# Master-Slave.net
KiCad netlist of a schematic drawn in Altium Designer
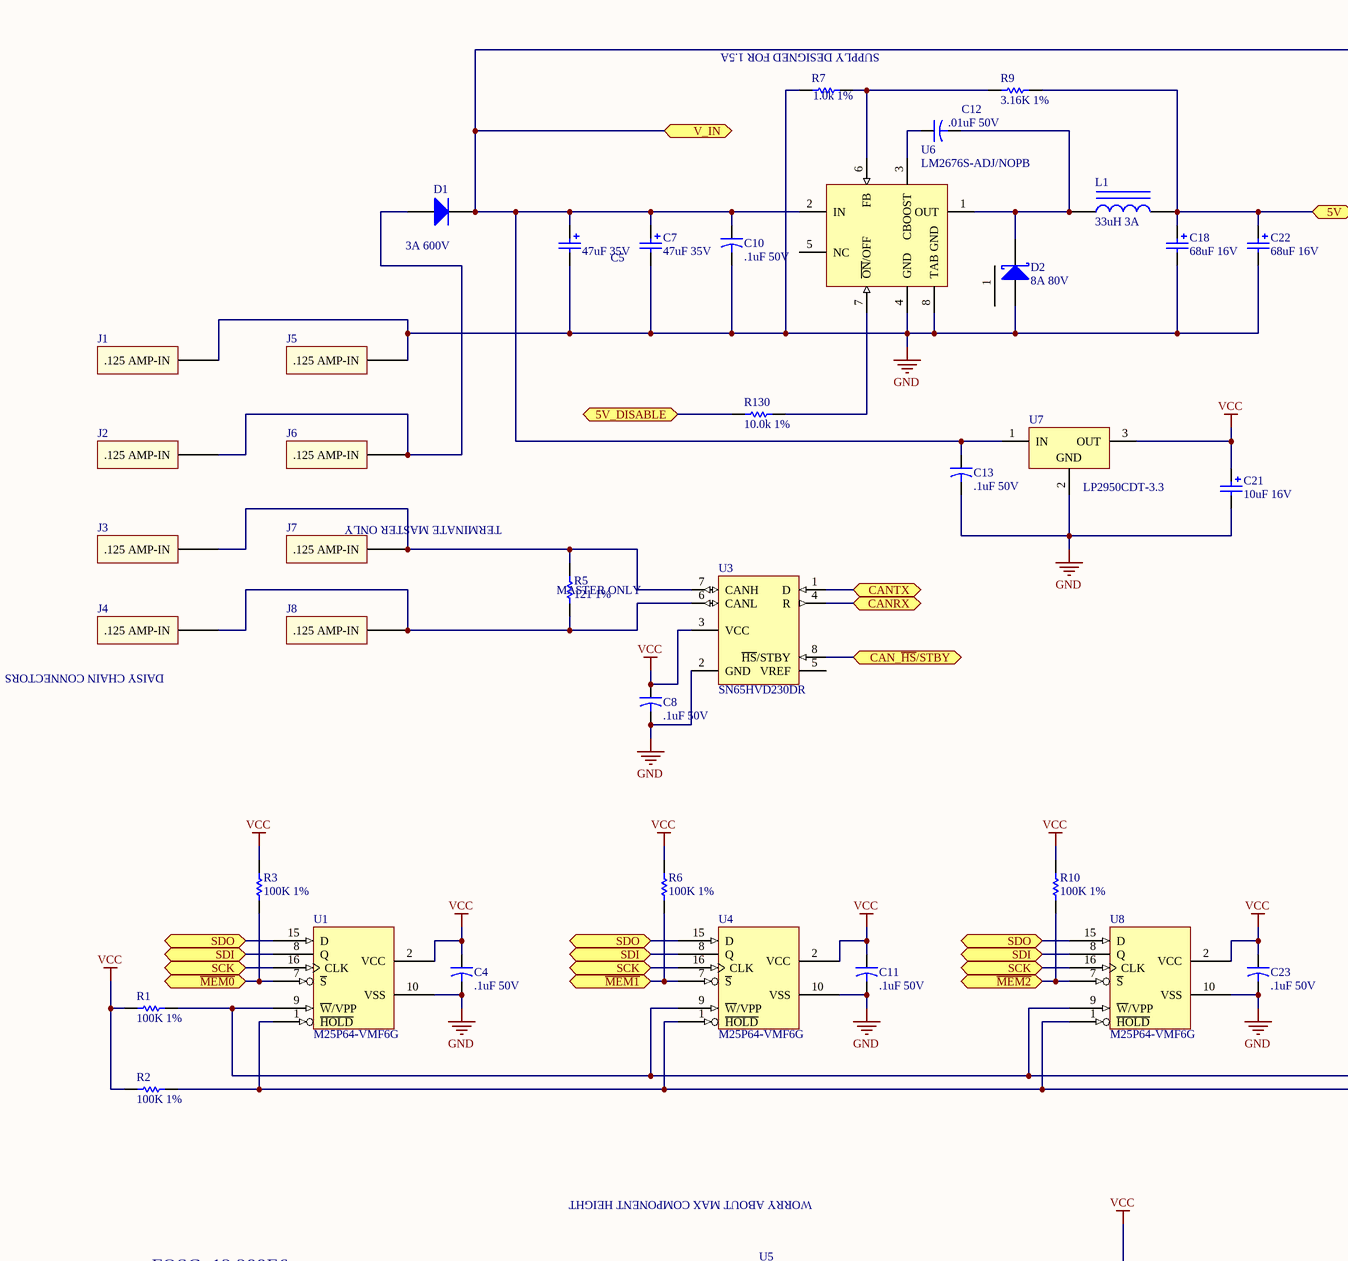
[diagram p0: Master-Slave.SchDoc, top left]
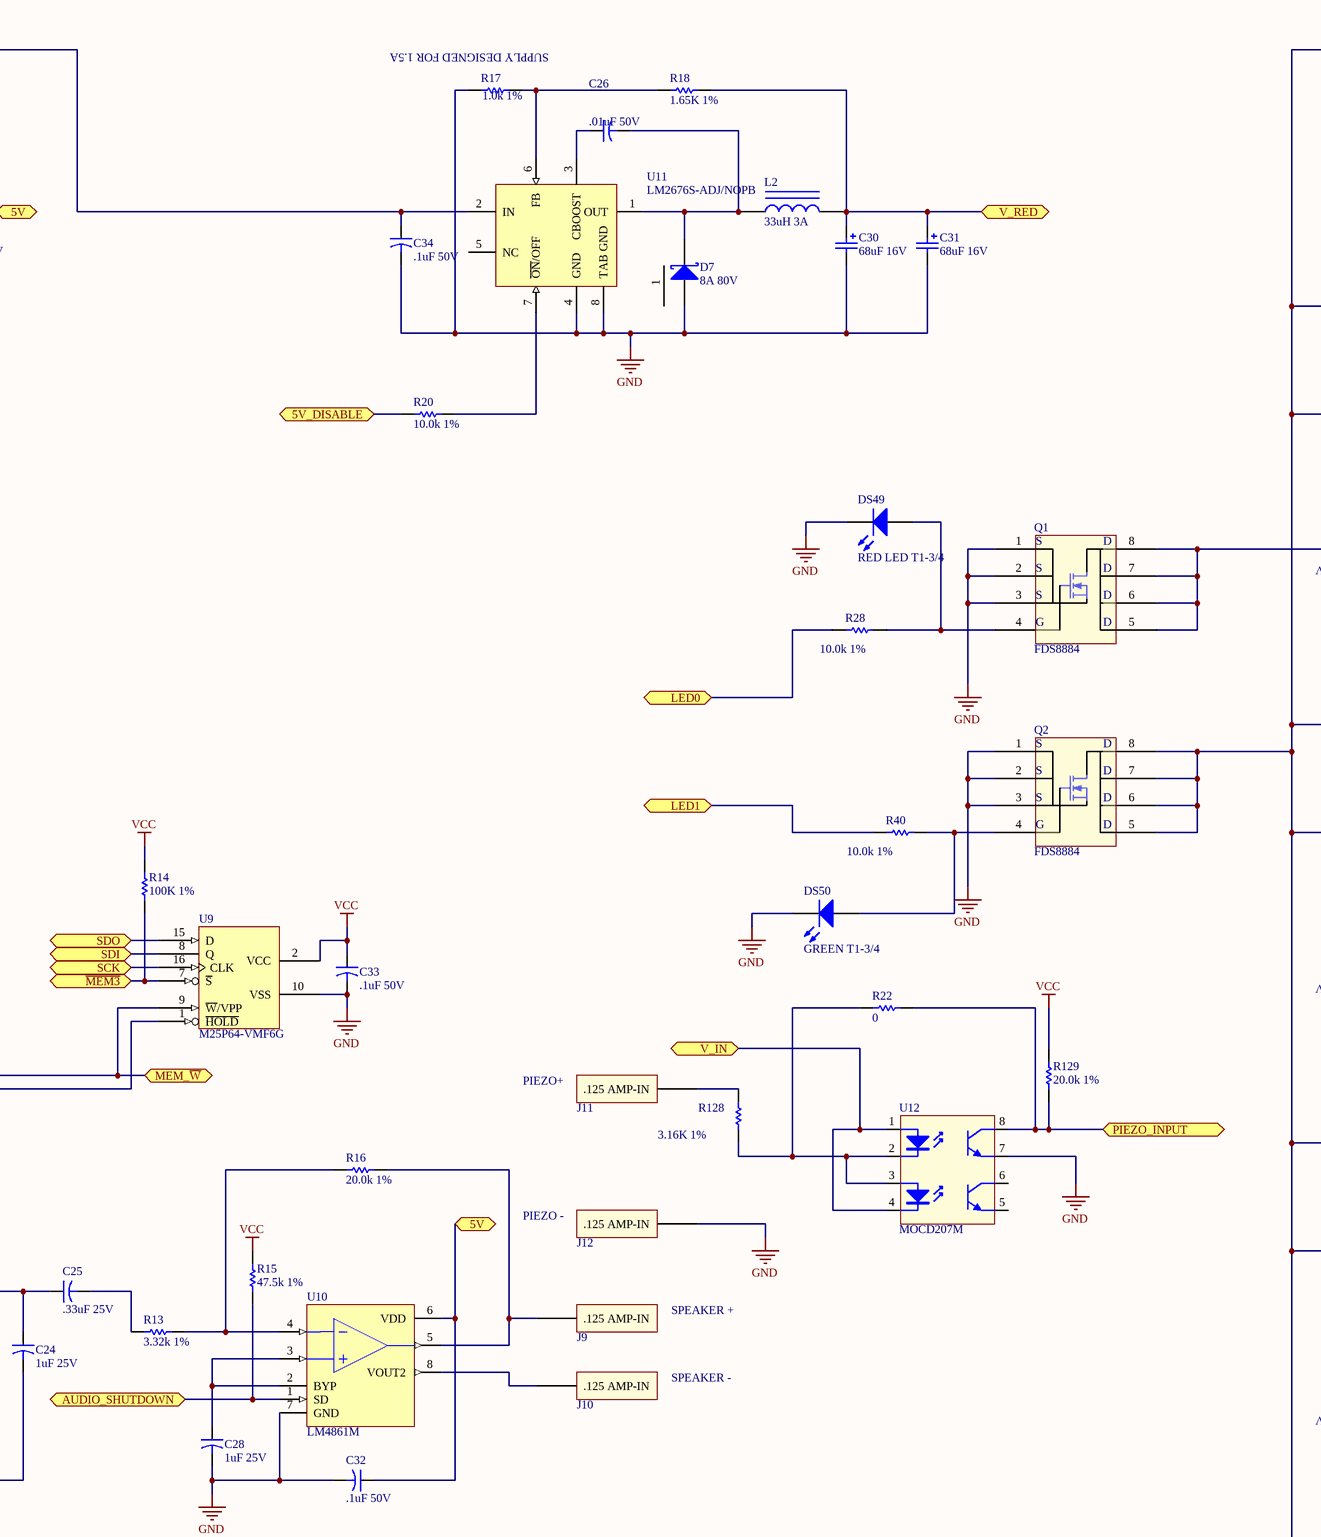
[diagram p1: Master-Slave.SchDoc, top middle]
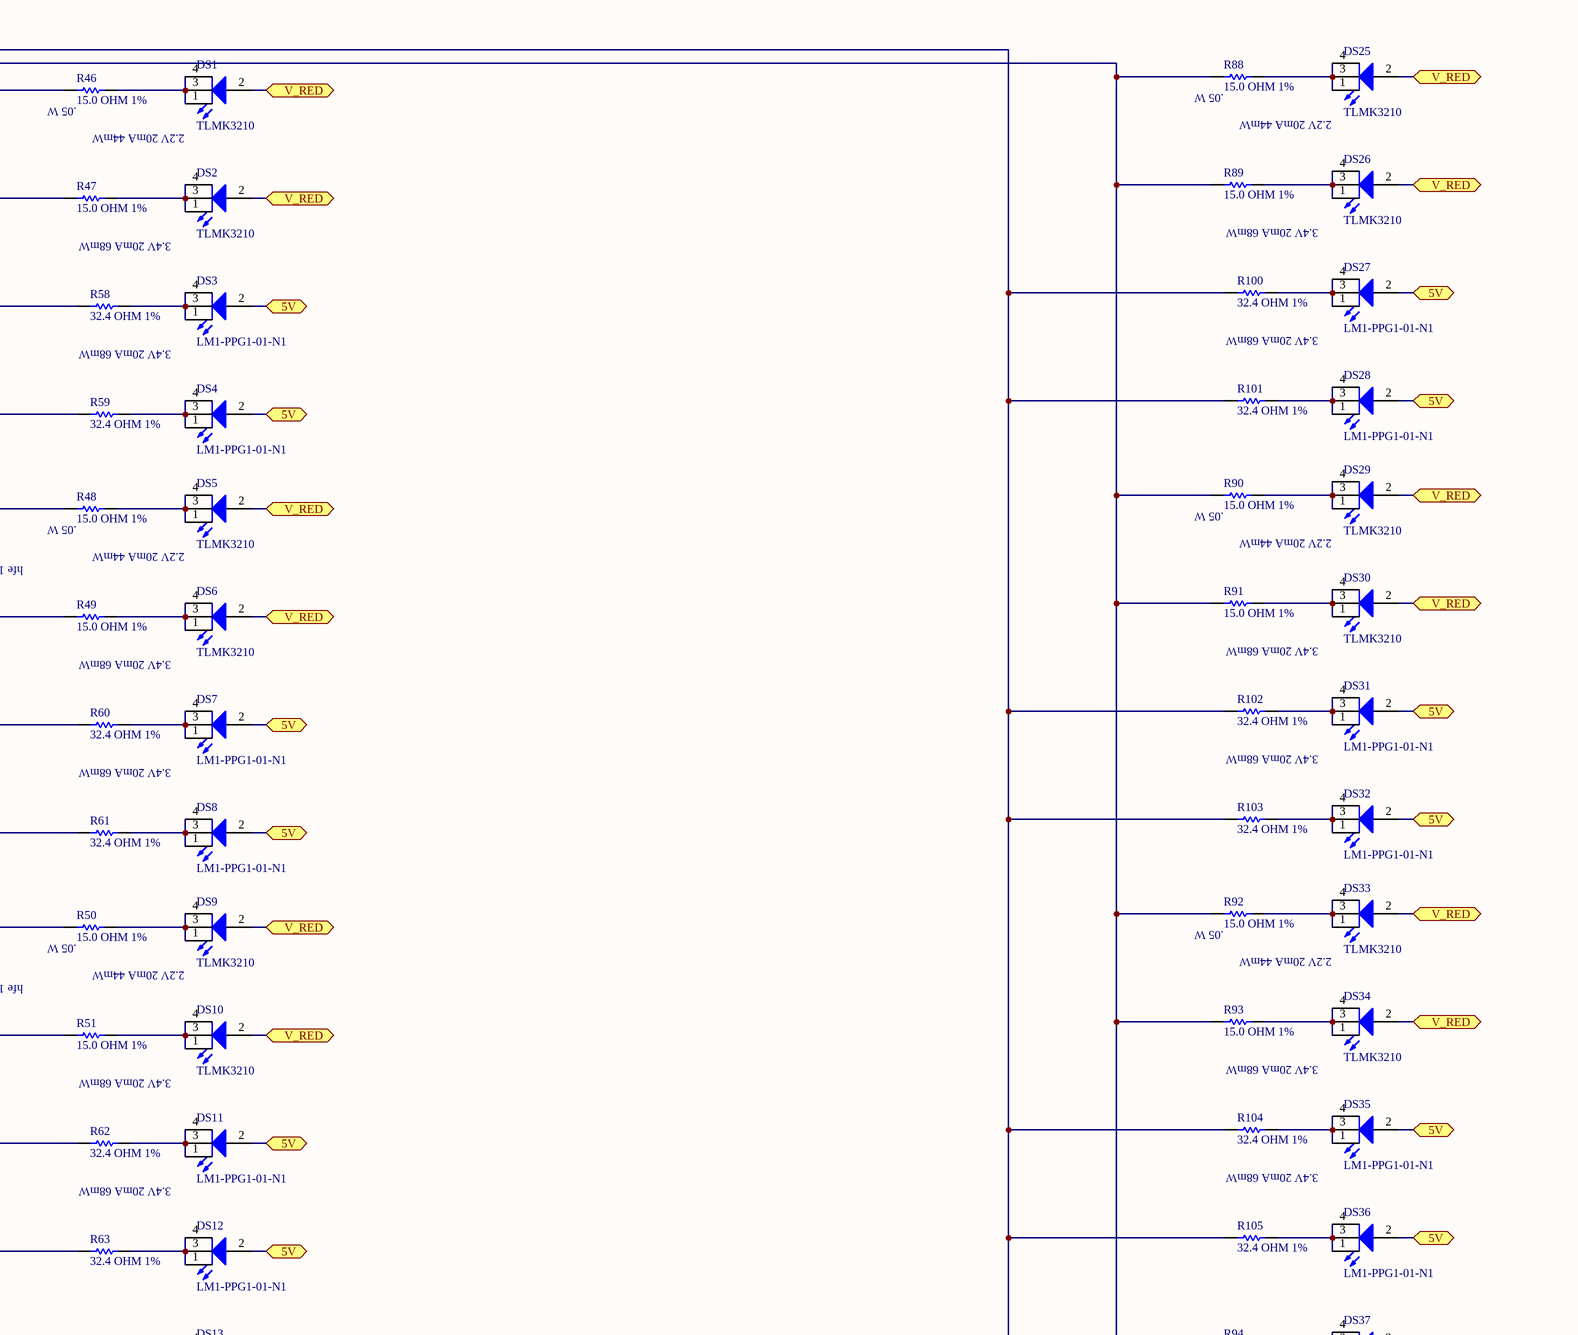
[diagram p2: Master-Slave.SchDoc, top right]
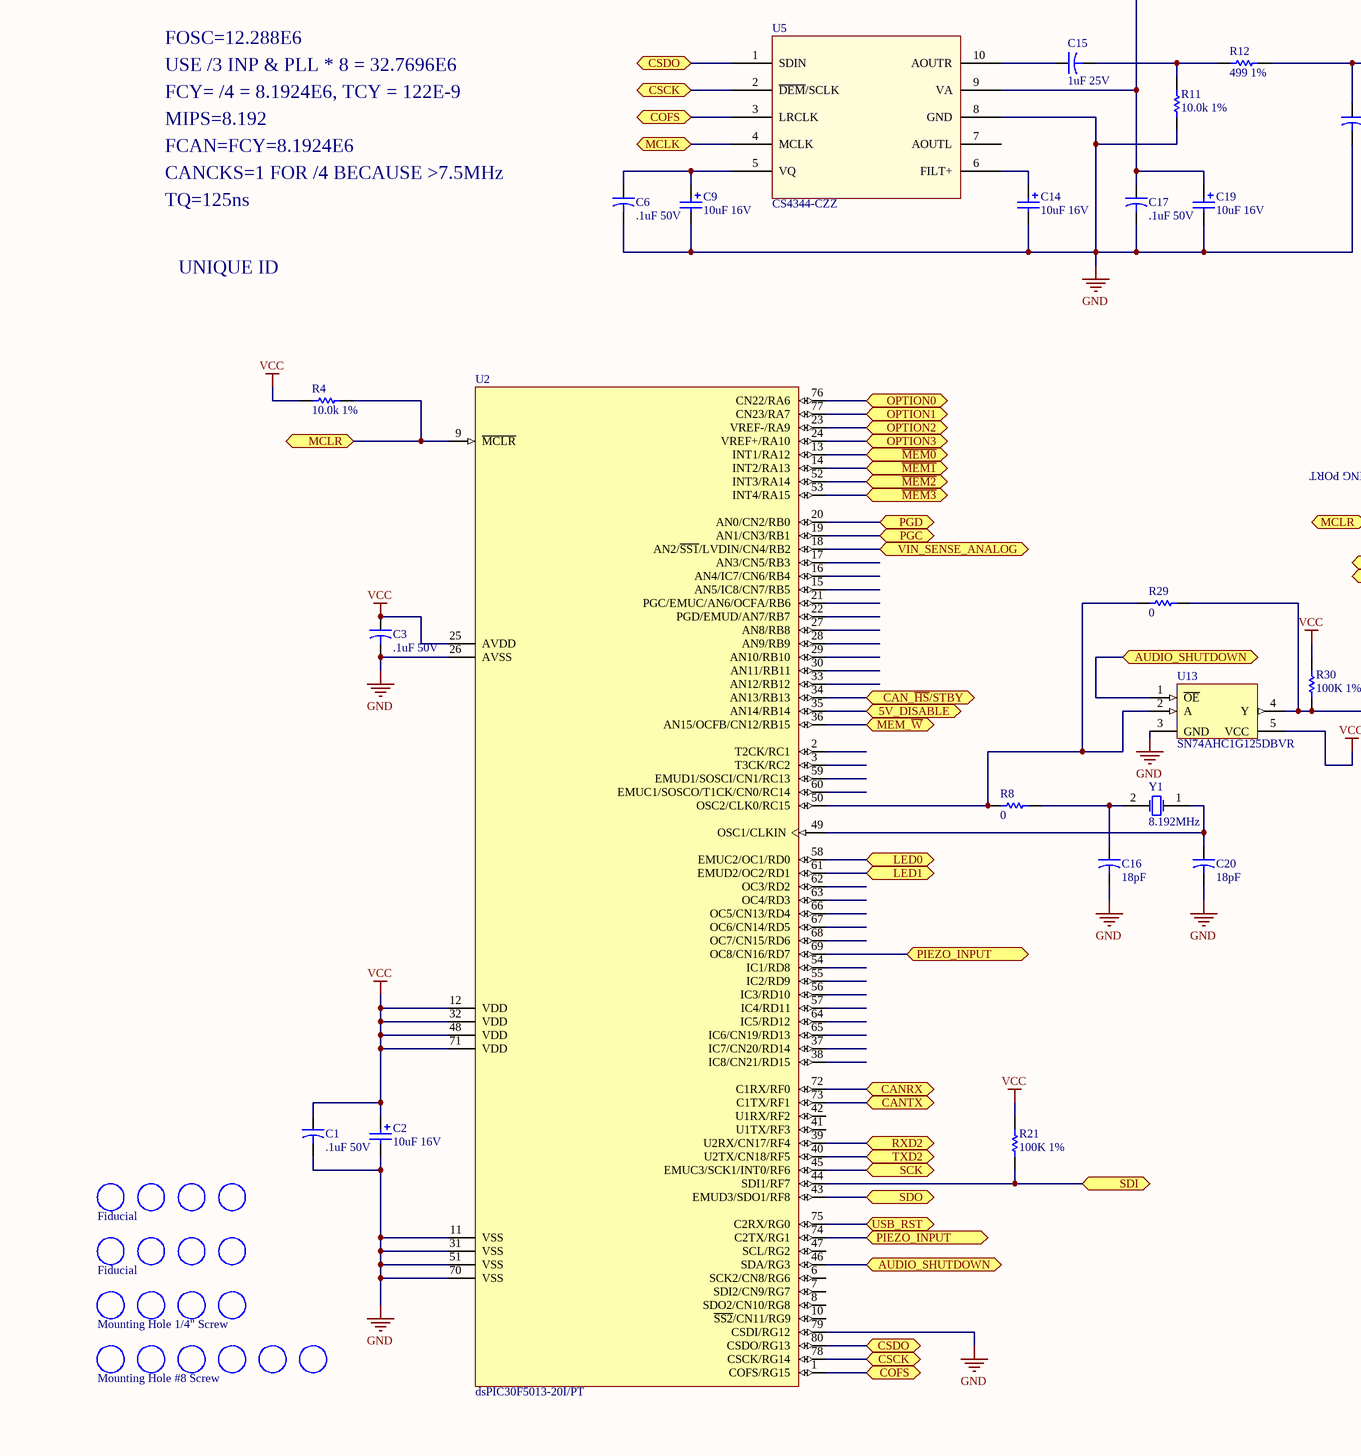
[diagram p3: Master-Slave.SchDoc, bottom left]
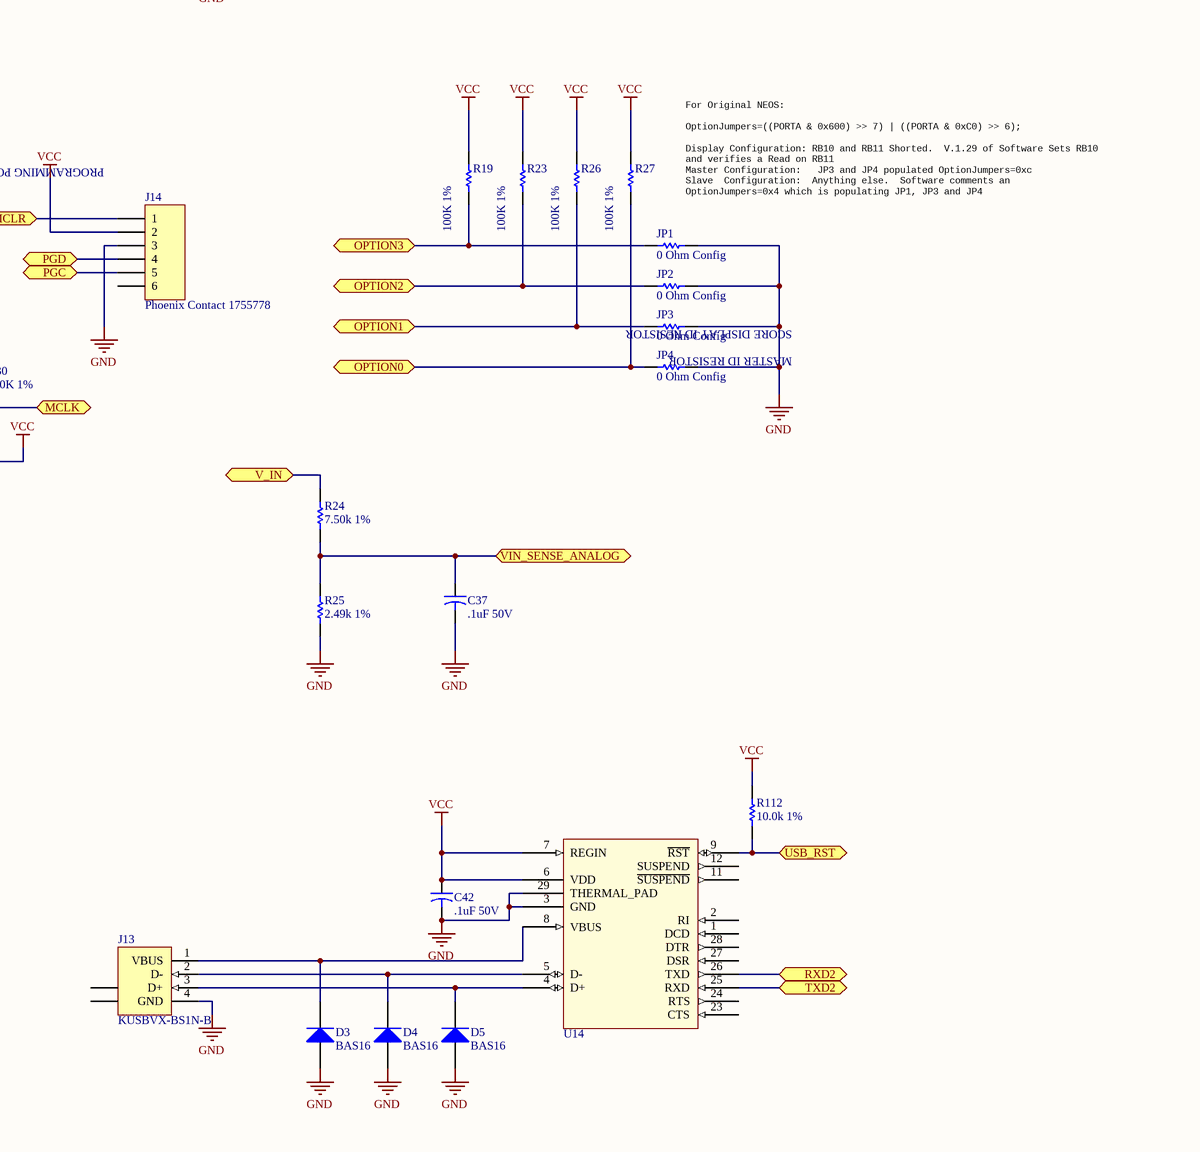
[diagram p4: Master-Slave.SchDoc, bottom middle]
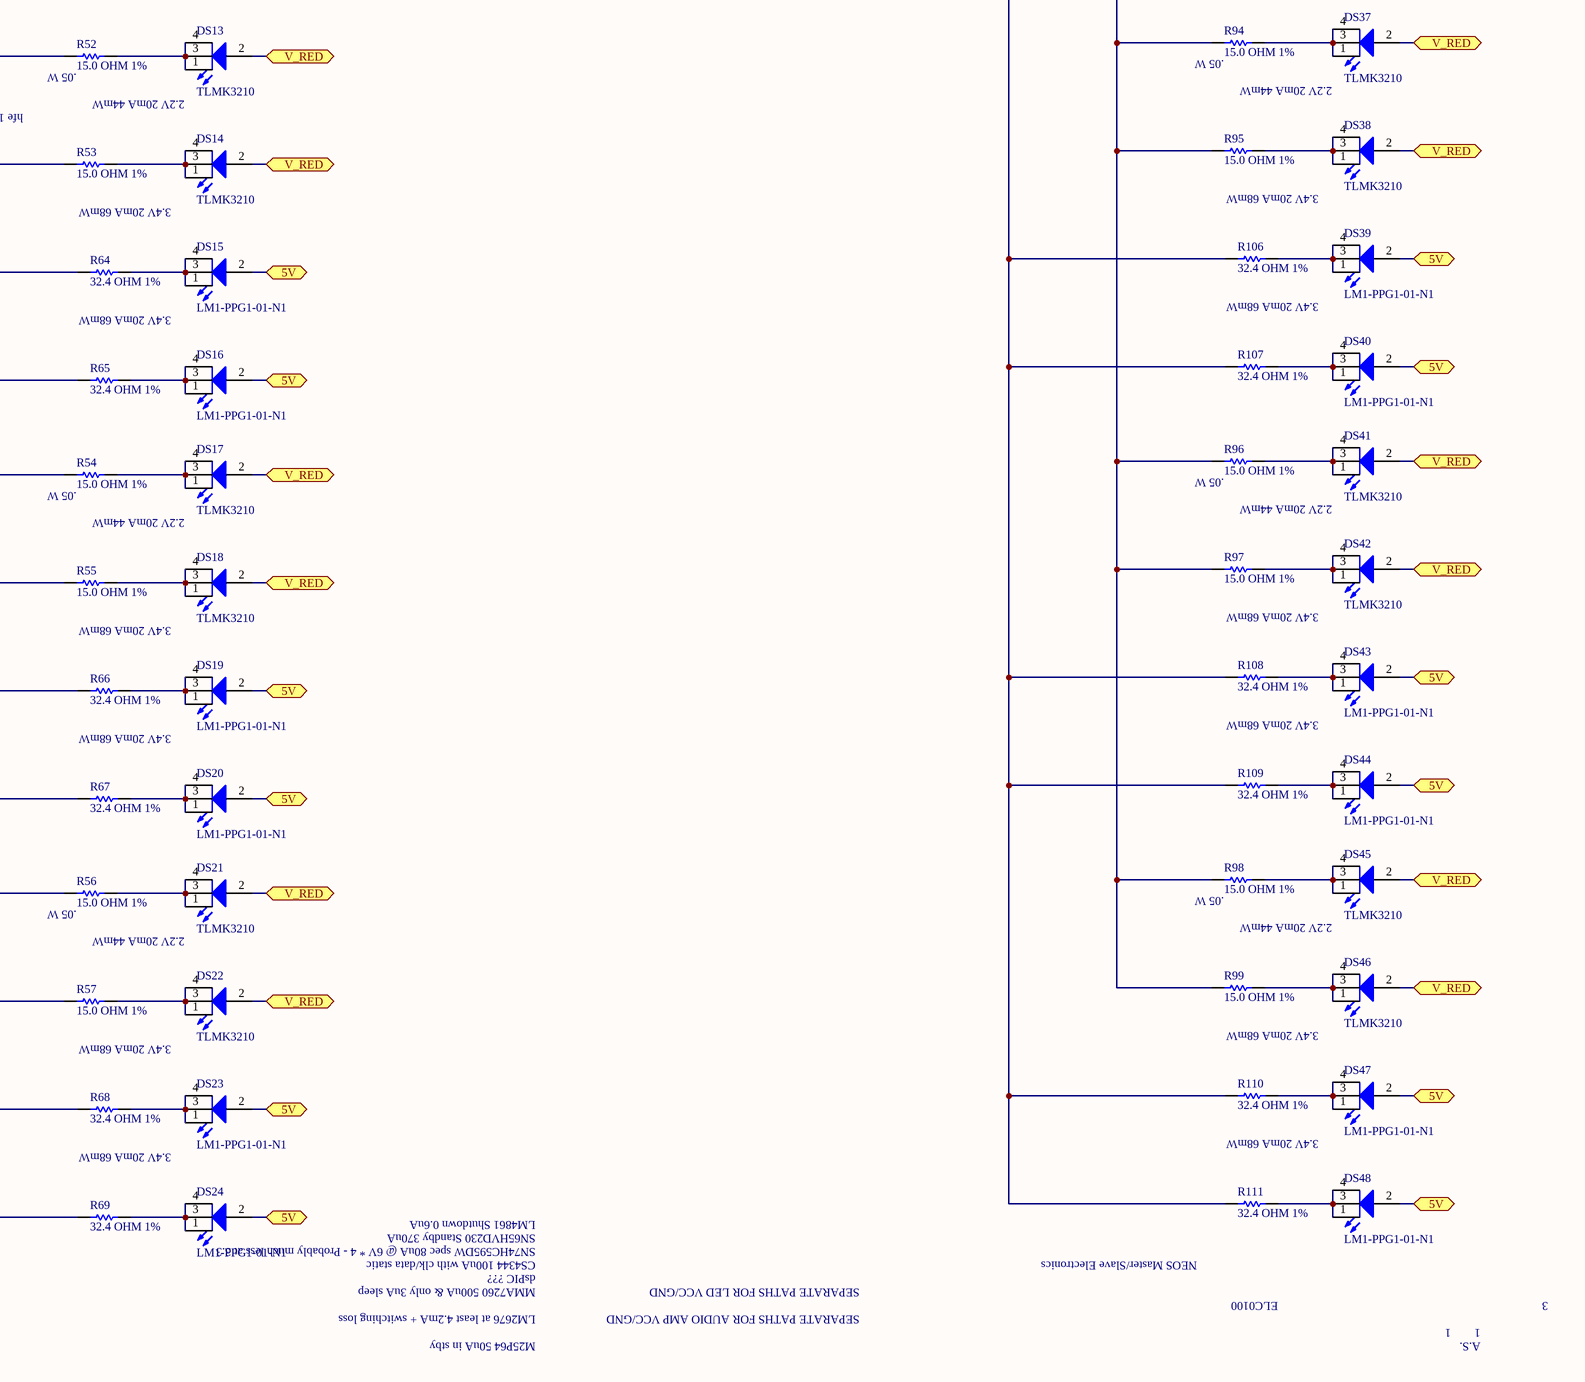
[diagram p5: Master-Slave.SchDoc, bottom right]

(export (version "E")
  (design (tool "Eeschema 10.0.6"))
  (components
    (comp (ref "C1")
      (value ".1uF 50V")
      (footprint "C0805")
      (description "CAP .10UF 50V CERAMIC X7R 0805")
      (fields
        (field (name "MANUFACTURER") "Kemet")
        (field (name "MANUFACTURER PART NUMBER") "C0805C104K5RACTU")
        (field (name "SOURCE") "Digikey")
      )
      (libsource (lib "") (part "C#S/C0805C104K5RACK_1"))
    )
    (comp (ref "C2")
      (value "10uF 16V")
      (footprint "API:C4X5.8")
      (description "CAP ELECT 10UF 16V FK SMD")
      (fields
        (field (name "MANUFACTURER") "Panasonic - ECG")
        (field (name "MANUFACTURER PART NUMBER") "EEE-FK1C100R")
        (field (name "SOURCE") "Digikey")
      )
      (libsource (lib "API") (part "C#S/EEEFK1C100RP"))
    )
    (comp (ref "C3")
      (value ".1uF 50V")
      (footprint "C0805")
      (description "CAP .10UF 50V CERAMIC X7R 0805")
      (fields
        (field (name "MANUFACTURER") "Kemet")
        (field (name "MANUFACTURER PART NUMBER") "C0805C104K5RACTU")
        (field (name "SOURCE") "Digikey")
      )
      (libsource (lib "") (part "C#S/C0805C104K5RACK_1"))
    )
    (comp (ref "C4")
      (value ".1uF 50V")
      (footprint "C0805")
      (description "CAP .10UF 50V CERAMIC X7R 0805")
      (fields
        (field (name "MANUFACTURER") "Kemet")
        (field (name "MANUFACTURER PART NUMBER") "C0805C104K5RACTU")
        (field (name "SOURCE") "Digikey")
      )
      (libsource (lib "API") (part "C#S/C0805C104K5RACK"))
    )
    (comp (ref "C5")
      (value "47uF 35V")
      (footprint "CAPACITOR TANT 47UF 35V 10% SMD 7343-43 (EIA")
      (description "CAPACITOR TANT 47UF 35V 10% SMD 7343-43 (EIA)")
      (fields
        (field (name "MANUFACTURER") "Kemet")
        (field (name "MANUFACTURER PART NUMBER") "T491X476K035AT")
        (field (name "SOURCE") "Digikey")
      )
      (libsource (lib "API") (part "C#S/T491X476K035ATK"))
    )
    (comp (ref "C6")
      (value ".1uF 50V")
      (footprint "C0805")
      (description "CAP .10UF 50V CERAMIC X7R 0805")
      (fields
        (field (name "MANUFACTURER") "Kemet")
        (field (name "MANUFACTURER PART NUMBER") "C0805C104K5RACTU")
        (field (name "SOURCE") "Digikey")
      )
      (libsource (lib "API") (part "C#S/C0805C104K5RACK"))
    )
    (comp (ref "C7")
      (value "47uF 35V")
      (footprint "CAPACITOR TANT 47UF 35V 10% SMD 7343-43 (EIA")
      (description "CAPACITOR TANT 47UF 35V 10% SMD 7343-43 (EIA)")
      (fields
        (field (name "MANUFACTURER") "Kemet")
        (field (name "MANUFACTURER PART NUMBER") "T491X476K035AT")
        (field (name "SOURCE") "Digikey")
      )
      (libsource (lib "API") (part "C#S/T491X476K035ATK"))
    )
    (comp (ref "C8")
      (value ".1uF 50V")
      (footprint "C0805")
      (description "CAP .10UF 50V CERAMIC X7R 0805")
      (fields
        (field (name "MANUFACTURER") "Kemet")
        (field (name "MANUFACTURER PART NUMBER") "C0805C104K5RACTU")
        (field (name "SOURCE") "Digikey")
      )
      (libsource (lib "API") (part "C#S/C0805C104K5RACK"))
    )
    (comp (ref "C9")
      (value "10uF 16V")
      (footprint "API:C4X5.8")
      (description "CAP ELECT 10UF 16V FK SMD")
      (fields
        (field (name "MANUFACTURER") "Panasonic - ECG")
        (field (name "MANUFACTURER PART NUMBER") "EEE-FK1C100R")
        (field (name "SOURCE") "Digikey")
      )
      (libsource (lib "API") (part "C#S/EEEFK1C100RP"))
    )
    (comp (ref "C10")
      (value ".1uF 50V")
      (footprint "C0805")
      (description "CAP .10UF 50V CERAMIC X7R 0805")
      (fields
        (field (name "MANUFACTURER") "Kemet")
        (field (name "MANUFACTURER PART NUMBER") "C0805C104K5RACTU")
        (field (name "SOURCE") "Digikey")
      )
      (libsource (lib "API") (part "C#S/C0805C104K5RACK"))
    )
    (comp (ref "C11")
      (value ".1uF 50V")
      (footprint "C0805")
      (description "CAP .10UF 50V CERAMIC X7R 0805")
      (fields
        (field (name "MANUFACTURER") "Kemet")
        (field (name "MANUFACTURER PART NUMBER") "C0805C104K5RACTU")
        (field (name "SOURCE") "Digikey")
      )
      (libsource (lib "API") (part "C#S/C0805C104K5RACK"))
    )
    (comp (ref "C12")
      (value ".01uF 50V")
      (footprint "API:C0805")
      (description "CAP 10000PF 50V CERAMIC X7R 0805")
      (fields
        (field (name "MANUFACTURER") "Kemet")
        (field (name "MANUFACTURER PART NUMBER") "C0805C103K5RACTU")
        (field (name "SOURCE") "Digikey")
      )
      (libsource (lib "API") (part "C#S/C0805C103K5RAC"))
    )
    (comp (ref "C13")
      (value ".1uF 50V")
      (footprint "C0805")
      (description "CAP .10UF 50V CERAMIC X7R 0805")
      (fields
        (field (name "MANUFACTURER") "Kemet")
        (field (name "MANUFACTURER PART NUMBER") "C0805C104K5RACTU")
        (field (name "SOURCE") "Digikey")
      )
      (libsource (lib "API") (part "C#S/C0805C104K5RACK"))
    )
    (comp (ref "C14")
      (value "10uF 16V")
      (footprint "C4X5.8")
      (description "CAP ELECT 10UF 16V FK SMD")
      (fields
        (field (name "MANUFACTURER") "Panasonic - ECG")
        (field (name "MANUFACTURER PART NUMBER") "EEE-FK1C100R")
        (field (name "SOURCE") "Digikey")
      )
      (libsource (lib "API") (part "C#S/EEEFK1C100RP"))
    )
    (comp (ref "C15")
      (value "1uF 25V")
      (footprint "API:R1206")
      (description "CAP 1UF 25V CERAMIC X7R 1206")
      (fields
        (field (name "MANUFACTURER") "Panasonic - ECG")
        (field (name "MANUFACTURER PART NUMBER") "ECJ-3YB1E105K")
        (field (name "SOURCE") "Digikey")
      )
      (libsource (lib "API") (part "C#S/ECJ3YB1E105KP"))
    )
    (comp (ref "C16")
      (value "18pF")
      (footprint "API:C0805")
      (description "CAP CERAMIC 18PF 50V NP0 0805")
      (fields
        (field (name "MANUFACTURER") "Kemet")
        (field (name "MANUFACTURER PART NUMBER") "C0805C180J5GACTU")
        (field (name "SOURCE") "Digikey")
      )
      (libsource (lib "API") (part "C#S/C0805C180J5GACTUK"))
    )
    (comp (ref "C17")
      (value ".1uF 50V")
      (footprint "C0805")
      (description "CAP .10UF 50V CERAMIC X7R 0805")
      (fields
        (field (name "MANUFACTURER") "Kemet")
        (field (name "MANUFACTURER PART NUMBER") "C0805C104K5RACTU")
        (field (name "SOURCE") "Digikey")
      )
      (libsource (lib "API") (part "C#S/C0805C104K5RACK"))
    )
    (comp (ref "C18")
      (value "68uF 16V")
      (footprint "API:C7343")
      (description "CAPACITOR TANT 68UF 16V 10% SMD")
      (fields
        (field (name "MANUFACTURER") "Kemet")
        (field (name "MANUFACTURER PART NUMBER") "T495D686K016ATE150")
        (field (name "SOURCE") "Digikey")
      )
      (libsource (lib "API") (part "C#S/T495D686K016ATEK"))
    )
    (comp (ref "C19")
      (value "10uF 16V")
      (footprint "API:C4X5.8")
      (description "CAP ELECT 10UF 16V FK SMD")
      (fields
        (field (name "MANUFACTURER") "Panasonic - ECG")
        (field (name "MANUFACTURER PART NUMBER") "EEE-FK1C100R")
        (field (name "SOURCE") "Digikey")
      )
      (libsource (lib "API") (part "C#S/EEEFK1C100RP"))
    )
    (comp (ref "C20")
      (value "18pF")
      (footprint "API:C0805")
      (description "CAP CERAMIC 18PF 50V NP0 0805")
      (fields
        (field (name "MANUFACTURER") "Kemet")
        (field (name "MANUFACTURER PART NUMBER") "C0805C180J5GACTU")
        (field (name "SOURCE") "Digikey")
      )
      (libsource (lib "API") (part "C#S/C0805C180J5GACTUK"))
    )
    (comp (ref "C21")
      (value "10uF 16V")
      (footprint "API:C4X5.8")
      (description "CAP ELECT 10UF 16V FK SMD")
      (fields
        (field (name "MANUFACTURER") "Panasonic - ECG")
        (field (name "MANUFACTURER PART NUMBER") "EEE-FK1C100R")
        (field (name "SOURCE") "Digikey")
      )
      (libsource (lib "API") (part "C#S/EEEFK1C100RP"))
    )
    (comp (ref "C22")
      (value "68uF 16V")
      (footprint "API:C7343")
      (description "CAPACITOR TANT 68UF 16V 10% SMD")
      (fields
        (field (name "MANUFACTURER") "Kemet")
        (field (name "MANUFACTURER PART NUMBER") "T495D686K016ATE150")
        (field (name "SOURCE") "Digikey")
      )
      (libsource (lib "API") (part "C#S/T495D686K016ATEK"))
    )
    (comp (ref "C23")
      (value ".1uF 50V")
      (footprint "C0805")
      (description "CAP .10UF 50V CERAMIC X7R 0805")
      (fields
        (field (name "MANUFACTURER") "Kemet")
        (field (name "MANUFACTURER PART NUMBER") "C0805C104K5RACTU")
        (field (name "SOURCE") "Digikey")
      )
      (libsource (lib "API") (part "C#S/C0805C104K5RACK"))
    )
    (comp (ref "C24")
      (value "1uF 25V")
      (footprint "API:R1206")
      (description "CAP 1UF 25V CERAMIC X7R 1206")
      (fields
        (field (name "MANUFACTURER") "Panasonic - ECG")
        (field (name "MANUFACTURER PART NUMBER") "ECJ-3YB1E105K")
        (field (name "SOURCE") "Digikey")
      )
      (libsource (lib "API") (part "C#S/ECJ3YB1E105KP"))
    )
    (comp (ref "C25")
      (value ".33uF 25V")
      (footprint "API:R1206")
      (description "CAP .33UF 25V CERAMIC X7R 1206")
      (fields
        (field (name "MANUFACTURER") "Panasonic - ECG")
        (field (name "MANUFACTURER PART NUMBER") "ECJ-3VB1E334K")
        (field (name "SOURCE") "Digikey")
      )
      (libsource (lib "API") (part "C#S/ECJ3VB1E334KP"))
    )
    (comp (ref "C26")
      (value ".01uF 50V")
      (footprint "API:C0805")
      (description "CAP 10000PF 50V CERAMIC X7R 0805")
      (fields
        (field (name "MANUFACTURER") "Kemet")
        (field (name "MANUFACTURER PART NUMBER") "C0805C103K5RACTU")
        (field (name "SOURCE") "Digikey")
      )
      (libsource (lib "API") (part "C#S/C0805C103K5RAC"))
    )
    (comp (ref "C28")
      (value "1uF 25V")
      (footprint "API:R1206")
      (description "CAP 1UF 25V CERAMIC X7R 1206")
      (fields
        (field (name "MANUFACTURER") "Panasonic - ECG")
        (field (name "MANUFACTURER PART NUMBER") "ECJ-3YB1E105K")
        (field (name "SOURCE") "Digikey")
      )
      (libsource (lib "API") (part "C#S/ECJ3YB1E105KP"))
    )
    (comp (ref "C30")
      (value "68uF 16V")
      (footprint "D")
      (description "CAPACITOR TANT 68UF 16V 10% SMD")
      (fields
        (field (name "MANUFACTURER") "Kemet")
        (field (name "MANUFACTURER PART NUMBER") "T495D686K016ATE150")
        (field (name "SOURCE") "Digikey")
      )
      (libsource (lib "API") (part "C#S/T495D686K016ATEK"))
    )
    (comp (ref "C31")
      (value "68uF 16V")
      (footprint "API:C7343")
      (description "CAPACITOR TANT 68UF 16V 10% SMD")
      (fields
        (field (name "MANUFACTURER") "Kemet")
        (field (name "MANUFACTURER PART NUMBER") "T495D686K016ATE150")
        (field (name "SOURCE") "Digikey")
      )
      (libsource (lib "API") (part "C#S/T495D686K016ATEK"))
    )
    (comp (ref "C32")
      (value ".1uF 50V")
      (footprint "C0805")
      (description "CAP .10UF 50V CERAMIC X7R 0805")
      (fields
        (field (name "MANUFACTURER") "Kemet")
        (field (name "MANUFACTURER PART NUMBER") "C0805C104K5RACTU")
        (field (name "SOURCE") "Digikey")
      )
      (libsource (lib "API") (part "C#S/C0805C104K5RACK"))
    )
    (comp (ref "C33")
      (value ".1uF 50V")
      (footprint "C0805")
      (description "CAP .10UF 50V CERAMIC X7R 0805")
      (fields
        (field (name "MANUFACTURER") "Kemet")
        (field (name "MANUFACTURER PART NUMBER") "C0805C104K5RACTU")
        (field (name "SOURCE") "Digikey")
      )
      (libsource (lib "API") (part "C#S/C0805C104K5RACK"))
    )
    (comp (ref "C34")
      (value ".1uF 50V")
      (footprint "C0805")
      (description "CAP .10UF 50V CERAMIC X7R 0805")
      (fields
        (field (name "MANUFACTURER") "Kemet")
        (field (name "MANUFACTURER PART NUMBER") "C0805C104K5RACTU")
        (field (name "SOURCE") "Digikey")
      )
      (libsource (lib "API") (part "C#S/C0805C104K5RACK"))
    )
    (comp (ref "C37")
      (value ".1uF 50V")
      (footprint "C0805")
      (description "CAP .10UF 50V CERAMIC X7R 0805")
      (fields
        (field (name "MANUFACTURER") "Kemet")
        (field (name "MANUFACTURER PART NUMBER") "C0805C104K5RACTU")
        (field (name "SOURCE") "Digikey")
      )
      (libsource (lib "API") (part "C#S/C0805C104K5RACK"))
    )
    (comp (ref "C42")
      (value ".1uF 50V")
      (footprint "C0805")
      (description "CAP .10UF 50V CERAMIC X7R 0805")
      (fields
        (field (name "MANUFACTURER") "Kemet")
        (field (name "MANUFACTURER PART NUMBER") "C0805C104K5RACTU")
        (field (name "SOURCE") "Digikey")
      )
      (libsource (lib "API") (part "C#S/C0805C104K5RACK"))
    )
    (comp (ref "D1")
      (value "3A 600V")
      (footprint "API:DIODE_SMC")
      (description "DIODE ULTRA FAST 3A 600V SMC")
      (fields
        (field (name "MANUFACTURER") "ON Semiconductor")
        (field (name "MANUFACTURER PART NUMBER") "MURS360T3G")
        (field (name "SOURCE") "Digikey")
      )
      (libsource (lib "API") (part "D#S/MURS360T3GM"))
    )
    (comp (ref "D2")
      (value "8A 80V")
      (footprint "API:D2PAK")
      (description "DIODE SCHOTTKY 80V 8A D2PAK")
      (fields
        (field (name "MANUFACTURER") "Vishay IR")
        (field (name "MANUFACTURER PART NUMBER") "8TQ100SPBF")
        (field (name "SOURCE") "Digikey")
      )
      (libsource (lib "API") (part "D#S/8TQ080SPBFZ"))
    )
    (comp (ref "D3")
      (value "BAS16")
      (footprint "API:SOT23")
      (description "Diodes Inc BAS16 75V 200mA")
      (fields
        (field (name "MANUFACTURER") "Diodes Inc")
        (field (name "MANUFACTURER PART NUMBER") "BAS16-7-F")
        (field (name "SOURCE") "Digikey")
      )
      (libsource (lib "API") (part "D#S/BAS167F0D"))
    )
    (comp (ref "D4")
      (value "BAS16")
      (footprint "API:SOT23")
      (description "Diodes Inc BAS16 75V 200mA")
      (fields
        (field (name "MANUFACTURER") "Diodes Inc")
        (field (name "MANUFACTURER PART NUMBER") "BAS16-7-F")
        (field (name "SOURCE") "Digikey")
      )
      (libsource (lib "API") (part "D#S/BAS167F0D"))
    )
    (comp (ref "D5")
      (value "BAS16")
      (footprint "API:SOT23")
      (description "Diodes Inc BAS16 75V 200mA")
      (fields
        (field (name "MANUFACTURER") "Diodes Inc")
        (field (name "MANUFACTURER PART NUMBER") "BAS16-7-F")
        (field (name "SOURCE") "Digikey")
      )
      (libsource (lib "API") (part "D#S/BAS167F0D"))
    )
    (comp (ref "D7")
      (value "8A 80V")
      (footprint "API:D2PAK")
      (description "DIODE SCHOTTKY 80V 8A D2PAK")
      (fields
        (field (name "MANUFACTURER") "Vishay IR")
        (field (name "MANUFACTURER PART NUMBER") "8TQ100SPBF")
        (field (name "SOURCE") "Digikey")
      )
      (libsource (lib "API") (part "D#S/8TQ080SPBFZ"))
    )
    (comp (ref "DS1")
      (value "TLMK3210")
      (footprint "API:L#S/TLMK3210Z")
      (description "Vishay Red LED PLCC-3")
      (fields
        (field (name "MANUFACTURER") "Vishay")
        (field (name "MANUFACTURER PART NUMBER") "TLMK3210-GS08")
        (field (name "SOURCE") "Future")
      )
      (libsource (lib "API") (part "L#S/TLMK3210"))
    )
    (comp (ref "DS2")
      (value "TLMK3210")
      (footprint "API:L#S/TLMK3210Z")
      (description "Vishay Red LED PLCC-3")
      (fields
        (field (name "MANUFACTURER") "Vishay")
        (field (name "MANUFACTURER PART NUMBER") "TLMK3210-GS08")
        (field (name "SOURCE") "Future")
      )
      (libsource (lib "API") (part "L#S/TLMK3210"))
    )
    (comp (ref "DS3")
      (value "LM1-PPG1-01-N1")
      (footprint "L#S/TLMK3210Z")
      (description "120-degree, 3.3 x 3.5-mm, SMT LED in green color with water-transparent lens")
      (fields (field (name "MANUFACTURER") "Cree") (field (name "SOURCE") "Marktech Optoelectronics"))
      (libsource (lib "API") (part "L#S/LM1PPG103N1Z"))
    )
    (comp (ref "DS4")
      (value "LM1-PPG1-01-N1")
      (footprint "L#S/TLMK3210Z")
      (description "120-degree, 3.3 x 3.5-mm, SMT LED in green color with water-transparent lens")
      (fields (field (name "MANUFACTURER") "Cree") (field (name "SOURCE") "Marktech Optoelectronics"))
      (libsource (lib "API") (part "L#S/LM1PPG103N1Z"))
    )
    (comp (ref "DS5")
      (value "TLMK3210")
      (footprint "API:L#S/TLMK3210Z")
      (description "Vishay Red LED PLCC-3")
      (fields
        (field (name "MANUFACTURER") "Vishay")
        (field (name "MANUFACTURER PART NUMBER") "TLMK3210-GS08")
        (field (name "SOURCE") "Future")
      )
      (libsource (lib "API") (part "L#S/TLMK3210"))
    )
    (comp (ref "DS6")
      (value "TLMK3210")
      (footprint "API:L#S/TLMK3210Z")
      (description "Vishay Red LED PLCC-3")
      (fields
        (field (name "MANUFACTURER") "Vishay")
        (field (name "MANUFACTURER PART NUMBER") "TLMK3210-GS08")
        (field (name "SOURCE") "Future")
      )
      (libsource (lib "API") (part "L#S/TLMK3210"))
    )
    (comp (ref "DS7")
      (value "LM1-PPG1-01-N1")
      (footprint "L#S/TLMK3210Z")
      (description "120-degree, 3.3 x 3.5-mm, SMT LED in green color with water-transparent lens")
      (fields (field (name "MANUFACTURER") "Cree") (field (name "SOURCE") "Marktech Optoelectronics"))
      (libsource (lib "API") (part "L#S/LM1PPG103N1Z"))
    )
    (comp (ref "DS8")
      (value "LM1-PPG1-01-N1")
      (footprint "L#S/TLMK3210Z")
      (description "120-degree, 3.3 x 3.5-mm, SMT LED in green color with water-transparent lens")
      (fields (field (name "MANUFACTURER") "Cree") (field (name "SOURCE") "Marktech Optoelectronics"))
      (libsource (lib "API") (part "L#S/LM1PPG103N1Z"))
    )
    (comp (ref "DS9")
      (value "TLMK3210")
      (footprint "API:L#S/TLMK3210Z")
      (description "Vishay Red LED PLCC-3")
      (fields
        (field (name "MANUFACTURER") "Vishay")
        (field (name "MANUFACTURER PART NUMBER") "TLMK3210-GS08")
        (field (name "SOURCE") "Future")
      )
      (libsource (lib "API") (part "L#S/TLMK3210"))
    )
    (comp (ref "DS10")
      (value "TLMK3210")
      (footprint "API:L#S/TLMK3210Z")
      (description "Vishay Red LED PLCC-3")
      (fields
        (field (name "MANUFACTURER") "Vishay")
        (field (name "MANUFACTURER PART NUMBER") "TLMK3210-GS08")
        (field (name "SOURCE") "Future")
      )
      (libsource (lib "API") (part "L#S/TLMK3210"))
    )
    (comp (ref "DS11")
      (value "LM1-PPG1-01-N1")
      (footprint "L#S/TLMK3210Z")
      (description "120-degree, 3.3 x 3.5-mm, SMT LED in green color with water-transparent lens")
      (fields (field (name "MANUFACTURER") "Cree") (field (name "SOURCE") "Marktech Optoelectronics"))
      (libsource (lib "API") (part "L#S/LM1PPG103N1Z"))
    )
    (comp (ref "DS12")
      (value "LM1-PPG1-01-N1")
      (footprint "L#S/TLMK3210Z")
      (description "120-degree, 3.3 x 3.5-mm, SMT LED in green color with water-transparent lens")
      (fields (field (name "MANUFACTURER") "Cree") (field (name "SOURCE") "Marktech Optoelectronics"))
      (libsource (lib "API") (part "L#S/LM1PPG103N1Z"))
    )
    (comp (ref "DS13")
      (value "TLMK3210")
      (footprint "API:L#S/TLMK3210Z")
      (description "Vishay Red LED PLCC-3")
      (fields
        (field (name "MANUFACTURER") "Vishay")
        (field (name "MANUFACTURER PART NUMBER") "TLMK3210-GS08")
        (field (name "SOURCE") "Future")
      )
      (libsource (lib "API") (part "L#S/TLMK3210"))
    )
    (comp (ref "DS14")
      (value "TLMK3210")
      (footprint "API:L#S/TLMK3210Z")
      (description "Vishay Red LED PLCC-3")
      (fields
        (field (name "MANUFACTURER") "Vishay")
        (field (name "MANUFACTURER PART NUMBER") "TLMK3210-GS08")
        (field (name "SOURCE") "Future")
      )
      (libsource (lib "API") (part "L#S/TLMK3210"))
    )
    (comp (ref "DS15")
      (value "LM1-PPG1-01-N1")
      (footprint "L#S/TLMK3210Z")
      (description "120-degree, 3.3 x 3.5-mm, SMT LED in green color with water-transparent lens")
      (fields (field (name "MANUFACTURER") "Cree") (field (name "SOURCE") "Marktech Optoelectronics"))
      (libsource (lib "API") (part "L#S/LM1PPG103N1Z"))
    )
    (comp (ref "DS16")
      (value "LM1-PPG1-01-N1")
      (footprint "L#S/TLMK3210Z")
      (description "120-degree, 3.3 x 3.5-mm, SMT LED in green color with water-transparent lens")
      (fields (field (name "MANUFACTURER") "Cree") (field (name "SOURCE") "Marktech Optoelectronics"))
      (libsource (lib "API") (part "L#S/LM1PPG103N1Z"))
    )
    (comp (ref "DS17")
      (value "TLMK3210")
      (footprint "API:L#S/TLMK3210Z")
      (description "Vishay Red LED PLCC-3")
      (fields
        (field (name "MANUFACTURER") "Vishay")
        (field (name "MANUFACTURER PART NUMBER") "TLMK3210-GS08")
        (field (name "SOURCE") "Future")
      )
      (libsource (lib "API") (part "L#S/TLMK3210"))
    )
    (comp (ref "DS18")
      (value "TLMK3210")
      (footprint "API:L#S/TLMK3210Z")
      (description "Vishay Red LED PLCC-3")
      (fields
        (field (name "MANUFACTURER") "Vishay")
        (field (name "MANUFACTURER PART NUMBER") "TLMK3210-GS08")
        (field (name "SOURCE") "Future")
      )
      (libsource (lib "API") (part "L#S/TLMK3210"))
    )
    (comp (ref "DS19")
      (value "LM1-PPG1-01-N1")
      (footprint "L#S/TLMK3210Z")
      (description "120-degree, 3.3 x 3.5-mm, SMT LED in green color with water-transparent lens")
      (fields (field (name "MANUFACTURER") "Cree") (field (name "SOURCE") "Marktech Optoelectronics"))
      (libsource (lib "API") (part "L#S/LM1PPG103N1Z"))
    )
    (comp (ref "DS20")
      (value "LM1-PPG1-01-N1")
      (footprint "L#S/TLMK3210Z")
      (description "120-degree, 3.3 x 3.5-mm, SMT LED in green color with water-transparent lens")
      (fields (field (name "MANUFACTURER") "Cree") (field (name "SOURCE") "Marktech Optoelectronics"))
      (libsource (lib "API") (part "L#S/LM1PPG103N1Z"))
    )
    (comp (ref "DS21")
      (value "TLMK3210")
      (footprint "API:L#S/TLMK3210Z")
      (description "Vishay Red LED PLCC-3")
      (fields
        (field (name "MANUFACTURER") "Vishay")
        (field (name "MANUFACTURER PART NUMBER") "TLMK3210-GS08")
        (field (name "SOURCE") "Future")
      )
      (libsource (lib "API") (part "L#S/TLMK3210"))
    )
    (comp (ref "DS22")
      (value "TLMK3210")
      (footprint "API:L#S/TLMK3210Z")
      (description "Vishay Red LED PLCC-3")
      (fields
        (field (name "MANUFACTURER") "Vishay")
        (field (name "MANUFACTURER PART NUMBER") "TLMK3210-GS08")
        (field (name "SOURCE") "Future")
      )
      (libsource (lib "API") (part "L#S/TLMK3210"))
    )
    (comp (ref "DS23")
      (value "LM1-PPG1-01-N1")
      (footprint "L#S/TLMK3210Z")
      (description "120-degree, 3.3 x 3.5-mm, SMT LED in green color with water-transparent lens")
      (fields (field (name "MANUFACTURER") "Cree") (field (name "SOURCE") "Marktech Optoelectronics"))
      (libsource (lib "API") (part "L#S/LM1PPG103N1Z"))
    )
    (comp (ref "DS24")
      (value "LM1-PPG1-01-N1")
      (footprint "L#S/TLMK3210Z")
      (description "120-degree, 3.3 x 3.5-mm, SMT LED in green color with water-transparent lens")
      (fields (field (name "MANUFACTURER") "Cree") (field (name "SOURCE") "Marktech Optoelectronics"))
      (libsource (lib "API") (part "L#S/LM1PPG103N1Z"))
    )
    (comp (ref "DS25")
      (value "TLMK3210")
      (footprint "API:L#S/TLMK3210Z")
      (description "Vishay Red LED PLCC-3")
      (fields
        (field (name "MANUFACTURER") "Vishay")
        (field (name "MANUFACTURER PART NUMBER") "TLMK3210-GS08")
        (field (name "SOURCE") "Future")
      )
      (libsource (lib "API") (part "L#S/TLMK3210"))
    )
    (comp (ref "DS26")
      (value "TLMK3210")
      (footprint "API:L#S/TLMK3210Z")
      (description "Vishay Red LED PLCC-3")
      (fields
        (field (name "MANUFACTURER") "Vishay")
        (field (name "MANUFACTURER PART NUMBER") "TLMK3210-GS08")
        (field (name "SOURCE") "Future")
      )
      (libsource (lib "API") (part "L#S/TLMK3210"))
    )
    (comp (ref "DS27")
      (value "LM1-PPG1-01-N1")
      (footprint "L#S/TLMK3210Z")
      (description "120-degree, 3.3 x 3.5-mm, SMT LED in green color with water-transparent lens")
      (fields (field (name "MANUFACTURER") "Cree") (field (name "SOURCE") "Marktech Optoelectronics"))
      (libsource (lib "API") (part "L#S/LM1PPG103N1Z"))
    )
    (comp (ref "DS28")
      (value "LM1-PPG1-01-N1")
      (footprint "L#S/TLMK3210Z")
      (description "120-degree, 3.3 x 3.5-mm, SMT LED in green color with water-transparent lens")
      (fields (field (name "MANUFACTURER") "Cree") (field (name "SOURCE") "Marktech Optoelectronics"))
      (libsource (lib "API") (part "L#S/LM1PPG103N1Z"))
    )
    (comp (ref "DS29")
      (value "TLMK3210")
      (footprint "API:L#S/TLMK3210Z")
      (description "Vishay Red LED PLCC-3")
      (fields
        (field (name "MANUFACTURER") "Vishay")
        (field (name "MANUFACTURER PART NUMBER") "TLMK3210-GS08")
        (field (name "SOURCE") "Future")
      )
      (libsource (lib "API") (part "L#S/TLMK3210"))
    )
    (comp (ref "DS30")
      (value "TLMK3210")
      (footprint "API:L#S/TLMK3210Z")
      (description "Vishay Red LED PLCC-3")
      (fields
        (field (name "MANUFACTURER") "Vishay")
        (field (name "MANUFACTURER PART NUMBER") "TLMK3210-GS08")
        (field (name "SOURCE") "Future")
      )
      (libsource (lib "API") (part "L#S/TLMK3210"))
    )
    (comp (ref "DS31")
      (value "LM1-PPG1-01-N1")
      (footprint "L#S/TLMK3210Z")
      (description "120-degree, 3.3 x 3.5-mm, SMT LED in green color with water-transparent lens")
      (fields (field (name "MANUFACTURER") "Cree") (field (name "SOURCE") "Marktech Optoelectronics"))
      (libsource (lib "API") (part "L#S/LM1PPG103N1Z"))
    )
    (comp (ref "DS32")
      (value "LM1-PPG1-01-N1")
      (footprint "L#S/TLMK3210Z")
      (description "120-degree, 3.3 x 3.5-mm, SMT LED in green color with water-transparent lens")
      (fields (field (name "MANUFACTURER") "Cree") (field (name "SOURCE") "Marktech Optoelectronics"))
      (libsource (lib "API") (part "L#S/LM1PPG103N1Z"))
    )
    (comp (ref "DS33")
      (value "TLMK3210")
      (footprint "API:L#S/TLMK3210Z")
      (description "Vishay Red LED PLCC-3")
      (fields
        (field (name "MANUFACTURER") "Vishay")
        (field (name "MANUFACTURER PART NUMBER") "TLMK3210-GS08")
        (field (name "SOURCE") "Future")
      )
      (libsource (lib "API") (part "L#S/TLMK3210"))
    )
    (comp (ref "DS34")
      (value "TLMK3210")
      (footprint "API:L#S/TLMK3210Z")
      (description "Vishay Red LED PLCC-3")
      (fields
        (field (name "MANUFACTURER") "Vishay")
        (field (name "MANUFACTURER PART NUMBER") "TLMK3210-GS08")
        (field (name "SOURCE") "Future")
      )
      (libsource (lib "API") (part "L#S/TLMK3210"))
    )
    (comp (ref "DS35")
      (value "LM1-PPG1-01-N1")
      (footprint "L#S/TLMK3210Z")
      (description "120-degree, 3.3 x 3.5-mm, SMT LED in green color with water-transparent lens")
      (fields (field (name "MANUFACTURER") "Cree") (field (name "SOURCE") "Marktech Optoelectronics"))
      (libsource (lib "API") (part "L#S/LM1PPG103N1Z"))
    )
    (comp (ref "DS36")
      (value "LM1-PPG1-01-N1")
      (footprint "L#S/TLMK3210Z")
      (description "120-degree, 3.3 x 3.5-mm, SMT LED in green color with water-transparent lens")
      (fields (field (name "MANUFACTURER") "Cree") (field (name "SOURCE") "Marktech Optoelectronics"))
      (libsource (lib "API") (part "L#S/LM1PPG103N1Z"))
    )
    (comp (ref "DS37")
      (value "TLMK3210")
      (footprint "API:L#S/TLMK3210Z")
      (description "Vishay Red LED PLCC-3")
      (fields
        (field (name "MANUFACTURER") "Vishay")
        (field (name "MANUFACTURER PART NUMBER") "TLMK3210-GS08")
        (field (name "SOURCE") "Future")
      )
      (libsource (lib "API") (part "L#S/TLMK3210"))
    )
    (comp (ref "DS38")
      (value "TLMK3210")
      (footprint "API:L#S/TLMK3210Z")
      (description "Vishay Red LED PLCC-3")
      (fields
        (field (name "MANUFACTURER") "Vishay")
        (field (name "MANUFACTURER PART NUMBER") "TLMK3210-GS08")
        (field (name "SOURCE") "Future")
      )
      (libsource (lib "API") (part "L#S/TLMK3210"))
    )
    (comp (ref "DS39")
      (value "LM1-PPG1-01-N1")
      (footprint "L#S/TLMK3210Z")
      (description "120-degree, 3.3 x 3.5-mm, SMT LED in green color with water-transparent lens")
      (fields (field (name "MANUFACTURER") "Cree") (field (name "SOURCE") "Marktech Optoelectronics"))
      (libsource (lib "API") (part "L#S/LM1PPG103N1Z"))
    )
    (comp (ref "DS40")
      (value "LM1-PPG1-01-N1")
      (footprint "L#S/TLMK3210Z")
      (description "120-degree, 3.3 x 3.5-mm, SMT LED in green color with water-transparent lens")
      (fields (field (name "MANUFACTURER") "Cree") (field (name "SOURCE") "Marktech Optoelectronics"))
      (libsource (lib "API") (part "L#S/LM1PPG103N1Z"))
    )
    (comp (ref "DS41")
      (value "TLMK3210")
      (footprint "API:L#S/TLMK3210Z")
      (description "Vishay Red LED PLCC-3")
      (fields
        (field (name "MANUFACTURER") "Vishay")
        (field (name "MANUFACTURER PART NUMBER") "TLMK3210-GS08")
        (field (name "SOURCE") "Future")
      )
      (libsource (lib "API") (part "L#S/TLMK3210"))
    )
    (comp (ref "DS42")
      (value "TLMK3210")
      (footprint "API:L#S/TLMK3210Z")
      (description "Vishay Red LED PLCC-3")
      (fields
        (field (name "MANUFACTURER") "Vishay")
        (field (name "MANUFACTURER PART NUMBER") "TLMK3210-GS08")
        (field (name "SOURCE") "Future")
      )
      (libsource (lib "API") (part "L#S/TLMK3210"))
    )
    (comp (ref "DS43")
      (value "LM1-PPG1-01-N1")
      (footprint "L#S/TLMK3210Z")
      (description "120-degree, 3.3 x 3.5-mm, SMT LED in green color with water-transparent lens")
      (fields (field (name "MANUFACTURER") "Cree") (field (name "SOURCE") "Marktech Optoelectronics"))
      (libsource (lib "API") (part "L#S/LM1PPG103N1Z"))
    )
    (comp (ref "DS44")
      (value "LM1-PPG1-01-N1")
      (footprint "L#S/TLMK3210Z")
      (description "120-degree, 3.3 x 3.5-mm, SMT LED in green color with water-transparent lens")
      (fields (field (name "MANUFACTURER") "Cree") (field (name "SOURCE") "Marktech Optoelectronics"))
      (libsource (lib "API") (part "L#S/LM1PPG103N1Z"))
    )
    (comp (ref "DS45")
      (value "TLMK3210")
      (footprint "API:L#S/TLMK3210Z")
      (description "Vishay Red LED PLCC-3")
      (fields
        (field (name "MANUFACTURER") "Vishay")
        (field (name "MANUFACTURER PART NUMBER") "TLMK3210-GS08")
        (field (name "SOURCE") "Future")
      )
      (libsource (lib "API") (part "L#S/TLMK3210"))
    )
    (comp (ref "DS46")
      (value "TLMK3210")
      (footprint "API:L#S/TLMK3210Z")
      (description "Vishay Red LED PLCC-3")
      (fields
        (field (name "MANUFACTURER") "Vishay")
        (field (name "MANUFACTURER PART NUMBER") "TLMK3210-GS08")
        (field (name "SOURCE") "Future")
      )
      (libsource (lib "API") (part "L#S/TLMK3210"))
    )
    (comp (ref "DS47")
      (value "LM1-PPG1-01-N1")
      (footprint "L#S/TLMK3210Z")
      (description "120-degree, 3.3 x 3.5-mm, SMT LED in green color with water-transparent lens")
      (fields (field (name "MANUFACTURER") "Cree") (field (name "SOURCE") "Marktech Optoelectronics"))
      (libsource (lib "API") (part "L#S/LM1PPG103N1Z"))
    )
    (comp (ref "DS48")
      (value "LM1-PPG1-01-N1")
      (footprint "L#S/TLMK3210Z")
      (description "120-degree, 3.3 x 3.5-mm, SMT LED in green color with water-transparent lens")
      (fields (field (name "MANUFACTURER") "Cree") (field (name "SOURCE") "Marktech Optoelectronics"))
      (libsource (lib "API") (part "L#S/LM1PPG103N1Z"))
    )
    (comp (ref "DS49")
      (value "RED LED T1-3/4")
      (footprint "LED T1-3/4 Flush")
      (description "LED 631NM TAPERED RED 5MM")
      (fields
        (field (name "MANUFACTURER") "TT Electronics/Optek Technology")
        (field (name "MANUFACTURER PART NUMBER") "OVLGS0C8B9")
        (field (name "SOURCE") "Digikey")
      )
      (libsource (lib "API") (part "LRCOVLFR3C7Z"))
    )
    (comp (ref "DS50")
      (value "GREEN T1-3/4")
      (footprint "LED T1-3/4 Flush")
      (description "LED 525NM ROUND GREEN 5MM")
      (fields
        (field (name "MANUFACTURER") "TT Electronics/Optek Technology")
        (field (name "MANUFACTURER PART NUMBER") "OVLFG3C7")
        (field (name "SOURCE") "Digikey")
      )
      (libsource (lib "API") (part "LGCOVLFG3C7Z"))
    )
    (comp (ref "FID1")
      (value "Fiducial")
      (footprint "Fiducial")
      (fields
        (field (name "MANUFACTURER") "Manufacturer")
        (field (name "MANUFACTURER PART NUMBER") "Manufacturer Part Number")
      )
      (libsource (lib "API") (part "Fiducial"))
    )
    (comp (ref "FID2")
      (value "Fiducial")
      (footprint "Fiducial")
      (fields
        (field (name "MANUFACTURER") "Manufacturer")
        (field (name "MANUFACTURER PART NUMBER") "Manufacturer Part Number")
      )
      (libsource (lib "API") (part "Fiducial"))
    )
    (comp (ref "FID3")
      (value "Fiducial")
      (footprint "Fiducial")
      (fields
        (field (name "MANUFACTURER") "Manufacturer")
        (field (name "MANUFACTURER PART NUMBER") "Manufacturer Part Number")
      )
      (libsource (lib "API") (part "Fiducial"))
    )
    (comp (ref "FID4")
      (value "Fiducial")
      (footprint "Fiducial")
      (fields
        (field (name "MANUFACTURER") "Manufacturer")
        (field (name "MANUFACTURER PART NUMBER") "Manufacturer Part Number")
      )
      (libsource (lib "API") (part "Fiducial"))
    )
    (comp (ref "FID5")
      (value "Fiducial")
      (footprint "Fiducial")
      (fields
        (field (name "MANUFACTURER") "Manufacturer")
        (field (name "MANUFACTURER PART NUMBER") "Manufacturer Part Number")
      )
      (libsource (lib "API") (part "Fiducial"))
    )
    (comp (ref "FID6")
      (value "Fiducial")
      (footprint "Fiducial")
      (fields
        (field (name "MANUFACTURER") "Manufacturer")
        (field (name "MANUFACTURER PART NUMBER") "Manufacturer Part Number")
      )
      (libsource (lib "API") (part "Fiducial"))
    )
    (comp (ref "FID7")
      (value "Fiducial")
      (footprint "Fiducial")
      (fields
        (field (name "MANUFACTURER") "Manufacturer")
        (field (name "MANUFACTURER PART NUMBER") "Manufacturer Part Number")
      )
      (libsource (lib "API") (part "Fiducial"))
    )
    (comp (ref "FID8")
      (value "Fiducial")
      (footprint "Fiducial")
      (fields
        (field (name "MANUFACTURER") "Manufacturer")
        (field (name "MANUFACTURER PART NUMBER") "Manufacturer Part Number")
      )
      (libsource (lib "API") (part "Fiducial"))
    )
    (comp (ref "J1")
      (value "*")
      (footprint "API:WIRE_125")
      (fields
        (field (name "MANUFACTURER") "Manufacturer")
        (field (name "MANUFACTURER PART NUMBER") "Manufacturer Part Number")
      )
      (libsource (lib "API") (part "~125_WIRE"))
    )
    (comp (ref "J2")
      (value "*")
      (footprint "API:WIRE_125")
      (fields
        (field (name "MANUFACTURER") "Manufacturer")
        (field (name "MANUFACTURER PART NUMBER") "Manufacturer Part Number")
      )
      (libsource (lib "API") (part "~125_WIRE"))
    )
    (comp (ref "J3")
      (value "*")
      (footprint "API:WIRE_125")
      (fields
        (field (name "MANUFACTURER") "Manufacturer")
        (field (name "MANUFACTURER PART NUMBER") "Manufacturer Part Number")
      )
      (libsource (lib "API") (part "~125_WIRE"))
    )
    (comp (ref "J4")
      (value "*")
      (footprint "API:WIRE_125")
      (fields
        (field (name "MANUFACTURER") "Manufacturer")
        (field (name "MANUFACTURER PART NUMBER") "Manufacturer Part Number")
      )
      (libsource (lib "API") (part "~125_WIRE"))
    )
    (comp (ref "J5")
      (value "*")
      (footprint "API:WIRE_125")
      (fields
        (field (name "MANUFACTURER") "Manufacturer")
        (field (name "MANUFACTURER PART NUMBER") "Manufacturer Part Number")
      )
      (libsource (lib "API") (part "~125_WIRE"))
    )
    (comp (ref "J6")
      (value "*")
      (footprint "API:WIRE_125")
      (fields
        (field (name "MANUFACTURER") "Manufacturer")
        (field (name "MANUFACTURER PART NUMBER") "Manufacturer Part Number")
      )
      (libsource (lib "API") (part "~125_WIRE"))
    )
    (comp (ref "J7")
      (value "*")
      (footprint "API:WIRE_125")
      (fields
        (field (name "MANUFACTURER") "Manufacturer")
        (field (name "MANUFACTURER PART NUMBER") "Manufacturer Part Number")
      )
      (libsource (lib "API") (part "~125_WIRE"))
    )
    (comp (ref "J8")
      (value "*")
      (footprint "API:WIRE_125")
      (fields
        (field (name "MANUFACTURER") "Manufacturer")
        (field (name "MANUFACTURER PART NUMBER") "Manufacturer Part Number")
      )
      (libsource (lib "API") (part "~125_WIRE"))
    )
    (comp (ref "J9")
      (value "*")
      (footprint "API:WIRE_125")
      (fields
        (field (name "MANUFACTURER") "Manufacturer")
        (field (name "MANUFACTURER PART NUMBER") "Manufacturer Part Number")
      )
      (libsource (lib "") (part "~125_WIRE_1"))
    )
    (comp (ref "J10")
      (value "*")
      (footprint "API:WIRE_125")
      (fields
        (field (name "MANUFACTURER") "Manufacturer")
        (field (name "MANUFACTURER PART NUMBER") "Manufacturer Part Number")
      )
      (libsource (lib "") (part "~125_WIRE_1"))
    )
    (comp (ref "J11")
      (value "*")
      (footprint "API:WIRE_125")
      (fields
        (field (name "MANUFACTURER") "Manufacturer")
        (field (name "MANUFACTURER PART NUMBER") "Manufacturer Part Number")
      )
      (libsource (lib "API") (part "~125_WIRE"))
    )
    (comp (ref "J12")
      (value "*")
      (footprint "API:WIRE_125")
      (fields
        (field (name "MANUFACTURER") "Manufacturer")
        (field (name "MANUFACTURER PART NUMBER") "Manufacturer Part Number")
      )
      (libsource (lib "API") (part "~125_WIRE"))
    )
    (comp (ref "J13")
      (value "KUSBVX-BS1N-B")
      (footprint "KUSBVX-BS1N")
      (description "USB Connectors B TYPE VERT BLK SKT")
      (fields (field (name "MANUFACTURER") "Kycon") (field (name "SOURCE") "Mouser"))
      (libsource (lib "AMP Serial Bus USB") (part "787834-2"))
    )
    (comp (ref "J14")
      (value "Phoenix Contact 1755778")
      (footprint "JCPM5086VE0Z")
      (description "CONN HEADER VERT 6POS 5.08MM")
      (fields
        (field (name "MANUFACTURER") "Phoenix Contact")
        (field (name "MANUFACTURER PART NUMBER") "1755778")
        (field (name "SOURCE") "Digikey")
      )
      (libsource (lib "API") (part "JCPM5086VE0Z"))
    )
    (comp (ref "JP1")
      (value "0 Ohm Config")
      (description "RES 0.0 OHM 1/8W 5% 0805 SMD")
      (fields
        (field (name "MANUFACTURER") "Panasonic - ECG")
        (field (name "MANUFACTURER PART NUMBER") "ERJ-6GEY0R00V")
        (field (name "SOURCE") "Digikey")
      )
      (libsource (lib "API") (part "RS/ERJ6ENF"))
    )
    (comp (ref "JP2")
      (value "0 Ohm Config")
      (description "RES 0.0 OHM 1/8W 5% 0805 SMD")
      (fields
        (field (name "MANUFACTURER") "Panasonic - ECG")
        (field (name "MANUFACTURER PART NUMBER") "ERJ-6GEY0R00V")
        (field (name "SOURCE") "Digikey")
      )
      (libsource (lib "API") (part "RS/ERJ6ENF"))
    )
    (comp (ref "JP3")
      (value "0 Ohm Config")
      (description "RES 0.0 OHM 1/8W 5% 0805 SMD")
      (fields
        (field (name "MANUFACTURER") "Panasonic - ECG")
        (field (name "MANUFACTURER PART NUMBER") "ERJ-6GEY0R00V")
        (field (name "SOURCE") "Digikey")
      )
      (libsource (lib "API") (part "RS/ERJ6ENF"))
    )
    (comp (ref "JP4")
      (value "0 Ohm Config")
      (footprint "0805")
      (description "RES 0.0 OHM 1/8W 5% 0805 SMD")
      (fields
        (field (name "MANUFACTURER") "Panasonic - ECG")
        (field (name "MANUFACTURER PART NUMBER") "ERJ-6GEY0R00V")
        (field (name "SOURCE") "Digikey")
      )
      (libsource (lib "API") (part "RS/ERJ6ENF"))
    )
    (comp (ref "L1")
      (value "33uH 3A")
      (footprint "API:IND/DO5022")
      (description "33uH 3A Surface Mount Inductor")
      (fields
        (field (name "MANUFACTURER") "CoilCraft")
        (field (name "MANUFACTURER PART NUMBER") "DO5022P-333MLB")
      )
      (libsource (lib "API") (part "N#S/DO5022P333Z"))
    )
    (comp (ref "L2")
      (value "33uH 3A")
      (footprint "API:IND/DO5022")
      (description "33uH 3A Surface Mount Inductor")
      (fields
        (field (name "MANUFACTURER") "CoilCraft")
        (field (name "MANUFACTURER PART NUMBER") "DO5022P-333MLB")
      )
      (libsource (lib "API") (part "N#S/DO5022P333Z"))
    )
    (comp (ref "M1")
      (value "Mounting Hole 1/4\" Screw")
      (footprint "MHole250")
      (fields
        (field (name "MANUFACTURER") "Manufacturer")
        (field (name "MANUFACTURER PART NUMBER") "Manufacturer Part Number")
      )
      (libsource (lib "Rays_Altium") (part "MountingHole_1/4"))
    )
    (comp (ref "M2")
      (value "Mounting Hole 1/4\" Screw")
      (footprint "MHole250")
      (fields
        (field (name "MANUFACTURER") "Manufacturer")
        (field (name "MANUFACTURER PART NUMBER") "Manufacturer Part Number")
      )
      (libsource (lib "Rays_Altium") (part "MountingHole_1/4"))
    )
    (comp (ref "M3")
      (value "Mounting Hole 1/4\" Screw")
      (footprint "MHole250")
      (fields
        (field (name "MANUFACTURER") "Manufacturer")
        (field (name "MANUFACTURER PART NUMBER") "Manufacturer Part Number")
      )
      (libsource (lib "Rays_Altium") (part "MountingHole_1/4"))
    )
    (comp (ref "M4")
      (value "Mounting Hole 1/4\" Screw")
      (footprint "MHole250")
      (fields
        (field (name "MANUFACTURER") "Manufacturer")
        (field (name "MANUFACTURER PART NUMBER") "Manufacturer Part Number")
      )
      (libsource (lib "Rays_Altium") (part "MountingHole_1/4"))
    )
    (comp (ref "M5")
      (value "Mounting Hole #8 Screw")
      (footprint "MHole#8")
      (fields
        (field (name "MANUFACTURER") "Manufacturer")
        (field (name "MANUFACTURER PART NUMBER") "Manufacturer Part Number")
      )
      (libsource (lib "Rays_Altium") (part "MountingHole_8"))
    )
    (comp (ref "M6")
      (value "Mounting Hole #8 Screw")
      (footprint "MHole#8")
      (fields
        (field (name "MANUFACTURER") "Manufacturer")
        (field (name "MANUFACTURER PART NUMBER") "Manufacturer Part Number")
      )
      (libsource (lib "Rays_Altium") (part "MountingHole_8"))
    )
    (comp (ref "M7")
      (value "Mounting Hole #8 Screw")
      (footprint "MHole#8")
      (fields
        (field (name "MANUFACTURER") "Manufacturer")
        (field (name "MANUFACTURER PART NUMBER") "Manufacturer Part Number")
      )
      (libsource (lib "Rays_Altium") (part "MountingHole_8"))
    )
    (comp (ref "M8")
      (value "Mounting Hole #8 Screw")
      (footprint "MHole#8")
      (fields
        (field (name "MANUFACTURER") "Manufacturer")
        (field (name "MANUFACTURER PART NUMBER") "Manufacturer Part Number")
      )
      (libsource (lib "Rays_Altium") (part "MountingHole_8"))
    )
    (comp (ref "M9")
      (value "Mounting Hole #8 Screw")
      (footprint "MHole#8")
      (fields
        (field (name "MANUFACTURER") "Manufacturer")
        (field (name "MANUFACTURER PART NUMBER") "Manufacturer Part Number")
      )
      (libsource (lib "Rays_Altium") (part "MountingHole_8"))
    )
    (comp (ref "M10")
      (value "Mounting Hole #8 Screw")
      (footprint "MHole#8")
      (fields
        (field (name "MANUFACTURER") "Manufacturer")
        (field (name "MANUFACTURER PART NUMBER") "Manufacturer Part Number")
      )
      (libsource (lib "Rays_Altium") (part "MountingHole_8"))
    )
    (comp (ref "Q1")
      (value "FDS8884")
      (footprint "SO8")
      (description "MOSFET N-CH 30V 8.5A 8-SOIC")
      (fields (field (name "MANUFACTURER") "Fairchild Semiconductor") (field (name "SOURCE") "Digikey"))
      (libsource (lib "API") (part "Q#S/FDS8884F"))
    )
    (comp (ref "Q2")
      (value "FDS8884")
      (footprint "SO8")
      (description "MOSFET N-CH 30V 8.5A 8-SOIC")
      (fields (field (name "MANUFACTURER") "Fairchild Semiconductor") (field (name "SOURCE") "Digikey"))
      (libsource (lib "API") (part "Q#S/FDS8884F"))
    )
    (comp (ref "R1")
      (value "100K 1%")
      (footprint "R0805")
      (description "RES 100K OHM 1/8W 1% 0805 SMD")
      (fields
        (field (name "MANUFACTURER") "Panasonic - ECG")
        (field (name "MANUFACTURER PART NUMBER") "RC0805JR-07100KL")
        (field (name "SOURCE") "Digikey")
      )
      (libsource (lib "API") (part "RS/ERJ6ENF"))
    )
    (comp (ref "R2")
      (value "100K 1%")
      (footprint "R0805")
      (description "RES 100K OHM 1/8W 1% 0805 SMD")
      (fields
        (field (name "MANUFACTURER") "Panasonic - ECG")
        (field (name "MANUFACTURER PART NUMBER") "RC0805JR-07100KL")
        (field (name "SOURCE") "Digikey")
      )
      (libsource (lib "API") (part "RS/ERJ6ENF"))
    )
    (comp (ref "R3")
      (value "100K 1%")
      (footprint "R0805")
      (description "RES 100K OHM 1/8W 1% 0805 SMD")
      (fields
        (field (name "MANUFACTURER") "Panasonic - ECG")
        (field (name "MANUFACTURER PART NUMBER") "RC0805JR-07100KL")
        (field (name "SOURCE") "Digikey")
      )
      (libsource (lib "API") (part "RS/ERJ6ENF"))
    )
    (comp (ref "R4")
      (value "10.0k 1%")
      (footprint "R0805")
      (description "RES 10.0K OHM 1/8W 1% 0805 SMD")
      (fields
        (field (name "MANUFACTURER") "Panasonic - ECG")
        (field (name "MANUFACTURER PART NUMBER") "ERJ-6ENF1002V")
        (field (name "SOURCE") "Digikey")
      )
      (libsource (lib "API") (part "RS/ERJ6ENF"))
    )
    (comp (ref "R5")
      (value "121 1%")
      (footprint "R1206")
      (description "RES 121 OHM 1/4W 1% 1206 SMD")
      (fields
        (field (name "MANUFACTURER") "Panasonic - ECG")
        (field (name "MANUFACTURER PART NUMBER") "ERJ-8ENF1210V")
        (field (name "SOURCE") "Digikey")
      )
      (libsource (lib "API") (part "RS/ERJ8ENF"))
    )
    (comp (ref "R6")
      (value "100K 1%")
      (footprint "R0805")
      (description "RES 100K OHM 1/8W 1% 0805 SMD")
      (fields
        (field (name "MANUFACTURER") "Panasonic - ECG")
        (field (name "MANUFACTURER PART NUMBER") "RC0805JR-07100KL")
        (field (name "SOURCE") "Digikey")
      )
      (libsource (lib "API") (part "RS/ERJ6ENF"))
    )
    (comp (ref "R7")
      (value "1.0k 1%")
      (footprint "R0805")
      (description "RES 1.00K OHM 1/8W 1% 0805 SMD")
      (fields
        (field (name "MANUFACTURER") "Yageo")
        (field (name "MANUFACTURER PART NUMBER") "RC0805FR-071KL")
        (field (name "SOURCE") "Digikey")
      )
      (libsource (lib "API") (part "RS/ERJ6ENF"))
    )
    (comp (ref "R8")
      (value "0")
      (footprint "R0805")
      (description "RES 0.0 OHM 1/8W 5% 0805 SMD")
      (fields
        (field (name "MANUFACTURER") "Panasonic - ECG")
        (field (name "MANUFACTURER PART NUMBER") "ERJ-6GEY0R00V")
        (field (name "SOURCE") "Digikey")
      )
      (libsource (lib "API") (part "RS/ERJ6GEYJ"))
    )
    (comp (ref "R9")
      (value "3.16K 1%")
      (footprint "R0805")
      (description "RES 3.16K OHM 1/8W 1% 0805 SMD")
      (fields
        (field (name "MANUFACTURER") "Panasonic - ECG")
        (field (name "MANUFACTURER PART NUMBER") "ERJ-6ENF3161V")
        (field (name "SOURCE") "Digikey")
      )
      (libsource (lib "API") (part "RS/ERJ6ENF"))
    )
    (comp (ref "R10")
      (value "100K 1%")
      (footprint "R0805")
      (description "RES 100K OHM 1/8W 1% 0805 SMD")
      (fields
        (field (name "MANUFACTURER") "Panasonic - ECG")
        (field (name "MANUFACTURER PART NUMBER") "RC0805JR-07100KL")
        (field (name "SOURCE") "Digikey")
      )
      (libsource (lib "API") (part "RS/ERJ6ENF"))
    )
    (comp (ref "R11")
      (value "10.0k 1%")
      (footprint "R0805")
      (description "RES 10.0K OHM 1/8W 1% 0805 SMD")
      (fields
        (field (name "MANUFACTURER") "Panasonic - ECG")
        (field (name "MANUFACTURER PART NUMBER") "ERJ-6ENF1002V")
        (field (name "SOURCE") "Digikey")
      )
      (libsource (lib "API") (part "RS/ERJ6ENF"))
    )
    (comp (ref "R12")
      (value "499 1%")
      (footprint "R0805")
      (description "RES 499 OHM 1/8W 1% 0805 SMD")
      (fields
        (field (name "MANUFACTURER") "Panasonic - ECG")
        (field (name "MANUFACTURER PART NUMBER") "ERJ-6ENF4990V")
        (field (name "SOURCE") "Digikey")
      )
      (libsource (lib "API") (part "RS/ERJ6ENF"))
    )
    (comp (ref "R13")
      (value "3.32k 1%")
      (footprint "R0805")
      (description "RES 3.32K OHM 1/8W 1% 0805 SMD")
      (fields
        (field (name "MANUFACTURER") "Panasonic - ECG")
        (field (name "MANUFACTURER PART NUMBER") "ERJ-6ENF3321V")
        (field (name "SOURCE") "Digikey")
      )
      (libsource (lib "API") (part "RS/ERJ6ENF"))
    )
    (comp (ref "R14")
      (value "100K 1%")
      (footprint "R0805")
      (description "RES 100K OHM 1/8W 1% 0805 SMD")
      (fields
        (field (name "MANUFACTURER") "Panasonic - ECG")
        (field (name "MANUFACTURER PART NUMBER") "RC0805JR-07100KL")
        (field (name "SOURCE") "Digikey")
      )
      (libsource (lib "API") (part "RS/ERJ6ENF"))
    )
    (comp (ref "R15")
      (value "47.5k 1%")
      (footprint "R0805")
      (description "RES 47.5K OHM 1/8W 1% 0805 SMD")
      (fields
        (field (name "MANUFACTURER") "Panasonic - ECG")
        (field (name "MANUFACTURER PART NUMBER") "ERJ-6ENF4752V")
        (field (name "SOURCE") "Digikey")
      )
      (libsource (lib "API") (part "RS/ERJ6ENF"))
    )
    (comp (ref "R16")
      (value "20.0k 1%")
      (footprint "R0805")
      (description "RES 20.0K OHM 1/8W 1% 0805 SMD")
      (fields
        (field (name "MANUFACTURER") "Panasonic - ECG")
        (field (name "MANUFACTURER PART NUMBER") "ERJ-6ENF2002V")
        (field (name "SOURCE") "Digikey")
      )
      (libsource (lib "API") (part "RS/ERJ6ENF"))
    )
    (comp (ref "R17")
      (value "1.0k 1%")
      (footprint "R0805")
      (description "RES 1.00K OHM 1/8W 1% 0805 SMD")
      (fields
        (field (name "MANUFACTURER") "Yageo")
        (field (name "MANUFACTURER PART NUMBER") "RC0805FR-071KL")
        (field (name "SOURCE") "Digikey")
      )
      (libsource (lib "API") (part "RS/ERJ6ENF"))
    )
    (comp (ref "R18")
      (value "1.65K 1%")
      (footprint "R0805")
      (description "RES 1.65K OHM 1/8W 1% 0805 SMD")
      (fields
        (field (name "MANUFACTURER PART NUMBER") "ERJ-6ENF1651V")
        (field (name "MANUFACTURER") "Panasonic - ECG")
        (field (name "SOURCE") "Digikey")
      )
      (libsource (lib "API") (part "RS/ERJ6ENF"))
    )
    (comp (ref "R19")
      (value "100K 1%")
      (footprint "R0805")
      (description "RES 100K OHM 1/8W 1% 0805 SMD")
      (fields
        (field (name "MANUFACTURER") "Panasonic - ECG")
        (field (name "MANUFACTURER PART NUMBER") "RC0805JR-07100KL")
        (field (name "SOURCE") "Digikey")
      )
      (libsource (lib "API") (part "RS/ERJ6ENF"))
    )
    (comp (ref "R20")
      (value "10.0k 1%")
      (footprint "R0805")
      (description "RES 10.0K OHM 1/8W 1% 0805 SMD")
      (fields
        (field (name "MANUFACTURER") "Panasonic - ECG")
        (field (name "MANUFACTURER PART NUMBER") "ERJ-6ENF1002V")
        (field (name "SOURCE") "Digikey")
      )
      (libsource (lib "API") (part "RS/ERJ6ENF"))
    )
    (comp (ref "R21")
      (value "100K 1%")
      (footprint "R0805")
      (description "RES 100K OHM 1/8W 1% 0805 SMD")
      (fields
        (field (name "MANUFACTURER") "Panasonic - ECG")
        (field (name "MANUFACTURER PART NUMBER") "RC0805JR-07100KL")
        (field (name "SOURCE") "Digikey")
      )
      (libsource (lib "API") (part "RS/ERJ6ENF"))
    )
    (comp (ref "R22")
      (value "0")
      (footprint "R0805")
      (description "RES 0.0 OHM 1/8W 5% 0805 SMD")
      (fields
        (field (name "MANUFACTURER") "Panasonic - ECG")
        (field (name "MANUFACTURER PART NUMBER") "ERJ-6GEY0R00V")
        (field (name "SOURCE") "Digikey")
      )
      (libsource (lib "API") (part "RS/ERJ6GEYJ"))
    )
    (comp (ref "R23")
      (value "100K 1%")
      (footprint "R0805")
      (description "RES 100K OHM 1/8W 1% 0805 SMD")
      (fields
        (field (name "MANUFACTURER") "Panasonic - ECG")
        (field (name "MANUFACTURER PART NUMBER") "RC0805JR-07100KL")
        (field (name "SOURCE") "Digikey")
      )
      (libsource (lib "API") (part "RS/ERJ6ENF"))
    )
    (comp (ref "R24")
      (value "7.50k 1%")
      (footprint "R0805")
      (description "RES 7.50K OHM 1/8W 1% 0805 SMD")
      (fields
        (field (name "MANUFACTURER") "Panasonic - ECG")
        (field (name "MANUFACTURER PART NUMBER") "ERJ-6ENF7501V")
        (field (name "SOURCE") "Digikey")
      )
      (libsource (lib "API") (part "RS/ERJ6ENF"))
    )
    (comp (ref "R25")
      (value "2.49k 1%")
      (description "RES 2.49K OHM 1/8W 1% 0805 SMD")
      (fields
        (field (name "MANUFACTURER") "Panasonic - ECG")
        (field (name "MANUFACTURER PART NUMBER") "ERJ-6ENF2491V")
        (field (name "SOURCE") "Digikey")
      )
      (libsource (lib "API") (part "RS/ERJ6ENF"))
    )
    (comp (ref "R26")
      (value "100K 1%")
      (footprint "R0805")
      (description "RES 100K OHM 1/8W 1% 0805 SMD")
      (fields
        (field (name "MANUFACTURER") "Panasonic - ECG")
        (field (name "MANUFACTURER PART NUMBER") "RC0805JR-07100KL")
        (field (name "SOURCE") "Digikey")
      )
      (libsource (lib "API") (part "RS/ERJ6ENF"))
    )
    (comp (ref "R27")
      (value "100K 1%")
      (footprint "R0805")
      (description "RES 100K OHM 1/8W 1% 0805 SMD")
      (fields
        (field (name "MANUFACTURER") "Panasonic - ECG")
        (field (name "MANUFACTURER PART NUMBER") "RC0805JR-07100KL")
        (field (name "SOURCE") "Digikey")
      )
      (libsource (lib "API") (part "RS/ERJ6ENF"))
    )
    (comp (ref "R28")
      (value "10.0k 1%")
      (footprint "R0805")
      (description "RES 10.0K OHM 1/8W 1% 0805 SMD")
      (fields
        (field (name "MANUFACTURER") "Panasonic - ECG")
        (field (name "MANUFACTURER PART NUMBER") "ERJ-6ENF1002V")
        (field (name "SOURCE") "Digikey")
      )
      (libsource (lib "API") (part "RS/ERJ6ENF"))
    )
    (comp (ref "R29")
      (value "0")
      (footprint "R0805")
      (description "RES 0.0 OHM 1/8W 5% 0805 SMD")
      (fields
        (field (name "MANUFACTURER") "Panasonic - ECG")
        (field (name "MANUFACTURER PART NUMBER") "ERJ-6GEY0R00V")
        (field (name "SOURCE") "Digikey")
      )
      (libsource (lib "API") (part "RS/ERJ6GEYJ"))
    )
    (comp (ref "R30")
      (value "100K 1%")
      (footprint "R0805")
      (description "RES 100K OHM 1/8W 1% 0805 SMD")
      (fields
        (field (name "MANUFACTURER") "Panasonic - ECG")
        (field (name "MANUFACTURER PART NUMBER") "RC0805JR-07100KL")
        (field (name "SOURCE") "Digikey")
      )
      (libsource (lib "API") (part "RS/ERJ6ENF"))
    )
    (comp (ref "R40")
      (value "10.0k 1%")
      (footprint "R0805")
      (description "RES 10.0K OHM 1/8W 1% 0805 SMD")
      (fields
        (field (name "MANUFACTURER") "Panasonic - ECG")
        (field (name "MANUFACTURER PART NUMBER") "ERJ-6ENF1002V")
        (field (name "SOURCE") "Digikey")
      )
      (libsource (lib "API") (part "RS/ERJ6ENF"))
    )
    (comp (ref "R46")
      (value "15.0 OHM 1%")
      (footprint "R1206")
      (description "RES 15.0 OHM 1/4W 1% 1206 SMD")
      (fields
        (field (name "MANUFACTURER") "Panasonic - ECG")
        (field (name "MANUFACTURER PART NUMBER") "ERJ-8ENF15R0V")
        (field (name "SOURCE") "Digikey")
      )
      (libsource (lib "API") (part "RS/ERJ8ENF"))
    )
    (comp (ref "R47")
      (value "15.0 OHM 1%")
      (footprint "R1206")
      (description "RES 15.0 OHM 1/4W 1% 1206 SMD")
      (fields
        (field (name "MANUFACTURER") "Panasonic - ECG")
        (field (name "MANUFACTURER PART NUMBER") "ERJ-8ENF15R0V")
        (field (name "SOURCE") "Digikey")
      )
      (libsource (lib "API") (part "RS/ERJ8ENF"))
    )
    (comp (ref "R48")
      (value "15.0 OHM 1%")
      (footprint "R1206")
      (description "RES 15.0 OHM 1/4W 1% 1206 SMD")
      (fields
        (field (name "MANUFACTURER") "Panasonic - ECG")
        (field (name "MANUFACTURER PART NUMBER") "ERJ-8ENF15R0V")
        (field (name "SOURCE") "Digikey")
      )
      (libsource (lib "API") (part "RS/ERJ8ENF"))
    )
    (comp (ref "R49")
      (value "15.0 OHM 1%")
      (footprint "R1206")
      (description "RES 15.0 OHM 1/4W 1% 1206 SMD")
      (fields
        (field (name "MANUFACTURER") "Panasonic - ECG")
        (field (name "MANUFACTURER PART NUMBER") "ERJ-8ENF15R0V")
        (field (name "SOURCE") "Digikey")
      )
      (libsource (lib "API") (part "RS/ERJ8ENF"))
    )
    (comp (ref "R50")
      (value "15.0 OHM 1%")
      (footprint "R1206")
      (description "RES 15.0 OHM 1/4W 1% 1206 SMD")
      (fields
        (field (name "MANUFACTURER") "Panasonic - ECG")
        (field (name "MANUFACTURER PART NUMBER") "ERJ-8ENF15R0V")
        (field (name "SOURCE") "Digikey")
      )
      (libsource (lib "API") (part "RS/ERJ8ENF"))
    )
    (comp (ref "R51")
      (value "15.0 OHM 1%")
      (footprint "R1206")
      (description "RES 15.0 OHM 1/4W 1% 1206 SMD")
      (fields
        (field (name "MANUFACTURER") "Panasonic - ECG")
        (field (name "MANUFACTURER PART NUMBER") "ERJ-8ENF15R0V")
        (field (name "SOURCE") "Digikey")
      )
      (libsource (lib "API") (part "RS/ERJ8ENF"))
    )
    (comp (ref "R52")
      (value "15.0 OHM 1%")
      (footprint "R1206")
      (description "RES 15.0 OHM 1/4W 1% 1206 SMD")
      (fields
        (field (name "MANUFACTURER") "Panasonic - ECG")
        (field (name "MANUFACTURER PART NUMBER") "ERJ-8ENF15R0V")
        (field (name "SOURCE") "Digikey")
      )
      (libsource (lib "API") (part "RS/ERJ8ENF"))
    )
    (comp (ref "R53")
      (value "15.0 OHM 1%")
      (footprint "R1206")
      (description "RES 15.0 OHM 1/4W 1% 1206 SMD")
      (fields
        (field (name "MANUFACTURER") "Panasonic - ECG")
        (field (name "MANUFACTURER PART NUMBER") "ERJ-8ENF15R0V")
        (field (name "SOURCE") "Digikey")
      )
      (libsource (lib "API") (part "RS/ERJ8ENF"))
    )
    (comp (ref "R54")
      (value "15.0 OHM 1%")
      (footprint "R1206")
      (description "RES 15.0 OHM 1/4W 1% 1206 SMD")
      (fields
        (field (name "MANUFACTURER") "Panasonic - ECG")
        (field (name "MANUFACTURER PART NUMBER") "ERJ-8ENF15R0V")
        (field (name "SOURCE") "Digikey")
      )
      (libsource (lib "API") (part "RS/ERJ8ENF"))
    )
    (comp (ref "R55")
      (value "15.0 OHM 1%")
      (footprint "R1206")
      (description "RES 15.0 OHM 1/4W 1% 1206 SMD")
      (fields
        (field (name "MANUFACTURER") "Panasonic - ECG")
        (field (name "MANUFACTURER PART NUMBER") "ERJ-8ENF15R0V")
        (field (name "SOURCE") "Digikey")
      )
      (libsource (lib "API") (part "RS/ERJ8ENF"))
    )
    (comp (ref "R56")
      (value "15.0 OHM 1%")
      (footprint "R1206")
      (description "RES 15.0 OHM 1/4W 1% 1206 SMD")
      (fields
        (field (name "MANUFACTURER") "Panasonic - ECG")
        (field (name "MANUFACTURER PART NUMBER") "ERJ-8ENF15R0V")
        (field (name "SOURCE") "Digikey")
      )
      (libsource (lib "API") (part "RS/ERJ8ENF"))
    )
    (comp (ref "R57")
      (value "15.0 OHM 1%")
      (footprint "R1206")
      (description "RES 15.0 OHM 1/4W 1% 1206 SMD")
      (fields
        (field (name "MANUFACTURER") "Panasonic - ECG")
        (field (name "MANUFACTURER PART NUMBER") "ERJ-8ENF15R0V")
        (field (name "SOURCE") "Digikey")
      )
      (libsource (lib "API") (part "RS/ERJ8ENF"))
    )
    (comp (ref "R58")
      (value "32.4 OHM 1%")
      (footprint "R1206")
      (description "RES 32.4 OHM 1/4W 1% 1206 SMD")
      (fields
        (field (name "MANUFACTURER") "Panasonic - ECG")
        (field (name "MANUFACTURER PART NUMBER") "ERJ-8ENF32R4V")
        (field (name "SOURCE") "Digikey")
      )
      (libsource (lib "API") (part "RS/ERJ8ENF"))
    )
    (comp (ref "R59")
      (value "32.4 OHM 1%")
      (footprint "R1206")
      (description "RES 32.4 OHM 1/4W 1% 1206 SMD")
      (fields
        (field (name "MANUFACTURER") "Panasonic - ECG")
        (field (name "MANUFACTURER PART NUMBER") "ERJ-8ENF32R4V")
        (field (name "SOURCE") "Digikey")
      )
      (libsource (lib "API") (part "RS/ERJ8ENF"))
    )
    (comp (ref "R60")
      (value "32.4 OHM 1%")
      (footprint "R1206")
      (description "RES 32.4 OHM 1/4W 1% 1206 SMD")
      (fields
        (field (name "MANUFACTURER") "Panasonic - ECG")
        (field (name "MANUFACTURER PART NUMBER") "ERJ-8ENF32R4V")
        (field (name "SOURCE") "Digikey")
      )
      (libsource (lib "API") (part "RS/ERJ8ENF"))
    )
    (comp (ref "R61")
      (value "32.4 OHM 1%")
      (footprint "R1206")
      (description "RES 32.4 OHM 1/4W 1% 1206 SMD")
      (fields
        (field (name "MANUFACTURER") "Panasonic - ECG")
        (field (name "MANUFACTURER PART NUMBER") "ERJ-8ENF32R4V")
        (field (name "SOURCE") "Digikey")
      )
      (libsource (lib "API") (part "RS/ERJ8ENF"))
    )
    (comp (ref "R62")
      (value "32.4 OHM 1%")
      (footprint "R1206")
      (description "RES 32.4 OHM 1/4W 1% 1206 SMD")
      (fields
        (field (name "MANUFACTURER") "Panasonic - ECG")
        (field (name "MANUFACTURER PART NUMBER") "ERJ-8ENF32R4V")
        (field (name "SOURCE") "Digikey")
      )
      (libsource (lib "API") (part "RS/ERJ8ENF"))
    )
    (comp (ref "R63")
      (value "32.4 OHM 1%")
      (footprint "R1206")
      (description "RES 32.4 OHM 1/4W 1% 1206 SMD")
      (fields
        (field (name "MANUFACTURER") "Panasonic - ECG")
        (field (name "MANUFACTURER PART NUMBER") "ERJ-8ENF32R4V")
        (field (name "SOURCE") "Digikey")
      )
      (libsource (lib "API") (part "RS/ERJ8ENF"))
    )
    (comp (ref "R64")
      (value "32.4 OHM 1%")
      (footprint "R1206")
      (description "RES 32.4 OHM 1/4W 1% 1206 SMD")
      (fields
        (field (name "MANUFACTURER") "Panasonic - ECG")
        (field (name "MANUFACTURER PART NUMBER") "ERJ-8ENF32R4V")
        (field (name "SOURCE") "Digikey")
      )
      (libsource (lib "API") (part "RS/ERJ8ENF"))
    )
    (comp (ref "R65")
      (value "32.4 OHM 1%")
      (footprint "R1206")
      (description "RES 32.4 OHM 1/4W 1% 1206 SMD")
      (fields
        (field (name "MANUFACTURER") "Panasonic - ECG")
        (field (name "MANUFACTURER PART NUMBER") "ERJ-8ENF32R4V")
        (field (name "SOURCE") "Digikey")
      )
      (libsource (lib "API") (part "RS/ERJ8ENF"))
    )
    (comp (ref "R66")
      (value "32.4 OHM 1%")
      (footprint "R1206")
      (description "RES 32.4 OHM 1/4W 1% 1206 SMD")
      (fields
        (field (name "MANUFACTURER") "Panasonic - ECG")
        (field (name "MANUFACTURER PART NUMBER") "ERJ-8ENF32R4V")
        (field (name "SOURCE") "Digikey")
      )
      (libsource (lib "API") (part "RS/ERJ8ENF"))
    )
    (comp (ref "R67")
      (value "32.4 OHM 1%")
      (footprint "R1206")
      (description "RES 32.4 OHM 1/4W 1% 1206 SMD")
      (fields
        (field (name "MANUFACTURER") "Panasonic - ECG")
        (field (name "MANUFACTURER PART NUMBER") "ERJ-8ENF32R4V")
        (field (name "SOURCE") "Digikey")
      )
      (libsource (lib "API") (part "RS/ERJ8ENF"))
    )
    (comp (ref "R68")
      (value "32.4 OHM 1%")
      (footprint "R1206")
      (description "RES 32.4 OHM 1/4W 1% 1206 SMD")
      (fields
        (field (name "MANUFACTURER") "Panasonic - ECG")
        (field (name "MANUFACTURER PART NUMBER") "ERJ-8ENF32R4V")
        (field (name "SOURCE") "Digikey")
      )
      (libsource (lib "API") (part "RS/ERJ8ENF"))
    )
    (comp (ref "R69")
      (value "32.4 OHM 1%")
      (footprint "R1206")
      (description "RES 32.4 OHM 1/4W 1% 1206 SMD")
      (fields
        (field (name "MANUFACTURER") "Panasonic - ECG")
        (field (name "MANUFACTURER PART NUMBER") "ERJ-8ENF32R4V")
        (field (name "SOURCE") "Digikey")
      )
      (libsource (lib "API") (part "RS/ERJ8ENF"))
    )
    (comp (ref "R88")
      (value "15.0 OHM 1%")
      (footprint "R1206")
      (description "RES 15.0 OHM 1/4W 1% 1206 SMD")
      (fields
        (field (name "MANUFACTURER") "Panasonic - ECG")
        (field (name "MANUFACTURER PART NUMBER") "ERJ-8ENF15R0V")
        (field (name "SOURCE") "Digikey")
      )
      (libsource (lib "API") (part "RS/ERJ8ENF"))
    )
    (comp (ref "R89")
      (value "15.0 OHM 1%")
      (footprint "R1206")
      (description "RES 15.0 OHM 1/4W 1% 1206 SMD")
      (fields
        (field (name "MANUFACTURER") "Panasonic - ECG")
        (field (name "MANUFACTURER PART NUMBER") "ERJ-8ENF15R0V")
        (field (name "SOURCE") "Digikey")
      )
      (libsource (lib "API") (part "RS/ERJ8ENF"))
    )
    (comp (ref "R90")
      (value "15.0 OHM 1%")
      (footprint "R1206")
      (description "RES 15.0 OHM 1/4W 1% 1206 SMD")
      (fields
        (field (name "MANUFACTURER") "Panasonic - ECG")
        (field (name "MANUFACTURER PART NUMBER") "ERJ-8ENF15R0V")
        (field (name "SOURCE") "Digikey")
      )
      (libsource (lib "API") (part "RS/ERJ8ENF"))
    )
    (comp (ref "R91")
      (value "15.0 OHM 1%")
      (footprint "R1206")
      (description "RES 15.0 OHM 1/4W 1% 1206 SMD")
      (fields
        (field (name "MANUFACTURER") "Panasonic - ECG")
        (field (name "MANUFACTURER PART NUMBER") "ERJ-8ENF15R0V")
        (field (name "SOURCE") "Digikey")
      )
      (libsource (lib "API") (part "RS/ERJ8ENF"))
    )
    (comp (ref "R92")
      (value "15.0 OHM 1%")
      (footprint "R1206")
      (description "RES 15.0 OHM 1/4W 1% 1206 SMD")
      (fields
        (field (name "MANUFACTURER") "Panasonic - ECG")
        (field (name "MANUFACTURER PART NUMBER") "ERJ-8ENF15R0V")
        (field (name "SOURCE") "Digikey")
      )
      (libsource (lib "API") (part "RS/ERJ8ENF"))
    )
    (comp (ref "R93")
      (value "15.0 OHM 1%")
      (footprint "R1206")
      (description "RES 15.0 OHM 1/4W 1% 1206 SMD")
      (fields
        (field (name "MANUFACTURER") "Panasonic - ECG")
        (field (name "MANUFACTURER PART NUMBER") "ERJ-8ENF15R0V")
        (field (name "SOURCE") "Digikey")
      )
      (libsource (lib "API") (part "RS/ERJ8ENF"))
    )
    (comp (ref "R94")
      (value "15.0 OHM 1%")
      (footprint "R1206")
      (description "RES 15.0 OHM 1/4W 1% 1206 SMD")
      (fields
        (field (name "MANUFACTURER") "Panasonic - ECG")
        (field (name "MANUFACTURER PART NUMBER") "ERJ-8ENF15R0V")
        (field (name "SOURCE") "Digikey")
      )
      (libsource (lib "API") (part "RS/ERJ8ENF"))
    )
    (comp (ref "R95")
      (value "15.0 OHM 1%")
      (footprint "R1206")
      (description "RES 15.0 OHM 1/4W 1% 1206 SMD")
      (fields
        (field (name "MANUFACTURER") "Panasonic - ECG")
        (field (name "MANUFACTURER PART NUMBER") "ERJ-8ENF15R0V")
        (field (name "SOURCE") "Digikey")
      )
      (libsource (lib "API") (part "RS/ERJ8ENF"))
    )
    (comp (ref "R96")
      (value "15.0 OHM 1%")
      (footprint "R1206")
      (description "RES 15.0 OHM 1/4W 1% 1206 SMD")
      (fields
        (field (name "MANUFACTURER") "Panasonic - ECG")
        (field (name "MANUFACTURER PART NUMBER") "ERJ-8ENF15R0V")
        (field (name "SOURCE") "Digikey")
      )
      (libsource (lib "API") (part "RS/ERJ8ENF"))
    )
    (comp (ref "R97")
      (value "15.0 OHM 1%")
      (footprint "R1206")
      (description "RES 15.0 OHM 1/4W 1% 1206 SMD")
      (fields
        (field (name "MANUFACTURER") "Panasonic - ECG")
        (field (name "MANUFACTURER PART NUMBER") "ERJ-8ENF15R0V")
        (field (name "SOURCE") "Digikey")
      )
      (libsource (lib "API") (part "RS/ERJ8ENF"))
    )
    (comp (ref "R98")
      (value "15.0 OHM 1%")
      (footprint "R1206")
      (description "RES 15.0 OHM 1/4W 1% 1206 SMD")
      (fields
        (field (name "MANUFACTURER") "Panasonic - ECG")
        (field (name "MANUFACTURER PART NUMBER") "ERJ-8ENF15R0V")
        (field (name "SOURCE") "Digikey")
      )
      (libsource (lib "API") (part "RS/ERJ8ENF"))
    )
    (comp (ref "R99")
      (value "15.0 OHM 1%")
      (footprint "R1206")
      (description "RES 15.0 OHM 1/4W 1% 1206 SMD")
      (fields
        (field (name "MANUFACTURER") "Panasonic - ECG")
        (field (name "MANUFACTURER PART NUMBER") "ERJ-8ENF15R0V")
        (field (name "SOURCE") "Digikey")
      )
      (libsource (lib "API") (part "RS/ERJ8ENF"))
    )
    (comp (ref "R100")
      (value "32.4 OHM 1%")
      (footprint "R1206")
      (description "RES 32.4 OHM 1/4W 1% 1206 SMD")
      (fields
        (field (name "MANUFACTURER") "Panasonic - ECG")
        (field (name "MANUFACTURER PART NUMBER") "ERJ-8ENF32R4V")
        (field (name "SOURCE") "Digikey")
      )
      (libsource (lib "API") (part "RS/ERJ8ENF"))
    )
    (comp (ref "R101")
      (value "32.4 OHM 1%")
      (footprint "R1206")
      (description "RES 32.4 OHM 1/4W 1% 1206 SMD")
      (fields
        (field (name "MANUFACTURER") "Panasonic - ECG")
        (field (name "MANUFACTURER PART NUMBER") "ERJ-8ENF32R4V")
        (field (name "SOURCE") "Digikey")
      )
      (libsource (lib "API") (part "RS/ERJ8ENF"))
    )
    (comp (ref "R102")
      (value "32.4 OHM 1%")
      (footprint "R1206")
      (description "RES 32.4 OHM 1/4W 1% 1206 SMD")
      (fields
        (field (name "MANUFACTURER") "Panasonic - ECG")
        (field (name "MANUFACTURER PART NUMBER") "ERJ-8ENF32R4V")
        (field (name "SOURCE") "Digikey")
      )
      (libsource (lib "API") (part "RS/ERJ8ENF"))
    )
    (comp (ref "R103")
      (value "32.4 OHM 1%")
      (footprint "R1206")
      (description "RES 32.4 OHM 1/4W 1% 1206 SMD")
      (fields
        (field (name "MANUFACTURER") "Panasonic - ECG")
        (field (name "MANUFACTURER PART NUMBER") "ERJ-8ENF32R4V")
        (field (name "SOURCE") "Digikey")
      )
      (libsource (lib "API") (part "RS/ERJ8ENF"))
    )
    (comp (ref "R104")
      (value "32.4 OHM 1%")
      (footprint "R1206")
      (description "RES 32.4 OHM 1/4W 1% 1206 SMD")
      (fields
        (field (name "MANUFACTURER") "Panasonic - ECG")
        (field (name "MANUFACTURER PART NUMBER") "ERJ-8ENF32R4V")
        (field (name "SOURCE") "Digikey")
      )
      (libsource (lib "API") (part "RS/ERJ8ENF"))
    )
    (comp (ref "R105")
      (value "32.4 OHM 1%")
      (footprint "R1206")
      (description "RES 32.4 OHM 1/4W 1% 1206 SMD")
      (fields
        (field (name "MANUFACTURER") "Panasonic - ECG")
        (field (name "MANUFACTURER PART NUMBER") "ERJ-8ENF32R4V")
        (field (name "SOURCE") "Digikey")
      )
      (libsource (lib "API") (part "RS/ERJ8ENF"))
    )
    (comp (ref "R106")
      (value "32.4 OHM 1%")
      (footprint "R1206")
      (description "RES 32.4 OHM 1/4W 1% 1206 SMD")
      (fields
        (field (name "MANUFACTURER") "Panasonic - ECG")
        (field (name "MANUFACTURER PART NUMBER") "ERJ-8ENF32R4V")
        (field (name "SOURCE") "Digikey")
      )
      (libsource (lib "API") (part "RS/ERJ8ENF"))
    )
    (comp (ref "R107")
      (value "32.4 OHM 1%")
      (footprint "R1206")
      (description "RES 32.4 OHM 1/4W 1% 1206 SMD")
      (fields
        (field (name "MANUFACTURER") "Panasonic - ECG")
        (field (name "MANUFACTURER PART NUMBER") "ERJ-8ENF32R4V")
        (field (name "SOURCE") "Digikey")
      )
      (libsource (lib "API") (part "RS/ERJ8ENF"))
    )
    (comp (ref "R108")
      (value "32.4 OHM 1%")
      (footprint "R1206")
      (description "RES 32.4 OHM 1/4W 1% 1206 SMD")
      (fields
        (field (name "MANUFACTURER") "Panasonic - ECG")
        (field (name "MANUFACTURER PART NUMBER") "ERJ-8ENF32R4V")
        (field (name "SOURCE") "Digikey")
      )
      (libsource (lib "API") (part "RS/ERJ8ENF"))
    )
    (comp (ref "R109")
      (value "32.4 OHM 1%")
      (footprint "R1206")
      (description "RES 32.4 OHM 1/4W 1% 1206 SMD")
      (fields
        (field (name "MANUFACTURER") "Panasonic - ECG")
        (field (name "MANUFACTURER PART NUMBER") "ERJ-8ENF32R4V")
        (field (name "SOURCE") "Digikey")
      )
      (libsource (lib "API") (part "RS/ERJ8ENF"))
    )
    (comp (ref "R110")
      (value "32.4 OHM 1%")
      (footprint "R1206")
      (description "RES 32.4 OHM 1/4W 1% 1206 SMD")
      (fields
        (field (name "MANUFACTURER") "Panasonic - ECG")
        (field (name "MANUFACTURER PART NUMBER") "ERJ-8ENF32R4V")
        (field (name "SOURCE") "Digikey")
      )
      (libsource (lib "API") (part "RS/ERJ8ENF"))
    )
    (comp (ref "R111")
      (value "32.4 OHM 1%")
      (footprint "R1206")
      (description "RES 32.4 OHM 1/4W 1% 1206 SMD")
      (fields
        (field (name "MANUFACTURER") "Panasonic - ECG")
        (field (name "MANUFACTURER PART NUMBER") "ERJ-8ENF32R4V")
        (field (name "SOURCE") "Digikey")
      )
      (libsource (lib "API") (part "RS/ERJ8ENF"))
    )
    (comp (ref "R112")
      (value "10.0k 1%")
      (footprint "R0805")
      (description "RES 10.0K OHM 1/8W 1% 0805 SMD")
      (fields
        (field (name "MANUFACTURER") "Panasonic - ECG")
        (field (name "MANUFACTURER PART NUMBER") "ERJ-6ENF1002V")
        (field (name "SOURCE") "Digikey")
      )
      (libsource (lib "API") (part "RS/ERJ6ENF"))
    )
    (comp (ref "R128")
      (value "3.16K 1%")
      (footprint "R0805")
      (description "RES 3.16K OHM 1/8W 1% 0805 SMD")
      (fields
        (field (name "MANUFACTURER") "Panasonic - ECG")
        (field (name "MANUFACTURER PART NUMBER") "ERJ-6ENF3161V")
        (field (name "SOURCE") "Digikey")
      )
      (libsource (lib "API") (part "RS/ERJ6ENF"))
    )
    (comp (ref "R129")
      (value "20.0k 1%")
      (footprint "R0805")
      (description "RES 20.0K OHM 1/8W 1% 0805 SMD")
      (fields
        (field (name "MANUFACTURER") "Panasonic - ECG")
        (field (name "MANUFACTURER PART NUMBER") "ERJ-6ENF2002V")
        (field (name "SOURCE") "Digikey")
      )
      (libsource (lib "API") (part "RS/ERJ6ENF"))
    )
    (comp (ref "R130")
      (value "10.0k 1%")
      (footprint "R0805")
      (description "RES 10.0K OHM 1/8W 1% 0805 SMD")
      (fields
        (field (name "MANUFACTURER") "Panasonic - ECG")
        (field (name "MANUFACTURER PART NUMBER") "ERJ-6ENF1002V")
        (field (name "SOURCE") "Digikey")
      )
      (libsource (lib "API") (part "RS/ERJ6ENF"))
    )
    (comp (ref "U1")
      (value "M25P64-VMF6G")
      (footprint "so16w")
      (description "64 MBit Serial SPI NOR FLASH")
      (fields
        (field (name "MANUFACTURER") "STMicroelectronics / Numonyx")
        (field (name "MANUFACTURER PART NUMBER") "M25P64-VMF6P")
        (field (name "SOURCE") "Mouser")
      )
      (libsource (lib "API") (part "IS/M25P64VMF6GZ"))
    )
    (comp (ref "U2")
      (value "dsPIC30F5013-20I/PT")
      (footprint "TQFP-80")
      (description "IC DSPIC MCU/DSP 144K 80TQFP")
      (fields
        (field (name "MANUFACTURER") "Microchip Technology")
        (field (name "MANUFACTURER PART NUMBER") "DSPIC30F6014A-30I/PT")
        (field (name "SOURCE") "Digikey")
      )
      (libsource (lib "API") (part "IS/DSPIC30F501320IPTZ_1"))
    )
    (comp (ref "U3")
      (value "SN65HVD230DR")
      (footprint "SOIC 8")
      (description "IC 3.3V CAN TXRX W/STNDBY 8-SOIC")
      (fields (field (name "MANUFACTURER") "Texas Instruments") (field (name "SOURCE") "Digikey"))
      (libsource (lib "API") (part "IS/SN65HVD230DRT"))
    )
    (comp (ref "U4")
      (value "M25P64-VMF6G")
      (footprint "so16w")
      (description "64 MBit Serial SPI NOR FLASH")
      (fields
        (field (name "MANUFACTURER") "STMicroelectronics / Numonyx")
        (field (name "MANUFACTURER PART NUMBER") "M25P64-VMF6P")
        (field (name "SOURCE") "Mouser")
      )
      (libsource (lib "API") (part "IS/M25P64VMF6GZ"))
    )
    (comp (ref "U5")
      (value "CS4344-CZZ")
      (footprint "TSSOP\\10")
      (description "IC DAC 24BIT 192KHZ 10-TSSOP")
      (fields (field (name "MANUFACTURER") "Cirrus Logic Inc") (field (name "SOURCE") "Digikey"))
      (libsource (lib "API") (part "IS/CS4344CZZZ"))
    )
    (comp (ref "U6")
      (value "LM2676S-ADJ/NOPB")
      (footprint "TO263\\7")
      (description "IC REG SIMPLE SWITCHER TO-263-7")
      (fields (field (name "MANUFACTURER") "National Semiconductor") (field (name "SOURCE") "Digikey"))
      (libsource (lib "API") (part "IS/LM2676SADJN"))
    )
    (comp (ref "U7")
      (value "LP2950CDT-3.3")
      (footprint "D-PAK / TO-252AA")
      (description "IC REG VOLT MICROPWR 3.3V TO-252")
      (fields
        (field (name "MANUFACTURER") "National Semiconductor")
        (field (name "MANUFACTURER PART NUMBER") "LP2950CDT-3.3/NOPB")
        (field (name "SOURCE") "Digikey")
      )
      (libsource (lib "API") (part "IS/LP2950CDT33N"))
    )
    (comp (ref "U8")
      (value "M25P64-VMF6G")
      (footprint "so16w")
      (description "64 MBit Serial SPI NOR FLASH")
      (fields
        (field (name "MANUFACTURER") "STMicroelectronics / Numonyx")
        (field (name "MANUFACTURER PART NUMBER") "M25P64-VMF6P")
        (field (name "SOURCE") "Mouser")
      )
      (libsource (lib "API") (part "IS/M25P64VMF6GZ"))
    )
    (comp (ref "U9")
      (value "M25P64-VMF6G")
      (footprint "so16w")
      (description "64 MBit Serial SPI NOR FLASH")
      (fields
        (field (name "MANUFACTURER") "STMicroelectronics / Numonyx")
        (field (name "MANUFACTURER PART NUMBER") "M25P64-VMF6P")
        (field (name "SOURCE") "Mouser")
      )
      (libsource (lib "API") (part "IS/M25P64VMF6GZ"))
    )
    (comp (ref "U10")
      (value "LM4861M")
      (footprint "M08A")
      (description "IC AMP AUDIO PWR W/SHUTDN 8-SOIC")
      (fields (field (name "MANUFACTURER") "National Semiconductor") (field (name "SOURCE") "Digikey"))
      (libsource (lib "NSC Audio Power Amplifier") (part "LM4861M"))
    )
    (comp (ref "U11")
      (value "LM2676S-ADJ/NOPB")
      (footprint "TO263\\7")
      (description "IC REG SIMPLE SWITCHER TO-263-7")
      (fields (field (name "MANUFACTURER") "National Semiconductor") (field (name "SOURCE") "Digikey"))
      (libsource (lib "API") (part "IS/LM2676SADJN"))
    )
    (comp (ref "U12")
      (value "MOCD207M")
      (footprint "SOIC 8")
      (description "OPTOCOUPLER TRANS-OUT 2CH 8-SOIC")
      (fields
        (field (name "MANUFACTURER") "Fairchild Optoelectronics Group")
        (field (name "SOURCE") "Digikey")
      )
      (libsource (lib "API") (part "I#S/MOCD207MZ"))
    )
    (comp (ref "U13")
      (value "SN74AHC1G125DBVR")
      (footprint "API:SOT23-5")
      (description "TI Tri State Buffer Single Gate")
      (fields (field (name "MANUFACTURER") "Texas Instruments") (field (name "SOURCE") "Digikey"))
      (libsource (lib "API") (part "I#S/SN74AHC1G125DBVT"))
    )
    (comp (ref "U14")
      (value "IC USB-TO-UART BRIDGE 28MLP")
      (footprint "QFN-28")
      (fields
        (field (name "MANUFACTURER") "Silicon Laboratories Inc")
        (field (name "MANUFACTURER PART NUMBER") "CP2102-GM")
        (field (name "SOURCE") "Digikey")
      )
      (libsource (lib "Playworld") (part "CP2102"))
    )
    (comp (ref "Y1")
      (value "8.192MHz")
      (footprint "XTSL\\CSM-7")
      (description "CRYSTAL 8.192MHZ 18PF FUND SMD")
      (fields
        (field (name "MANUFACTURER") "Abracon Corporation")
        (field (name "MANUFACTURER PART NUMBER") "ABLS-8.192MHZ-B2-T")
        (field (name "SOURCE") "Digikey")
      )
      (libsource (lib "API") (part "ZS/ECS1228205PTRZ"))
    )
  )
  (nets
    (net (code "1") (name "/5V") (class "Default")
      (node (ref "C18") (pin "1") (pinfunction "1_1") (pintype "passive"))
      (node (ref "C22") (pin "1") (pinfunction "1_1") (pintype "passive"))
      (node (ref "C32") (pin "1") (pinfunction "1_1") (pintype "passive"))
      (node (ref "DS11") (pin "2") (pinfunction "A_2") (pintype "passive"))
      (node (ref "DS12") (pin "2") (pinfunction "A_2") (pintype "passive"))
      (node (ref "DS15") (pin "2") (pinfunction "A_2") (pintype "passive"))
      (node (ref "DS16") (pin "2") (pinfunction "A_2") (pintype "passive"))
      (node (ref "DS19") (pin "2") (pinfunction "A_2") (pintype "passive"))
      (node (ref "DS20") (pin "2") (pinfunction "A_2") (pintype "passive"))
      (node (ref "DS23") (pin "2") (pinfunction "A_2") (pintype "passive"))
      (node (ref "DS24") (pin "2") (pinfunction "A_2") (pintype "passive"))
      (node (ref "DS27") (pin "2") (pinfunction "A_2") (pintype "passive"))
      (node (ref "DS28") (pin "2") (pinfunction "A_2") (pintype "passive"))
      (node (ref "DS3") (pin "2") (pinfunction "A_2") (pintype "passive"))
      (node (ref "DS31") (pin "2") (pinfunction "A_2") (pintype "passive"))
      (node (ref "DS32") (pin "2") (pinfunction "A_2") (pintype "passive"))
      (node (ref "DS35") (pin "2") (pinfunction "A_2") (pintype "passive"))
      (node (ref "DS36") (pin "2") (pinfunction "A_2") (pintype "passive"))
      (node (ref "DS39") (pin "2") (pinfunction "A_2") (pintype "passive"))
      (node (ref "DS4") (pin "2") (pinfunction "A_2") (pintype "passive"))
      (node (ref "DS40") (pin "2") (pinfunction "A_2") (pintype "passive"))
      (node (ref "DS43") (pin "2") (pinfunction "A_2") (pintype "passive"))
      (node (ref "DS44") (pin "2") (pinfunction "A_2") (pintype "passive"))
      (node (ref "DS47") (pin "2") (pinfunction "A_2") (pintype "passive"))
      (node (ref "DS48") (pin "2") (pinfunction "A_2") (pintype "passive"))
      (node (ref "DS7") (pin "2") (pinfunction "A_2") (pintype "passive"))
      (node (ref "DS8") (pin "2") (pinfunction "A_2") (pintype "passive"))
      (node (ref "L1") (pin "2") (pinfunction "2_2") (pintype "passive"))
      (node (ref "R9") (pin "2") (pinfunction "2_2") (pintype "passive"))
      (node (ref "U10") (pin "6") (pinfunction "VDD_6") (pintype "power_in"))
    )
    (net (code "2") (name "/5V_DISABLE") (class "Default")
      (node (ref "R130") (pin "1") (pinfunction "1_1") (pintype "passive"))
      (node (ref "R20") (pin "1") (pinfunction "1_1") (pintype "passive"))
      (node (ref "U2") (pin "35") (pinfunction "AN14/RB14_35") (pintype "bidirectional"))
    )
    (net (code "3") (name "/AUDIO_SHUTDOWN") (class "Default")
      (node (ref "R15") (pin "1") (pinfunction "1_1") (pintype "passive"))
      (node (ref "U10") (pin "1") (pinfunction "SD_1") (pintype "input"))
      (node (ref "U13") (pin "1") (pinfunction "~{OE}_1") (pintype "input"))
      (node (ref "U2") (pin "46") (pinfunction "SDA/RG3_46") (pintype "bidirectional"))
    )
    (net (code "4") (name "/CANRX") (class "Default")
      (node (ref "U2") (pin "72") (pinfunction "C1RX/RF0_72") (pintype "bidirectional"))
      (node (ref "U3") (pin "4") (pinfunction "R_4") (pintype "output"))
    )
    (net (code "5") (name "/CANTX") (class "Default")
      (node (ref "U2") (pin "73") (pinfunction "C1TX/RF1_73") (pintype "bidirectional"))
      (node (ref "U3") (pin "1") (pinfunction "D_1") (pintype "input"))
    )
    (net (code "6") (name "/CAN_~{HS}{slash}STBY") (class "Default")
      (node (ref "U2") (pin "34") (pinfunction "AN13/RB13_34") (pintype "bidirectional"))
      (node (ref "U3") (pin "8") (pinfunction "~{HS}/STBY_8") (pintype "input"))
    )
    (net (code "7") (name "/COFS") (class "Default")
      (node (ref "U2") (pin "1") (pinfunction "COFS/RG15_1") (pintype "bidirectional"))
      (node (ref "U5") (pin "3") (pinfunction "LRCLK_3") (pintype "passive"))
    )
    (net (code "8") (name "/CSCK") (class "Default")
      (node (ref "U2") (pin "78") (pinfunction "CSCK/RG14_78") (pintype "bidirectional"))
      (node (ref "U5") (pin "2") (pinfunction "~{DEM}/SCLK_2") (pintype "passive"))
    )
    (net (code "9") (name "/CSDO") (class "Default")
      (node (ref "U2") (pin "80") (pinfunction "CSDO/RG13_80") (pintype "bidirectional"))
      (node (ref "U5") (pin "1") (pinfunction "SDIN_1") (pintype "passive"))
    )
    (net (code "10") (name "/LED0") (class "Default")
      (node (ref "R28") (pin "1") (pinfunction "1_1") (pintype "passive"))
      (node (ref "U2") (pin "58") (pinfunction "EMUC2/OC1/RD0_58") (pintype "bidirectional"))
    )
    (net (code "11") (name "/LED1") (class "Default")
      (node (ref "R40") (pin "1") (pinfunction "1_1") (pintype "passive"))
      (node (ref "U2") (pin "61") (pinfunction "EMUD2/OC2/RD1_61") (pintype "bidirectional"))
    )
    (net (code "12") (name "/MCLK") (class "Default")
      (node (ref "R29") (pin "2") (pinfunction "2_2") (pintype "passive"))
      (node (ref "R30") (pin "1") (pinfunction "1_1") (pintype "passive"))
      (node (ref "U13") (pin "4") (pinfunction "Y_4") (pintype "output"))
      (node (ref "U5") (pin "4") (pinfunction "MCLK_4") (pintype "passive"))
    )
    (net (code "13") (name "/MCLR") (class "Default")
      (node (ref "J14") (pin "1") (pinfunction "1_1") (pintype "passive"))
      (node (ref "R4") (pin "1") (pinfunction "1_1") (pintype "passive"))
      (node (ref "U2") (pin "9") (pinfunction "~{MCLR}_9") (pintype "input"))
    )
    (net (code "14") (name "/MEM_~{W}") (class "Default")
      (node (ref "R1") (pin "2") (pinfunction "2_2") (pintype "passive"))
      (node (ref "U1") (pin "9") (pinfunction "~{W}/VPP_9") (pintype "input"))
      (node (ref "U2") (pin "36") (pinfunction "AN15/OCFB/CN12/RB15_36") (pintype "bidirectional"))
      (node (ref "U4") (pin "9") (pinfunction "~{W}/VPP_9") (pintype "input"))
      (node (ref "U8") (pin "9") (pinfunction "~{W}/VPP_9") (pintype "input"))
      (node (ref "U9") (pin "9") (pinfunction "~{W}/VPP_9") (pintype "input"))
    )
    (net (code "15") (name "/OPTION0") (class "Default")
      (node (ref "JP4") (pin "1") (pinfunction "1_1") (pintype "passive"))
      (node (ref "R27") (pin "1") (pinfunction "1_1") (pintype "passive"))
      (node (ref "U2") (pin "76") (pinfunction "CN22/RA6_76") (pintype "bidirectional"))
    )
    (net (code "16") (name "/OPTION1") (class "Default")
      (node (ref "JP3") (pin "1") (pinfunction "1_1") (pintype "passive"))
      (node (ref "R26") (pin "1") (pinfunction "1_1") (pintype "passive"))
      (node (ref "U2") (pin "77") (pinfunction "CN23/RA7_77") (pintype "bidirectional"))
    )
    (net (code "17") (name "/OPTION2") (class "Default")
      (node (ref "JP2") (pin "1") (pinfunction "1_1") (pintype "passive"))
      (node (ref "R23") (pin "1") (pinfunction "1_1") (pintype "passive"))
      (node (ref "U2") (pin "23") (pinfunction "VREF-/RA9_23") (pintype "bidirectional"))
    )
    (net (code "18") (name "/OPTION3") (class "Default")
      (node (ref "JP1") (pin "1") (pinfunction "1_1") (pintype "passive"))
      (node (ref "R19") (pin "1") (pinfunction "1_1") (pintype "passive"))
      (node (ref "U2") (pin "24") (pinfunction "VREF+/RA10_24") (pintype "bidirectional"))
    )
    (net (code "19") (name "/PGC") (class "Default")
      (node (ref "J14") (pin "5") (pinfunction "5_5") (pintype "passive"))
      (node (ref "U2") (pin "19") (pinfunction "AN1/CN3/RB1_19") (pintype "bidirectional"))
    )
    (net (code "20") (name "/PGD") (class "Default")
      (node (ref "J14") (pin "4") (pinfunction "4_4") (pintype "passive"))
      (node (ref "U2") (pin "20") (pinfunction "AN0/CN2/RB0_20") (pintype "bidirectional"))
    )
    (net (code "21") (name "/PIEZO_INPUT") (class "Default")
      (node (ref "R129") (pin "1") (pinfunction "1_1") (pintype "passive"))
      (node (ref "R22") (pin "2") (pinfunction "2_2") (pintype "passive"))
      (node (ref "U12") (pin "8") (pinfunction "8_8") (pintype "passive"))
      (node (ref "U2") (pin "69") (pinfunction "OC8/CN16/RD7_69") (pintype "bidirectional"))
      (node (ref "U2") (pin "74") (pinfunction "C2TX/RG1_74") (pintype "bidirectional"))
    )
    (net (code "22") (name "/RXD2") (class "Default")
      (node (ref "U14") (pin "26") (pinfunction "TXD_26") (pintype "output"))
      (node (ref "U2") (pin "39") (pinfunction "U2RX/CN17/RF4_39") (pintype "bidirectional"))
    )
    (net (code "23") (name "/SCK") (class "Default")
      (node (ref "U1") (pin "16") (pinfunction "CLK_16") (pintype "input"))
      (node (ref "U2") (pin "45") (pinfunction "EMUC3/SCK1/INT0/RF6_45") (pintype "bidirectional"))
      (node (ref "U4") (pin "16") (pinfunction "CLK_16") (pintype "input"))
      (node (ref "U8") (pin "16") (pinfunction "CLK_16") (pintype "input"))
      (node (ref "U9") (pin "16") (pinfunction "CLK_16") (pintype "input"))
    )
    (net (code "24") (name "/SDI") (class "Default")
      (node (ref "R21") (pin "1") (pinfunction "1_1") (pintype "passive"))
      (node (ref "U1") (pin "8") (pinfunction "Q_8") (pintype "tri_state"))
      (node (ref "U2") (pin "44") (pinfunction "SDI1/RF7_44") (pintype "bidirectional"))
      (node (ref "U4") (pin "8") (pinfunction "Q_8") (pintype "tri_state"))
      (node (ref "U8") (pin "8") (pinfunction "Q_8") (pintype "tri_state"))
      (node (ref "U9") (pin "8") (pinfunction "Q_8") (pintype "tri_state"))
    )
    (net (code "25") (name "/SDO") (class "Default")
      (node (ref "U1") (pin "15") (pinfunction "D_15") (pintype "input"))
      (node (ref "U2") (pin "43") (pinfunction "EMUD3/SDO1/RF8_43") (pintype "bidirectional"))
      (node (ref "U4") (pin "15") (pinfunction "D_15") (pintype "input"))
      (node (ref "U8") (pin "15") (pinfunction "D_15") (pintype "input"))
      (node (ref "U9") (pin "15") (pinfunction "D_15") (pintype "input"))
    )
    (net (code "26") (name "/TXD2") (class "Default")
      (node (ref "U14") (pin "25") (pinfunction "RXD_25") (pintype "input"))
      (node (ref "U2") (pin "40") (pinfunction "U2TX/CN18/RF5_40") (pintype "bidirectional"))
    )
    (net (code "27") (name "/USB_RST") (class "Default")
      (node (ref "R112") (pin "1") (pinfunction "1_1") (pintype "passive"))
      (node (ref "U14") (pin "9") (pinfunction "~{RST}_9") (pintype "bidirectional"))
      (node (ref "U2") (pin "75") (pinfunction "C2RX/RG0_75") (pintype "bidirectional"))
    )
    (net (code "28") (name "/VIN_SENSE_ANALOG") (class "Default")
      (node (ref "C37") (pin "1") (pinfunction "1_1") (pintype "passive"))
      (node (ref "R24") (pin "1") (pinfunction "1_1") (pintype "passive"))
      (node (ref "R25") (pin "2") (pinfunction "2_2") (pintype "passive"))
      (node (ref "U2") (pin "18") (pinfunction "AN2/~{SS1}/LVDIN/CN4/RB2_18") (pintype "bidirectional"))
    )
    (net (code "29") (name "/V_IN") (class "Default")
      (node (ref "C10") (pin "1") (pinfunction "1_1") (pintype "passive"))
      (node (ref "C13") (pin "1") (pinfunction "1_1") (pintype "passive"))
      (node (ref "C34") (pin "1") (pinfunction "1_1") (pintype "passive"))
      (node (ref "C5") (pin "1") (pinfunction "1_1") (pintype "passive"))
      (node (ref "C7") (pin "1") (pinfunction "1_1") (pintype "passive"))
      (node (ref "D1") (pin "K") (pinfunction "K_K") (pintype "passive"))
      (node (ref "R24") (pin "2") (pinfunction "2_2") (pintype "passive"))
      (node (ref "U11") (pin "2") (pinfunction "IN_2") (pintype "power_in"))
      (node (ref "U12") (pin "1") (pinfunction "1_1") (pintype "passive"))
      (node (ref "U12") (pin "4") (pinfunction "4_4") (pintype "passive"))
      (node (ref "U6") (pin "2") (pinfunction "IN_2") (pintype "power_in"))
      (node (ref "U7") (pin "1") (pinfunction "IN_1") (pintype "power_in"))
    )
    (net (code "30") (name "/V_RED") (class "Default")
      (node (ref "C30") (pin "1") (pinfunction "1_1") (pintype "passive"))
      (node (ref "C31") (pin "1") (pinfunction "1_1") (pintype "passive"))
      (node (ref "DS1") (pin "2") (pinfunction "A_2") (pintype "passive"))
      (node (ref "DS10") (pin "2") (pinfunction "A_2") (pintype "passive"))
      (node (ref "DS13") (pin "2") (pinfunction "A_2") (pintype "passive"))
      (node (ref "DS14") (pin "2") (pinfunction "A_2") (pintype "passive"))
      (node (ref "DS17") (pin "2") (pinfunction "A_2") (pintype "passive"))
      (node (ref "DS18") (pin "2") (pinfunction "A_2") (pintype "passive"))
      (node (ref "DS2") (pin "2") (pinfunction "A_2") (pintype "passive"))
      (node (ref "DS21") (pin "2") (pinfunction "A_2") (pintype "passive"))
      (node (ref "DS22") (pin "2") (pinfunction "A_2") (pintype "passive"))
      (node (ref "DS25") (pin "2") (pinfunction "A_2") (pintype "passive"))
      (node (ref "DS26") (pin "2") (pinfunction "A_2") (pintype "passive"))
      (node (ref "DS29") (pin "2") (pinfunction "A_2") (pintype "passive"))
      (node (ref "DS30") (pin "2") (pinfunction "A_2") (pintype "passive"))
      (node (ref "DS33") (pin "2") (pinfunction "A_2") (pintype "passive"))
      (node (ref "DS34") (pin "2") (pinfunction "A_2") (pintype "passive"))
      (node (ref "DS37") (pin "2") (pinfunction "A_2") (pintype "passive"))
      (node (ref "DS38") (pin "2") (pinfunction "A_2") (pintype "passive"))
      (node (ref "DS41") (pin "2") (pinfunction "A_2") (pintype "passive"))
      (node (ref "DS42") (pin "2") (pinfunction "A_2") (pintype "passive"))
      (node (ref "DS45") (pin "2") (pinfunction "A_2") (pintype "passive"))
      (node (ref "DS46") (pin "2") (pinfunction "A_2") (pintype "passive"))
      (node (ref "DS5") (pin "2") (pinfunction "A_2") (pintype "passive"))
      (node (ref "DS6") (pin "2") (pinfunction "A_2") (pintype "passive"))
      (node (ref "DS9") (pin "2") (pinfunction "A_2") (pintype "passive"))
      (node (ref "L2") (pin "2") (pinfunction "2_2") (pintype "passive"))
      (node (ref "R18") (pin "2") (pinfunction "2_2") (pintype "passive"))
    )
    (net (code "31") (name "/~{MEM0}") (class "Default")
      (node (ref "R3") (pin "1") (pinfunction "1_1") (pintype "passive"))
      (node (ref "U1") (pin "7") (pinfunction "~{S}_7") (pintype "input"))
      (node (ref "U2") (pin "13") (pinfunction "INT1/RA12_13") (pintype "bidirectional"))
    )
    (net (code "32") (name "/~{MEM1}") (class "Default")
      (node (ref "R6") (pin "1") (pinfunction "1_1") (pintype "passive"))
      (node (ref "U2") (pin "14") (pinfunction "INT2/RA13_14") (pintype "bidirectional"))
      (node (ref "U4") (pin "7") (pinfunction "~{S}_7") (pintype "input"))
    )
    (net (code "33") (name "/~{MEM2}") (class "Default")
      (node (ref "R10") (pin "1") (pinfunction "1_1") (pintype "passive"))
      (node (ref "U2") (pin "52") (pinfunction "INT3/RA14_52") (pintype "bidirectional"))
      (node (ref "U8") (pin "7") (pinfunction "~{S}_7") (pintype "input"))
    )
    (net (code "34") (name "/~{MEM3}") (class "Default")
      (node (ref "R14") (pin "1") (pinfunction "1_1") (pintype "passive"))
      (node (ref "U2") (pin "53") (pinfunction "INT4/RA15_53") (pintype "bidirectional"))
      (node (ref "U9") (pin "7") (pinfunction "~{S}_7") (pintype "input"))
    )
    (net (code "35") (name "GND") (class "Default")
      (node (ref "C1") (pin "2") (pinfunction "2_2") (pintype "passive"))
      (node (ref "C10") (pin "2") (pinfunction "2_2") (pintype "passive"))
      (node (ref "C11") (pin "2") (pinfunction "2_2") (pintype "passive"))
      (node (ref "C13") (pin "2") (pinfunction "2_2") (pintype "passive"))
      (node (ref "C14") (pin "2") (pinfunction "2_2") (pintype "passive"))
      (node (ref "C16") (pin "2") (pinfunction "2_2") (pintype "passive"))
      (node (ref "C17") (pin "2") (pinfunction "2_2") (pintype "passive"))
      (node (ref "C18") (pin "2") (pinfunction "2_2") (pintype "passive"))
      (node (ref "C19") (pin "2") (pinfunction "2_2") (pintype "passive"))
      (node (ref "C2") (pin "2") (pinfunction "2_2") (pintype "passive"))
      (node (ref "C20") (pin "2") (pinfunction "2_2") (pintype "passive"))
      (node (ref "C21") (pin "2") (pinfunction "2_2") (pintype "passive"))
      (node (ref "C22") (pin "2") (pinfunction "2_2") (pintype "passive"))
      (node (ref "C23") (pin "2") (pinfunction "2_2") (pintype "passive"))
      (node (ref "C24") (pin "2") (pinfunction "2_2") (pintype "passive"))
      (node (ref "C28") (pin "2") (pinfunction "2_2") (pintype "passive"))
      (node (ref "C3") (pin "2") (pinfunction "2_2") (pintype "passive"))
      (node (ref "C30") (pin "2") (pinfunction "2_2") (pintype "passive"))
      (node (ref "C31") (pin "2") (pinfunction "2_2") (pintype "passive"))
      (node (ref "C32") (pin "2") (pinfunction "2_2") (pintype "passive"))
      (node (ref "C33") (pin "2") (pinfunction "2_2") (pintype "passive"))
      (node (ref "C34") (pin "2") (pinfunction "2_2") (pintype "passive"))
      (node (ref "C37") (pin "2") (pinfunction "2_2") (pintype "passive"))
      (node (ref "C4") (pin "2") (pinfunction "2_2") (pintype "passive"))
      (node (ref "C42") (pin "2") (pinfunction "2_2") (pintype "passive"))
      (node (ref "C5") (pin "2") (pinfunction "2_2") (pintype "passive"))
      (node (ref "C6") (pin "2") (pinfunction "2_2") (pintype "passive"))
      (node (ref "C7") (pin "2") (pinfunction "2_2") (pintype "passive"))
      (node (ref "C8") (pin "2") (pinfunction "2_2") (pintype "passive"))
      (node (ref "C9") (pin "2") (pinfunction "2_2") (pintype "passive"))
      (node (ref "D2") (pin "3") (pinfunction "A_3") (pintype "passive"))
      (node (ref "D3") (pin "1") (pinfunction "A_1") (pintype "passive"))
      (node (ref "D4") (pin "1") (pinfunction "A_1") (pintype "passive"))
      (node (ref "D5") (pin "1") (pinfunction "A_1") (pintype "passive"))
      (node (ref "D7") (pin "3") (pinfunction "A_3") (pintype "passive"))
      (node (ref "DS49") (pin "2") (pinfunction "K_2") (pintype "passive"))
      (node (ref "DS50") (pin "2") (pinfunction "K_2") (pintype "passive"))
      (node (ref "J1") (pin "1") (pinfunction ".125_AMP-IN_1") (pintype "passive"))
      (node (ref "J12") (pin "1") (pinfunction ".125_AMP-IN_1") (pintype "passive"))
      (node (ref "J13") (pin "4") (pinfunction "GND_4") (pintype "power_in"))
      (node (ref "J14") (pin "3") (pinfunction "3_3") (pintype "passive"))
      (node (ref "J5") (pin "1") (pinfunction ".125_AMP-IN_1") (pintype "passive"))
      (node (ref "JP1") (pin "2") (pinfunction "2_2") (pintype "passive"))
      (node (ref "JP2") (pin "2") (pinfunction "2_2") (pintype "passive"))
      (node (ref "JP3") (pin "2") (pinfunction "2_2") (pintype "passive"))
      (node (ref "JP4") (pin "2") (pinfunction "2_2") (pintype "passive"))
      (node (ref "Q1") (pin "1") (pinfunction "S_1") (pintype "passive"))
      (node (ref "Q1") (pin "2") (pinfunction "S_2") (pintype "passive"))
      (node (ref "Q1") (pin "3") (pinfunction "S_3") (pintype "passive"))
      (node (ref "Q2") (pin "1") (pinfunction "S_1") (pintype "passive"))
      (node (ref "Q2") (pin "2") (pinfunction "S_2") (pintype "passive"))
      (node (ref "Q2") (pin "3") (pinfunction "S_3") (pintype "passive"))
      (node (ref "R11") (pin "1") (pinfunction "1_1") (pintype "passive"))
      (node (ref "R17") (pin "1") (pinfunction "1_1") (pintype "passive"))
      (node (ref "R25") (pin "1") (pinfunction "1_1") (pintype "passive"))
      (node (ref "R7") (pin "1") (pinfunction "1_1") (pintype "passive"))
      (node (ref "U1") (pin "10") (pinfunction "VSS_10") (pintype "power_in"))
      (node (ref "U10") (pin "7") (pinfunction "GND_7") (pintype "power_in"))
      (node (ref "U11") (pin "4") (pinfunction "GND_4") (pintype "power_in"))
      (node (ref "U11") (pin "8") (pinfunction "TAB_GND_8") (pintype "power_in"))
      (node (ref "U12") (pin "7") (pinfunction "7_7") (pintype "passive"))
      (node (ref "U13") (pin "3") (pinfunction "GND_3") (pintype "power_in"))
      (node (ref "U14") (pin "29") (pinfunction "THERMAL_PAD_29") (pintype "passive"))
      (node (ref "U14") (pin "3") (pinfunction "GND_3") (pintype "power_in"))
      (node (ref "U2") (pin "11") (pinfunction "VSS_11") (pintype "power_in"))
      (node (ref "U2") (pin "26") (pinfunction "AVSS_26") (pintype "power_in"))
      (node (ref "U2") (pin "31") (pinfunction "VSS_31") (pintype "power_in"))
      (node (ref "U2") (pin "51") (pinfunction "VSS_51") (pintype "power_in"))
      (node (ref "U2") (pin "70") (pinfunction "VSS_70") (pintype "power_in"))
      (node (ref "U2") (pin "79") (pinfunction "CSDI/RG12_79") (pintype "bidirectional"))
      (node (ref "U3") (pin "2") (pinfunction "GND_2") (pintype "power_in"))
      (node (ref "U4") (pin "10") (pinfunction "VSS_10") (pintype "power_in"))
      (node (ref "U5") (pin "8") (pinfunction "GND_8") (pintype "passive"))
      (node (ref "U6") (pin "4") (pinfunction "GND_4") (pintype "power_in"))
      (node (ref "U6") (pin "8") (pinfunction "TAB_GND_8") (pintype "power_in"))
      (node (ref "U7") (pin "2") (pinfunction "GND_2") (pintype "power_in"))
      (node (ref "U8") (pin "10") (pinfunction "VSS_10") (pintype "power_in"))
      (node (ref "U9") (pin "10") (pinfunction "VSS_10") (pintype "power_in"))
    )
    (net (code "36") (name "Net-(C15-Pad2)") (class "Default")
      (node (ref "C15") (pin "2") (pinfunction "2_2") (pintype "passive"))
      (node (ref "R11") (pin "2") (pinfunction "2_2") (pintype "passive"))
      (node (ref "R12") (pin "1") (pinfunction "1_1") (pintype "passive"))
    )
    (net (code "37") (name "Net-(C24-Pad1)") (class "Default")
      (node (ref "C24") (pin "1") (pinfunction "1_1") (pintype "passive"))
      (node (ref "C25") (pin "1") (pinfunction "1_1") (pintype "passive"))
      (node (ref "R12") (pin "2") (pinfunction "2_2") (pintype "passive"))
    )
    (net (code "38") (name "Net-(C25-Pad2)") (class "Default")
      (node (ref "C25") (pin "2") (pinfunction "2_2") (pintype "passive"))
      (node (ref "R13") (pin "1") (pinfunction "1_1") (pintype "passive"))
    )
    (net (code "39") (name "Net-(D2-K)") (class "Default")
      (node (ref "C12") (pin "2") (pinfunction "2_2") (pintype "passive"))
      (node (ref "D2") (pin "2") (pinfunction "K_2") (pintype "passive"))
      (node (ref "L1") (pin "1") (pinfunction "1_1") (pintype "passive"))
      (node (ref "U6") (pin "1") (pinfunction "OUT_1") (pintype "power_in"))
    )
    (net (code "40") (name "Net-(D3-K)") (class "Default")
      (node (ref "D3") (pin "3") (pinfunction "K_3") (pintype "passive"))
      (node (ref "J13") (pin "1") (pinfunction "VBUS_1") (pintype "power_in"))
      (node (ref "U14") (pin "8") (pinfunction "VBUS_8") (pintype "input"))
    )
    (net (code "41") (name "Net-(D4-K)") (class "Default")
      (node (ref "D4") (pin "3") (pinfunction "K_3") (pintype "passive"))
      (node (ref "J13") (pin "2") (pinfunction "D-_2") (pintype "input"))
      (node (ref "U14") (pin "5") (pinfunction "D-_5") (pintype "bidirectional"))
    )
    (net (code "42") (name "Net-(D5-K)") (class "Default")
      (node (ref "D5") (pin "3") (pinfunction "K_3") (pintype "passive"))
      (node (ref "J13") (pin "3") (pinfunction "D+_3") (pintype "input"))
      (node (ref "U14") (pin "4") (pinfunction "D+_4") (pintype "bidirectional"))
    )
    (net (code "43") (name "Net-(D7-K)") (class "Default")
      (node (ref "C26") (pin "2") (pinfunction "2_2") (pintype "passive"))
      (node (ref "D7") (pin "2") (pinfunction "K_2") (pintype "passive"))
      (node (ref "L2") (pin "1") (pinfunction "1_1") (pintype "passive"))
      (node (ref "U11") (pin "1") (pinfunction "OUT_1") (pintype "power_in"))
    )
    (net (code "44") (name "Net-(DS1-K-Pad1)") (class "Default")
      (node (ref "DS1") (pin "1") (pinfunction "K_1") (pintype "passive"))
      (node (ref "DS1") (pin "3") (pinfunction "K_3") (pintype "passive"))
      (node (ref "DS1") (pin "4") (pinfunction "K_4") (pintype "passive"))
      (node (ref "R46") (pin "2") (pinfunction "2_2") (pintype "passive"))
    )
    (net (code "45") (name "Net-(DS2-K-Pad1)") (class "Default")
      (node (ref "DS2") (pin "1") (pinfunction "K_1") (pintype "passive"))
      (node (ref "DS2") (pin "3") (pinfunction "K_3") (pintype "passive"))
      (node (ref "DS2") (pin "4") (pinfunction "K_4") (pintype "passive"))
      (node (ref "R47") (pin "2") (pinfunction "2_2") (pintype "passive"))
    )
    (net (code "46") (name "Net-(DS3-K-Pad1)") (class "Default")
      (node (ref "DS3") (pin "1") (pinfunction "K_1") (pintype "passive"))
      (node (ref "DS3") (pin "3") (pinfunction "K_3") (pintype "passive"))
      (node (ref "DS3") (pin "4") (pinfunction "K_4") (pintype "passive"))
      (node (ref "R58") (pin "2") (pinfunction "2_2") (pintype "passive"))
    )
    (net (code "47") (name "Net-(DS4-K-Pad1)") (class "Default")
      (node (ref "DS4") (pin "1") (pinfunction "K_1") (pintype "passive"))
      (node (ref "DS4") (pin "3") (pinfunction "K_3") (pintype "passive"))
      (node (ref "DS4") (pin "4") (pinfunction "K_4") (pintype "passive"))
      (node (ref "R59") (pin "2") (pinfunction "2_2") (pintype "passive"))
    )
    (net (code "48") (name "Net-(DS5-K-Pad1)") (class "Default")
      (node (ref "DS5") (pin "1") (pinfunction "K_1") (pintype "passive"))
      (node (ref "DS5") (pin "3") (pinfunction "K_3") (pintype "passive"))
      (node (ref "DS5") (pin "4") (pinfunction "K_4") (pintype "passive"))
      (node (ref "R48") (pin "2") (pinfunction "2_2") (pintype "passive"))
    )
    (net (code "49") (name "Net-(DS6-K-Pad1)") (class "Default")
      (node (ref "DS6") (pin "1") (pinfunction "K_1") (pintype "passive"))
      (node (ref "DS6") (pin "3") (pinfunction "K_3") (pintype "passive"))
      (node (ref "DS6") (pin "4") (pinfunction "K_4") (pintype "passive"))
      (node (ref "R49") (pin "2") (pinfunction "2_2") (pintype "passive"))
    )
    (net (code "50") (name "Net-(DS7-K-Pad1)") (class "Default")
      (node (ref "DS7") (pin "1") (pinfunction "K_1") (pintype "passive"))
      (node (ref "DS7") (pin "3") (pinfunction "K_3") (pintype "passive"))
      (node (ref "DS7") (pin "4") (pinfunction "K_4") (pintype "passive"))
      (node (ref "R60") (pin "2") (pinfunction "2_2") (pintype "passive"))
    )
    (net (code "51") (name "Net-(DS8-K-Pad1)") (class "Default")
      (node (ref "DS8") (pin "1") (pinfunction "K_1") (pintype "passive"))
      (node (ref "DS8") (pin "3") (pinfunction "K_3") (pintype "passive"))
      (node (ref "DS8") (pin "4") (pinfunction "K_4") (pintype "passive"))
      (node (ref "R61") (pin "2") (pinfunction "2_2") (pintype "passive"))
    )
    (net (code "52") (name "Net-(DS9-K-Pad1)") (class "Default")
      (node (ref "DS9") (pin "1") (pinfunction "K_1") (pintype "passive"))
      (node (ref "DS9") (pin "3") (pinfunction "K_3") (pintype "passive"))
      (node (ref "DS9") (pin "4") (pinfunction "K_4") (pintype "passive"))
      (node (ref "R50") (pin "2") (pinfunction "2_2") (pintype "passive"))
    )
    (net (code "53") (name "Net-(DS10-K-Pad1)") (class "Default")
      (node (ref "DS10") (pin "1") (pinfunction "K_1") (pintype "passive"))
      (node (ref "DS10") (pin "3") (pinfunction "K_3") (pintype "passive"))
      (node (ref "DS10") (pin "4") (pinfunction "K_4") (pintype "passive"))
      (node (ref "R51") (pin "2") (pinfunction "2_2") (pintype "passive"))
    )
    (net (code "54") (name "Net-(DS11-K-Pad1)") (class "Default")
      (node (ref "DS11") (pin "1") (pinfunction "K_1") (pintype "passive"))
      (node (ref "DS11") (pin "3") (pinfunction "K_3") (pintype "passive"))
      (node (ref "DS11") (pin "4") (pinfunction "K_4") (pintype "passive"))
      (node (ref "R62") (pin "2") (pinfunction "2_2") (pintype "passive"))
    )
    (net (code "55") (name "Net-(DS12-K-Pad1)") (class "Default")
      (node (ref "DS12") (pin "1") (pinfunction "K_1") (pintype "passive"))
      (node (ref "DS12") (pin "3") (pinfunction "K_3") (pintype "passive"))
      (node (ref "DS12") (pin "4") (pinfunction "K_4") (pintype "passive"))
      (node (ref "R63") (pin "2") (pinfunction "2_2") (pintype "passive"))
    )
    (net (code "56") (name "Net-(DS13-K-Pad1)") (class "Default")
      (node (ref "DS13") (pin "1") (pinfunction "K_1") (pintype "passive"))
      (node (ref "DS13") (pin "3") (pinfunction "K_3") (pintype "passive"))
      (node (ref "DS13") (pin "4") (pinfunction "K_4") (pintype "passive"))
      (node (ref "R52") (pin "2") (pinfunction "2_2") (pintype "passive"))
    )
    (net (code "57") (name "Net-(DS14-K-Pad1)") (class "Default")
      (node (ref "DS14") (pin "1") (pinfunction "K_1") (pintype "passive"))
      (node (ref "DS14") (pin "3") (pinfunction "K_3") (pintype "passive"))
      (node (ref "DS14") (pin "4") (pinfunction "K_4") (pintype "passive"))
      (node (ref "R53") (pin "2") (pinfunction "2_2") (pintype "passive"))
    )
    (net (code "58") (name "Net-(DS15-K-Pad1)") (class "Default")
      (node (ref "DS15") (pin "1") (pinfunction "K_1") (pintype "passive"))
      (node (ref "DS15") (pin "3") (pinfunction "K_3") (pintype "passive"))
      (node (ref "DS15") (pin "4") (pinfunction "K_4") (pintype "passive"))
      (node (ref "R64") (pin "2") (pinfunction "2_2") (pintype "passive"))
    )
    (net (code "59") (name "Net-(DS16-K-Pad1)") (class "Default")
      (node (ref "DS16") (pin "1") (pinfunction "K_1") (pintype "passive"))
      (node (ref "DS16") (pin "3") (pinfunction "K_3") (pintype "passive"))
      (node (ref "DS16") (pin "4") (pinfunction "K_4") (pintype "passive"))
      (node (ref "R65") (pin "2") (pinfunction "2_2") (pintype "passive"))
    )
    (net (code "60") (name "Net-(DS17-K-Pad1)") (class "Default")
      (node (ref "DS17") (pin "1") (pinfunction "K_1") (pintype "passive"))
      (node (ref "DS17") (pin "3") (pinfunction "K_3") (pintype "passive"))
      (node (ref "DS17") (pin "4") (pinfunction "K_4") (pintype "passive"))
      (node (ref "R54") (pin "2") (pinfunction "2_2") (pintype "passive"))
    )
    (net (code "61") (name "Net-(DS18-K-Pad1)") (class "Default")
      (node (ref "DS18") (pin "1") (pinfunction "K_1") (pintype "passive"))
      (node (ref "DS18") (pin "3") (pinfunction "K_3") (pintype "passive"))
      (node (ref "DS18") (pin "4") (pinfunction "K_4") (pintype "passive"))
      (node (ref "R55") (pin "2") (pinfunction "2_2") (pintype "passive"))
    )
    (net (code "62") (name "Net-(DS19-K-Pad1)") (class "Default")
      (node (ref "DS19") (pin "1") (pinfunction "K_1") (pintype "passive"))
      (node (ref "DS19") (pin "3") (pinfunction "K_3") (pintype "passive"))
      (node (ref "DS19") (pin "4") (pinfunction "K_4") (pintype "passive"))
      (node (ref "R66") (pin "2") (pinfunction "2_2") (pintype "passive"))
    )
    (net (code "63") (name "Net-(DS20-K-Pad1)") (class "Default")
      (node (ref "DS20") (pin "1") (pinfunction "K_1") (pintype "passive"))
      (node (ref "DS20") (pin "3") (pinfunction "K_3") (pintype "passive"))
      (node (ref "DS20") (pin "4") (pinfunction "K_4") (pintype "passive"))
      (node (ref "R67") (pin "2") (pinfunction "2_2") (pintype "passive"))
    )
    (net (code "64") (name "Net-(DS21-K-Pad1)") (class "Default")
      (node (ref "DS21") (pin "1") (pinfunction "K_1") (pintype "passive"))
      (node (ref "DS21") (pin "3") (pinfunction "K_3") (pintype "passive"))
      (node (ref "DS21") (pin "4") (pinfunction "K_4") (pintype "passive"))
      (node (ref "R56") (pin "2") (pinfunction "2_2") (pintype "passive"))
    )
    (net (code "65") (name "Net-(DS22-K-Pad1)") (class "Default")
      (node (ref "DS22") (pin "1") (pinfunction "K_1") (pintype "passive"))
      (node (ref "DS22") (pin "3") (pinfunction "K_3") (pintype "passive"))
      (node (ref "DS22") (pin "4") (pinfunction "K_4") (pintype "passive"))
      (node (ref "R57") (pin "2") (pinfunction "2_2") (pintype "passive"))
    )
    (net (code "66") (name "Net-(DS23-K-Pad1)") (class "Default")
      (node (ref "DS23") (pin "1") (pinfunction "K_1") (pintype "passive"))
      (node (ref "DS23") (pin "3") (pinfunction "K_3") (pintype "passive"))
      (node (ref "DS23") (pin "4") (pinfunction "K_4") (pintype "passive"))
      (node (ref "R68") (pin "2") (pinfunction "2_2") (pintype "passive"))
    )
    (net (code "67") (name "Net-(DS24-K-Pad1)") (class "Default")
      (node (ref "DS24") (pin "1") (pinfunction "K_1") (pintype "passive"))
      (node (ref "DS24") (pin "3") (pinfunction "K_3") (pintype "passive"))
      (node (ref "DS24") (pin "4") (pinfunction "K_4") (pintype "passive"))
      (node (ref "R69") (pin "2") (pinfunction "2_2") (pintype "passive"))
    )
    (net (code "68") (name "Net-(DS25-K-Pad1)") (class "Default")
      (node (ref "DS25") (pin "1") (pinfunction "K_1") (pintype "passive"))
      (node (ref "DS25") (pin "3") (pinfunction "K_3") (pintype "passive"))
      (node (ref "DS25") (pin "4") (pinfunction "K_4") (pintype "passive"))
      (node (ref "R88") (pin "2") (pinfunction "2_2") (pintype "passive"))
    )
    (net (code "69") (name "Net-(DS26-K-Pad1)") (class "Default")
      (node (ref "DS26") (pin "1") (pinfunction "K_1") (pintype "passive"))
      (node (ref "DS26") (pin "3") (pinfunction "K_3") (pintype "passive"))
      (node (ref "DS26") (pin "4") (pinfunction "K_4") (pintype "passive"))
      (node (ref "R89") (pin "2") (pinfunction "2_2") (pintype "passive"))
    )
    (net (code "70") (name "Net-(DS27-K-Pad1)") (class "Default")
      (node (ref "DS27") (pin "1") (pinfunction "K_1") (pintype "passive"))
      (node (ref "DS27") (pin "3") (pinfunction "K_3") (pintype "passive"))
      (node (ref "DS27") (pin "4") (pinfunction "K_4") (pintype "passive"))
      (node (ref "R100") (pin "2") (pinfunction "2_2") (pintype "passive"))
    )
    (net (code "71") (name "Net-(DS28-K-Pad1)") (class "Default")
      (node (ref "DS28") (pin "1") (pinfunction "K_1") (pintype "passive"))
      (node (ref "DS28") (pin "3") (pinfunction "K_3") (pintype "passive"))
      (node (ref "DS28") (pin "4") (pinfunction "K_4") (pintype "passive"))
      (node (ref "R101") (pin "2") (pinfunction "2_2") (pintype "passive"))
    )
    (net (code "72") (name "Net-(DS29-K-Pad1)") (class "Default")
      (node (ref "DS29") (pin "1") (pinfunction "K_1") (pintype "passive"))
      (node (ref "DS29") (pin "3") (pinfunction "K_3") (pintype "passive"))
      (node (ref "DS29") (pin "4") (pinfunction "K_4") (pintype "passive"))
      (node (ref "R90") (pin "2") (pinfunction "2_2") (pintype "passive"))
    )
    (net (code "73") (name "Net-(DS30-K-Pad1)") (class "Default")
      (node (ref "DS30") (pin "1") (pinfunction "K_1") (pintype "passive"))
      (node (ref "DS30") (pin "3") (pinfunction "K_3") (pintype "passive"))
      (node (ref "DS30") (pin "4") (pinfunction "K_4") (pintype "passive"))
      (node (ref "R91") (pin "2") (pinfunction "2_2") (pintype "passive"))
    )
    (net (code "74") (name "Net-(DS31-K-Pad1)") (class "Default")
      (node (ref "DS31") (pin "1") (pinfunction "K_1") (pintype "passive"))
      (node (ref "DS31") (pin "3") (pinfunction "K_3") (pintype "passive"))
      (node (ref "DS31") (pin "4") (pinfunction "K_4") (pintype "passive"))
      (node (ref "R102") (pin "2") (pinfunction "2_2") (pintype "passive"))
    )
    (net (code "75") (name "Net-(DS32-K-Pad1)") (class "Default")
      (node (ref "DS32") (pin "1") (pinfunction "K_1") (pintype "passive"))
      (node (ref "DS32") (pin "3") (pinfunction "K_3") (pintype "passive"))
      (node (ref "DS32") (pin "4") (pinfunction "K_4") (pintype "passive"))
      (node (ref "R103") (pin "2") (pinfunction "2_2") (pintype "passive"))
    )
    (net (code "76") (name "Net-(DS33-K-Pad1)") (class "Default")
      (node (ref "DS33") (pin "1") (pinfunction "K_1") (pintype "passive"))
      (node (ref "DS33") (pin "3") (pinfunction "K_3") (pintype "passive"))
      (node (ref "DS33") (pin "4") (pinfunction "K_4") (pintype "passive"))
      (node (ref "R92") (pin "2") (pinfunction "2_2") (pintype "passive"))
    )
    (net (code "77") (name "Net-(DS34-K-Pad1)") (class "Default")
      (node (ref "DS34") (pin "1") (pinfunction "K_1") (pintype "passive"))
      (node (ref "DS34") (pin "3") (pinfunction "K_3") (pintype "passive"))
      (node (ref "DS34") (pin "4") (pinfunction "K_4") (pintype "passive"))
      (node (ref "R93") (pin "2") (pinfunction "2_2") (pintype "passive"))
    )
    (net (code "78") (name "Net-(DS35-K-Pad1)") (class "Default")
      (node (ref "DS35") (pin "1") (pinfunction "K_1") (pintype "passive"))
      (node (ref "DS35") (pin "3") (pinfunction "K_3") (pintype "passive"))
      (node (ref "DS35") (pin "4") (pinfunction "K_4") (pintype "passive"))
      (node (ref "R104") (pin "2") (pinfunction "2_2") (pintype "passive"))
    )
    (net (code "79") (name "Net-(DS36-K-Pad1)") (class "Default")
      (node (ref "DS36") (pin "1") (pinfunction "K_1") (pintype "passive"))
      (node (ref "DS36") (pin "3") (pinfunction "K_3") (pintype "passive"))
      (node (ref "DS36") (pin "4") (pinfunction "K_4") (pintype "passive"))
      (node (ref "R105") (pin "2") (pinfunction "2_2") (pintype "passive"))
    )
    (net (code "80") (name "Net-(DS37-K-Pad1)") (class "Default")
      (node (ref "DS37") (pin "1") (pinfunction "K_1") (pintype "passive"))
      (node (ref "DS37") (pin "3") (pinfunction "K_3") (pintype "passive"))
      (node (ref "DS37") (pin "4") (pinfunction "K_4") (pintype "passive"))
      (node (ref "R94") (pin "2") (pinfunction "2_2") (pintype "passive"))
    )
    (net (code "81") (name "Net-(DS38-K-Pad1)") (class "Default")
      (node (ref "DS38") (pin "1") (pinfunction "K_1") (pintype "passive"))
      (node (ref "DS38") (pin "3") (pinfunction "K_3") (pintype "passive"))
      (node (ref "DS38") (pin "4") (pinfunction "K_4") (pintype "passive"))
      (node (ref "R95") (pin "2") (pinfunction "2_2") (pintype "passive"))
    )
    (net (code "82") (name "Net-(DS39-K-Pad1)") (class "Default")
      (node (ref "DS39") (pin "1") (pinfunction "K_1") (pintype "passive"))
      (node (ref "DS39") (pin "3") (pinfunction "K_3") (pintype "passive"))
      (node (ref "DS39") (pin "4") (pinfunction "K_4") (pintype "passive"))
      (node (ref "R106") (pin "2") (pinfunction "2_2") (pintype "passive"))
    )
    (net (code "83") (name "Net-(DS40-K-Pad1)") (class "Default")
      (node (ref "DS40") (pin "1") (pinfunction "K_1") (pintype "passive"))
      (node (ref "DS40") (pin "3") (pinfunction "K_3") (pintype "passive"))
      (node (ref "DS40") (pin "4") (pinfunction "K_4") (pintype "passive"))
      (node (ref "R107") (pin "2") (pinfunction "2_2") (pintype "passive"))
    )
    (net (code "84") (name "Net-(DS41-K-Pad1)") (class "Default")
      (node (ref "DS41") (pin "1") (pinfunction "K_1") (pintype "passive"))
      (node (ref "DS41") (pin "3") (pinfunction "K_3") (pintype "passive"))
      (node (ref "DS41") (pin "4") (pinfunction "K_4") (pintype "passive"))
      (node (ref "R96") (pin "2") (pinfunction "2_2") (pintype "passive"))
    )
    (net (code "85") (name "Net-(DS42-K-Pad1)") (class "Default")
      (node (ref "DS42") (pin "1") (pinfunction "K_1") (pintype "passive"))
      (node (ref "DS42") (pin "3") (pinfunction "K_3") (pintype "passive"))
      (node (ref "DS42") (pin "4") (pinfunction "K_4") (pintype "passive"))
      (node (ref "R97") (pin "2") (pinfunction "2_2") (pintype "passive"))
    )
    (net (code "86") (name "Net-(DS43-K-Pad1)") (class "Default")
      (node (ref "DS43") (pin "1") (pinfunction "K_1") (pintype "passive"))
      (node (ref "DS43") (pin "3") (pinfunction "K_3") (pintype "passive"))
      (node (ref "DS43") (pin "4") (pinfunction "K_4") (pintype "passive"))
      (node (ref "R108") (pin "2") (pinfunction "2_2") (pintype "passive"))
    )
    (net (code "87") (name "Net-(DS44-K-Pad1)") (class "Default")
      (node (ref "DS44") (pin "1") (pinfunction "K_1") (pintype "passive"))
      (node (ref "DS44") (pin "3") (pinfunction "K_3") (pintype "passive"))
      (node (ref "DS44") (pin "4") (pinfunction "K_4") (pintype "passive"))
      (node (ref "R109") (pin "2") (pinfunction "2_2") (pintype "passive"))
    )
    (net (code "88") (name "Net-(DS45-K-Pad1)") (class "Default")
      (node (ref "DS45") (pin "1") (pinfunction "K_1") (pintype "passive"))
      (node (ref "DS45") (pin "3") (pinfunction "K_3") (pintype "passive"))
      (node (ref "DS45") (pin "4") (pinfunction "K_4") (pintype "passive"))
      (node (ref "R98") (pin "2") (pinfunction "2_2") (pintype "passive"))
    )
    (net (code "89") (name "Net-(DS46-K-Pad1)") (class "Default")
      (node (ref "DS46") (pin "1") (pinfunction "K_1") (pintype "passive"))
      (node (ref "DS46") (pin "3") (pinfunction "K_3") (pintype "passive"))
      (node (ref "DS46") (pin "4") (pinfunction "K_4") (pintype "passive"))
      (node (ref "R99") (pin "2") (pinfunction "2_2") (pintype "passive"))
    )
    (net (code "90") (name "Net-(DS47-K-Pad1)") (class "Default")
      (node (ref "DS47") (pin "1") (pinfunction "K_1") (pintype "passive"))
      (node (ref "DS47") (pin "3") (pinfunction "K_3") (pintype "passive"))
      (node (ref "DS47") (pin "4") (pinfunction "K_4") (pintype "passive"))
      (node (ref "R110") (pin "2") (pinfunction "2_2") (pintype "passive"))
    )
    (net (code "91") (name "Net-(DS48-K-Pad1)") (class "Default")
      (node (ref "DS48") (pin "1") (pinfunction "K_1") (pintype "passive"))
      (node (ref "DS48") (pin "3") (pinfunction "K_3") (pintype "passive"))
      (node (ref "DS48") (pin "4") (pinfunction "K_4") (pintype "passive"))
      (node (ref "R111") (pin "2") (pinfunction "2_2") (pintype "passive"))
    )
    (net (code "92") (name "Net-(DS49-A)") (class "Default")
      (node (ref "DS49") (pin "1") (pinfunction "A_1") (pintype "passive"))
      (node (ref "Q1") (pin "4") (pinfunction "G_4") (pintype "passive"))
      (node (ref "R28") (pin "2") (pinfunction "2_2") (pintype "passive"))
    )
    (net (code "93") (name "Net-(DS50-A)") (class "Default")
      (node (ref "DS50") (pin "1") (pinfunction "A_1") (pintype "passive"))
      (node (ref "Q2") (pin "4") (pinfunction "G_4") (pintype "passive"))
      (node (ref "R40") (pin "2") (pinfunction "2_2") (pintype "passive"))
    )
    (net (code "94") (name "Net-(J2-.125_AMP-IN)") (class "Default")
      (node (ref "D1") (pin "A") (pinfunction "A_A") (pintype "passive"))
      (node (ref "J2") (pin "1") (pinfunction ".125_AMP-IN_1") (pintype "passive"))
      (node (ref "J6") (pin "1") (pinfunction ".125_AMP-IN_1") (pintype "passive"))
    )
    (net (code "95") (name "Net-(J3-.125_AMP-IN)") (class "Default")
      (node (ref "J3") (pin "1") (pinfunction ".125_AMP-IN_1") (pintype "passive"))
      (node (ref "J7") (pin "1") (pinfunction ".125_AMP-IN_1") (pintype "passive"))
      (node (ref "R5") (pin "2") (pinfunction "2_2") (pintype "passive"))
      (node (ref "U3") (pin "7") (pinfunction "CANH_7") (pintype "bidirectional"))
    )
    (net (code "96") (name "Net-(J4-.125_AMP-IN)") (class "Default")
      (node (ref "J4") (pin "1") (pinfunction ".125_AMP-IN_1") (pintype "passive"))
      (node (ref "J8") (pin "1") (pinfunction ".125_AMP-IN_1") (pintype "passive"))
      (node (ref "R5") (pin "1") (pinfunction "1_1") (pintype "passive"))
      (node (ref "U3") (pin "6") (pinfunction "CANL_6") (pintype "bidirectional"))
    )
    (net (code "97") (name "Net-(J9-.125_AMP-IN)") (class "Default")
      (node (ref "J9") (pin "1") (pinfunction ".125_AMP-IN_1") (pintype "passive"))
      (node (ref "R16") (pin "2") (pinfunction "2_2") (pintype "passive"))
      (node (ref "U10") (pin "5") (pinfunction "VOUT1_5") (pintype "output"))
    )
    (net (code "98") (name "Net-(J10-.125_AMP-IN)") (class "Default")
      (node (ref "J10") (pin "1") (pinfunction ".125_AMP-IN_1") (pintype "passive"))
      (node (ref "U10") (pin "8") (pinfunction "VOUT2_8") (pintype "output"))
    )
    (net (code "99") (name "Net-(J11-.125_AMP-IN)") (class "Default")
      (node (ref "J11") (pin "1") (pinfunction ".125_AMP-IN_1") (pintype "passive"))
      (node (ref "R128") (pin "1") (pinfunction "1_1") (pintype "passive"))
    )
    (net (code "100") (name "Net-(Q1-D-Pad5)") (class "Default")
      (node (ref "Q1") (pin "5") (pinfunction "D_5") (pintype "passive"))
      (node (ref "Q1") (pin "6") (pinfunction "D_6") (pintype "passive"))
      (node (ref "Q1") (pin "7") (pinfunction "D_7") (pintype "passive"))
      (node (ref "Q1") (pin "8") (pinfunction "D_8") (pintype "passive"))
      (node (ref "R46") (pin "1") (pinfunction "1_1") (pintype "passive"))
      (node (ref "R47") (pin "1") (pinfunction "1_1") (pintype "passive"))
      (node (ref "R48") (pin "1") (pinfunction "1_1") (pintype "passive"))
      (node (ref "R49") (pin "1") (pinfunction "1_1") (pintype "passive"))
      (node (ref "R50") (pin "1") (pinfunction "1_1") (pintype "passive"))
      (node (ref "R51") (pin "1") (pinfunction "1_1") (pintype "passive"))
      (node (ref "R52") (pin "1") (pinfunction "1_1") (pintype "passive"))
      (node (ref "R53") (pin "1") (pinfunction "1_1") (pintype "passive"))
      (node (ref "R54") (pin "1") (pinfunction "1_1") (pintype "passive"))
      (node (ref "R55") (pin "1") (pinfunction "1_1") (pintype "passive"))
      (node (ref "R56") (pin "1") (pinfunction "1_1") (pintype "passive"))
      (node (ref "R57") (pin "1") (pinfunction "1_1") (pintype "passive"))
      (node (ref "R88") (pin "1") (pinfunction "1_1") (pintype "passive"))
      (node (ref "R89") (pin "1") (pinfunction "1_1") (pintype "passive"))
      (node (ref "R90") (pin "1") (pinfunction "1_1") (pintype "passive"))
      (node (ref "R91") (pin "1") (pinfunction "1_1") (pintype "passive"))
      (node (ref "R92") (pin "1") (pinfunction "1_1") (pintype "passive"))
      (node (ref "R93") (pin "1") (pinfunction "1_1") (pintype "passive"))
      (node (ref "R94") (pin "1") (pinfunction "1_1") (pintype "passive"))
      (node (ref "R95") (pin "1") (pinfunction "1_1") (pintype "passive"))
      (node (ref "R96") (pin "1") (pinfunction "1_1") (pintype "passive"))
      (node (ref "R97") (pin "1") (pinfunction "1_1") (pintype "passive"))
      (node (ref "R98") (pin "1") (pinfunction "1_1") (pintype "passive"))
      (node (ref "R99") (pin "1") (pinfunction "1_1") (pintype "passive"))
    )
    (net (code "101") (name "Net-(Q2-D-Pad5)") (class "Default")
      (node (ref "Q2") (pin "5") (pinfunction "D_5") (pintype "passive"))
      (node (ref "Q2") (pin "6") (pinfunction "D_6") (pintype "passive"))
      (node (ref "Q2") (pin "7") (pinfunction "D_7") (pintype "passive"))
      (node (ref "Q2") (pin "8") (pinfunction "D_8") (pintype "passive"))
      (node (ref "R100") (pin "1") (pinfunction "1_1") (pintype "passive"))
      (node (ref "R101") (pin "1") (pinfunction "1_1") (pintype "passive"))
      (node (ref "R102") (pin "1") (pinfunction "1_1") (pintype "passive"))
      (node (ref "R103") (pin "1") (pinfunction "1_1") (pintype "passive"))
      (node (ref "R104") (pin "1") (pinfunction "1_1") (pintype "passive"))
      (node (ref "R105") (pin "1") (pinfunction "1_1") (pintype "passive"))
      (node (ref "R106") (pin "1") (pinfunction "1_1") (pintype "passive"))
      (node (ref "R107") (pin "1") (pinfunction "1_1") (pintype "passive"))
      (node (ref "R108") (pin "1") (pinfunction "1_1") (pintype "passive"))
      (node (ref "R109") (pin "1") (pinfunction "1_1") (pintype "passive"))
      (node (ref "R110") (pin "1") (pinfunction "1_1") (pintype "passive"))
      (node (ref "R111") (pin "1") (pinfunction "1_1") (pintype "passive"))
      (node (ref "R58") (pin "1") (pinfunction "1_1") (pintype "passive"))
      (node (ref "R59") (pin "1") (pinfunction "1_1") (pintype "passive"))
      (node (ref "R60") (pin "1") (pinfunction "1_1") (pintype "passive"))
      (node (ref "R61") (pin "1") (pinfunction "1_1") (pintype "passive"))
      (node (ref "R62") (pin "1") (pinfunction "1_1") (pintype "passive"))
      (node (ref "R63") (pin "1") (pinfunction "1_1") (pintype "passive"))
      (node (ref "R64") (pin "1") (pinfunction "1_1") (pintype "passive"))
      (node (ref "R65") (pin "1") (pinfunction "1_1") (pintype "passive"))
      (node (ref "R66") (pin "1") (pinfunction "1_1") (pintype "passive"))
      (node (ref "R67") (pin "1") (pinfunction "1_1") (pintype "passive"))
      (node (ref "R68") (pin "1") (pinfunction "1_1") (pintype "passive"))
      (node (ref "R69") (pin "1") (pinfunction "1_1") (pintype "passive"))
    )
    (net (code "102") (name "Net-(R128-Pad2)") (class "Default")
      (node (ref "R128") (pin "2") (pinfunction "2_2") (pintype "passive"))
      (node (ref "R22") (pin "1") (pinfunction "1_1") (pintype "passive"))
      (node (ref "U12") (pin "2") (pinfunction "2_2") (pintype "passive"))
      (node (ref "U12") (pin "3") (pinfunction "3_3") (pintype "passive"))
    )
    (net (code "103") (name "Net-(U1-~{HOLD})") (class "Default")
      (node (ref "R2") (pin "2") (pinfunction "2_2") (pintype "passive"))
      (node (ref "U1") (pin "1") (pinfunction "~{HOLD}_1") (pintype "input"))
      (node (ref "U4") (pin "1") (pinfunction "~{HOLD}_1") (pintype "input"))
      (node (ref "U8") (pin "1") (pinfunction "~{HOLD}_1") (pintype "input"))
      (node (ref "U9") (pin "1") (pinfunction "~{HOLD}_1") (pintype "input"))
    )
    (net (code "104") (name "Net-(U2-OSC1{slash}CLKIN)") (class "Default")
      (node (ref "C20") (pin "1") (pinfunction "1_1") (pintype "passive"))
      (node (ref "U2") (pin "49") (pinfunction "OSC1/CLKIN_49") (pintype "input"))
      (node (ref "Y1") (pin "1") (pinfunction "OSC1_1") (pintype "passive"))
    )
    (net (code "105") (name "Net-(U5-AOUTR)") (class "Default")
      (node (ref "C15") (pin "1") (pinfunction "1_1") (pintype "passive"))
      (node (ref "U5") (pin "10") (pinfunction "AOUTR_10") (pintype "passive"))
    )
    (net (code "106") (name "Net-(U5-FILT+)") (class "Default")
      (node (ref "C14") (pin "1") (pinfunction "1_1") (pintype "passive"))
      (node (ref "U5") (pin "6") (pinfunction "FILT+_6") (pintype "passive"))
    )
    (net (code "107") (name "Net-(U5-VQ)") (class "Default")
      (node (ref "C6") (pin "1") (pinfunction "1_1") (pintype "passive"))
      (node (ref "C9") (pin "1") (pinfunction "1_1") (pintype "passive"))
      (node (ref "U5") (pin "5") (pinfunction "VQ_5") (pintype "passive"))
    )
    (net (code "108") (name "Net-(U6-CBOOST)") (class "Default")
      (node (ref "C12") (pin "1") (pinfunction "1_1") (pintype "passive"))
      (node (ref "U6") (pin "3") (pinfunction "CBOOST_3") (pintype "power_in"))
    )
    (net (code "109") (name "Net-(U6-FB)") (class "Default")
      (node (ref "R7") (pin "2") (pinfunction "2_2") (pintype "passive"))
      (node (ref "R9") (pin "1") (pinfunction "1_1") (pintype "passive"))
      (node (ref "U6") (pin "6") (pinfunction "FB_6") (pintype "input"))
    )
    (net (code "110") (name "Net-(U6-~{ON}{slash}OFF)") (class "Default")
      (node (ref "R130") (pin "2") (pinfunction "2_2") (pintype "passive"))
      (node (ref "U6") (pin "7") (pinfunction "~{ON}/OFF_7") (pintype "input"))
    )
    (net (code "111") (name "Net-(U10-BYP)") (class "Default")
      (node (ref "C28") (pin "1") (pinfunction "1_1") (pintype "passive"))
      (node (ref "U10") (pin "2") (pinfunction "BYP_2") (pintype "passive"))
      (node (ref "U10") (pin "3") (pinfunction "IN+_3") (pintype "input"))
    )
    (net (code "112") (name "Net-(U10-IN-)") (class "Default")
      (node (ref "R13") (pin "2") (pinfunction "2_2") (pintype "passive"))
      (node (ref "R16") (pin "1") (pinfunction "1_1") (pintype "passive"))
      (node (ref "U10") (pin "4") (pinfunction "IN-_4") (pintype "input"))
    )
    (net (code "113") (name "Net-(U11-CBOOST)") (class "Default")
      (node (ref "C26") (pin "1") (pinfunction "1_1") (pintype "passive"))
      (node (ref "U11") (pin "3") (pinfunction "CBOOST_3") (pintype "power_in"))
    )
    (net (code "114") (name "Net-(U11-FB)") (class "Default")
      (node (ref "R17") (pin "2") (pinfunction "2_2") (pintype "passive"))
      (node (ref "R18") (pin "1") (pinfunction "1_1") (pintype "passive"))
      (node (ref "U11") (pin "6") (pinfunction "FB_6") (pintype "input"))
    )
    (net (code "115") (name "Net-(U11-~{ON}{slash}OFF)") (class "Default")
      (node (ref "R20") (pin "2") (pinfunction "2_2") (pintype "passive"))
      (node (ref "U11") (pin "7") (pinfunction "~{ON}/OFF_7") (pintype "input"))
    )
    (net (code "116") (name "Net-(U13-A)") (class "Default")
      (node (ref "R29") (pin "1") (pinfunction "1_1") (pintype "passive"))
      (node (ref "R8") (pin "1") (pinfunction "1_1") (pintype "passive"))
      (node (ref "U13") (pin "2") (pinfunction "A_2") (pintype "input"))
      (node (ref "U2") (pin "50") (pinfunction "OSC2/CLK0/RC15_50") (pintype "bidirectional"))
    )
    (net (code "117") (name "Net-(Y1-OSC2)") (class "Default")
      (node (ref "C16") (pin "1") (pinfunction "1_1") (pintype "passive"))
      (node (ref "R8") (pin "2") (pinfunction "2_2") (pintype "passive"))
      (node (ref "Y1") (pin "2") (pinfunction "OSC2_2") (pintype "passive"))
    )
    (net (code "118") (name "VCC") (class "Default")
      (node (ref "C1") (pin "1") (pinfunction "1_1") (pintype "passive"))
      (node (ref "C11") (pin "1") (pinfunction "1_1") (pintype "passive"))
      (node (ref "C17") (pin "1") (pinfunction "1_1") (pintype "passive"))
      (node (ref "C19") (pin "1") (pinfunction "1_1") (pintype "passive"))
      (node (ref "C2") (pin "1") (pinfunction "1_1") (pintype "passive"))
      (node (ref "C21") (pin "1") (pinfunction "1_1") (pintype "passive"))
      (node (ref "C23") (pin "1") (pinfunction "1_1") (pintype "passive"))
      (node (ref "C3") (pin "1") (pinfunction "1_1") (pintype "passive"))
      (node (ref "C33") (pin "1") (pinfunction "1_1") (pintype "passive"))
      (node (ref "C4") (pin "1") (pinfunction "1_1") (pintype "passive"))
      (node (ref "C42") (pin "1") (pinfunction "1_1") (pintype "passive"))
      (node (ref "C8") (pin "1") (pinfunction "1_1") (pintype "passive"))
      (node (ref "J14") (pin "2") (pinfunction "2_2") (pintype "passive"))
      (node (ref "R1") (pin "1") (pinfunction "1_1") (pintype "passive"))
      (node (ref "R10") (pin "2") (pinfunction "2_2") (pintype "passive"))
      (node (ref "R112") (pin "2") (pinfunction "2_2") (pintype "passive"))
      (node (ref "R129") (pin "2") (pinfunction "2_2") (pintype "passive"))
      (node (ref "R14") (pin "2") (pinfunction "2_2") (pintype "passive"))
      (node (ref "R15") (pin "2") (pinfunction "2_2") (pintype "passive"))
      (node (ref "R19") (pin "2") (pinfunction "2_2") (pintype "passive"))
      (node (ref "R2") (pin "1") (pinfunction "1_1") (pintype "passive"))
      (node (ref "R21") (pin "2") (pinfunction "2_2") (pintype "passive"))
      (node (ref "R23") (pin "2") (pinfunction "2_2") (pintype "passive"))
      (node (ref "R26") (pin "2") (pinfunction "2_2") (pintype "passive"))
      (node (ref "R27") (pin "2") (pinfunction "2_2") (pintype "passive"))
      (node (ref "R3") (pin "2") (pinfunction "2_2") (pintype "passive"))
      (node (ref "R30") (pin "2") (pinfunction "2_2") (pintype "passive"))
      (node (ref "R4") (pin "2") (pinfunction "2_2") (pintype "passive"))
      (node (ref "R6") (pin "2") (pinfunction "2_2") (pintype "passive"))
      (node (ref "U1") (pin "2") (pinfunction "VCC_2") (pintype "power_in"))
      (node (ref "U13") (pin "5") (pinfunction "VCC_5") (pintype "power_in"))
      (node (ref "U14") (pin "6") (pinfunction "VDD_6") (pintype "power_in"))
      (node (ref "U14") (pin "7") (pinfunction "REGIN_7") (pintype "input"))
      (node (ref "U2") (pin "12") (pinfunction "VDD_12") (pintype "power_in"))
      (node (ref "U2") (pin "25") (pinfunction "AVDD_25") (pintype "power_in"))
      (node (ref "U2") (pin "32") (pinfunction "VDD_32") (pintype "power_in"))
      (node (ref "U2") (pin "48") (pinfunction "VDD_48") (pintype "power_in"))
      (node (ref "U2") (pin "71") (pinfunction "VDD_71") (pintype "power_in"))
      (node (ref "U3") (pin "3") (pinfunction "VCC_3") (pintype "power_in"))
      (node (ref "U4") (pin "2") (pinfunction "VCC_2") (pintype "power_in"))
      (node (ref "U5") (pin "9") (pinfunction "VA_9") (pintype "passive"))
      (node (ref "U7") (pin "3") (pinfunction "OUT_3") (pintype "power_in"))
      (node (ref "U8") (pin "2") (pinfunction "VCC_2") (pintype "power_in"))
      (node (ref "U9") (pin "2") (pinfunction "VCC_2") (pintype "power_in"))
    )
    (net (code "119") (name "unconnected-(D2-NC-Pad1)") (class "Default")
      (node (ref "D2") (pin "1") (pinfunction "NC_1") (pintype "passive"))
    )
    (net (code "120") (name "unconnected-(D7-NC-Pad1)") (class "Default")
      (node (ref "D7") (pin "1") (pinfunction "NC_1") (pintype "passive"))
    )
    (net (code "121") (name "unconnected-(J13-SHLD-Pad5)") (class "Default")
      (node (ref "J13") (pin "5") (pinfunction "SHLD_5") (pintype "passive"))
    )
    (net (code "122") (name "unconnected-(J13-SHLD-Pad6)") (class "Default")
      (node (ref "J13") (pin "6") (pinfunction "SHLD_6") (pintype "passive"))
    )
    (net (code "123") (name "unconnected-(J14-Pad6)") (class "Default")
      (node (ref "J14") (pin "6") (pinfunction "6_6") (pintype "passive"))
    )
    (net (code "124") (name "unconnected-(U2-AN3{slash}CN5{slash}RB3-Pad17)") (class "Default")
      (node (ref "U2") (pin "17") (pinfunction "AN3/CN5/RB3_17") (pintype "bidirectional"))
    )
    (net (code "125") (name "unconnected-(U2-AN4{slash}IC7{slash}CN6{slash}RB4-Pad16)") (class "Default")
      (node (ref "U2") (pin "16") (pinfunction "AN4/IC7/CN6/RB4_16") (pintype "bidirectional"))
    )
    (net (code "126") (name "unconnected-(U2-AN5{slash}IC8{slash}CN7{slash}RB5-Pad15)") (class "Default")
      (node (ref "U2") (pin "15") (pinfunction "AN5/IC8/CN7/RB5_15") (pintype "bidirectional"))
    )
    (net (code "127") (name "unconnected-(U2-AN8{slash}RB8-Pad27)") (class "Default")
      (node (ref "U2") (pin "27") (pinfunction "AN8/RB8_27") (pintype "bidirectional"))
    )
    (net (code "128") (name "unconnected-(U2-AN9{slash}RB9-Pad28)") (class "Default")
      (node (ref "U2") (pin "28") (pinfunction "AN9/RB9_28") (pintype "bidirectional"))
    )
    (net (code "129") (name "unconnected-(U2-AN10{slash}RB10-Pad29)") (class "Default")
      (node (ref "U2") (pin "29") (pinfunction "AN10/RB10_29") (pintype "bidirectional"))
    )
    (net (code "130") (name "unconnected-(U2-AN11{slash}RB11-Pad30)") (class "Default")
      (node (ref "U2") (pin "30") (pinfunction "AN11/RB11_30") (pintype "bidirectional"))
    )
    (net (code "131") (name "unconnected-(U2-AN12{slash}RB12-Pad33)") (class "Default")
      (node (ref "U2") (pin "33") (pinfunction "AN12/RB12_33") (pintype "bidirectional"))
    )
    (net (code "132") (name "unconnected-(U2-EMUC1{slash}SOSCO{slash}T1CK{slash}CN0{slash}RC14-Pad60)") (class "Default")
      (node (ref "U2") (pin "60") (pinfunction "EMUC1/SOSCO/T1CK/CN0/RC14_60") (pintype "bidirectional"))
    )
    (net (code "133") (name "unconnected-(U2-EMUD1{slash}SOSCI{slash}CN1{slash}RC13-Pad59)") (class "Default")
      (node (ref "U2") (pin "59") (pinfunction "EMUD1/SOSCI/CN1/RC13_59") (pintype "bidirectional"))
    )
    (net (code "134") (name "unconnected-(U2-IC1{slash}RD8-Pad54)") (class "Default")
      (node (ref "U2") (pin "54") (pinfunction "IC1/RD8_54") (pintype "bidirectional"))
    )
    (net (code "135") (name "unconnected-(U2-IC2{slash}RD9-Pad55)") (class "Default")
      (node (ref "U2") (pin "55") (pinfunction "IC2/RD9_55") (pintype "bidirectional"))
    )
    (net (code "136") (name "unconnected-(U2-IC3{slash}RD10-Pad56)") (class "Default")
      (node (ref "U2") (pin "56") (pinfunction "IC3/RD10_56") (pintype "bidirectional"))
    )
    (net (code "137") (name "unconnected-(U2-IC4{slash}RD11-Pad57)") (class "Default")
      (node (ref "U2") (pin "57") (pinfunction "IC4/RD11_57") (pintype "bidirectional"))
    )
    (net (code "138") (name "unconnected-(U2-IC5{slash}RD12-Pad64)") (class "Default")
      (node (ref "U2") (pin "64") (pinfunction "IC5/RD12_64") (pintype "bidirectional"))
    )
    (net (code "139") (name "unconnected-(U2-IC6{slash}CN19{slash}RD13-Pad65)") (class "Default")
      (node (ref "U2") (pin "65") (pinfunction "IC6/CN19/RD13_65") (pintype "bidirectional"))
    )
    (net (code "140") (name "unconnected-(U2-IC7{slash}CN20{slash}RD14-Pad37)") (class "Default")
      (node (ref "U2") (pin "37") (pinfunction "IC7/CN20/RD14_37") (pintype "bidirectional"))
    )
    (net (code "141") (name "unconnected-(U2-IC8{slash}CN21{slash}RD15-Pad38)") (class "Default")
      (node (ref "U2") (pin "38") (pinfunction "IC8/CN21/RD15_38") (pintype "bidirectional"))
    )
    (net (code "142") (name "unconnected-(U2-OC3{slash}RD2-Pad62)") (class "Default")
      (node (ref "U2") (pin "62") (pinfunction "OC3/RD2_62") (pintype "bidirectional"))
    )
    (net (code "143") (name "unconnected-(U2-OC4{slash}RD3-Pad63)") (class "Default")
      (node (ref "U2") (pin "63") (pinfunction "OC4/RD3_63") (pintype "bidirectional"))
    )
    (net (code "144") (name "unconnected-(U2-OC5{slash}CN13{slash}RD4-Pad66)") (class "Default")
      (node (ref "U2") (pin "66") (pinfunction "OC5/CN13/RD4_66") (pintype "bidirectional"))
    )
    (net (code "145") (name "unconnected-(U2-OC6{slash}CN14{slash}RD5-Pad67)") (class "Default")
      (node (ref "U2") (pin "67") (pinfunction "OC6/CN14/RD5_67") (pintype "bidirectional"))
    )
    (net (code "146") (name "unconnected-(U2-OC7{slash}CN15{slash}RD6-Pad68)") (class "Default")
      (node (ref "U2") (pin "68") (pinfunction "OC7/CN15/RD6_68") (pintype "bidirectional"))
    )
    (net (code "147") (name "unconnected-(U2-PGC{slash}EMUC{slash}AN6{slash}OCFA{slash}RB6-Pad21)") (class "Default")
      (node (ref "U2") (pin "21") (pinfunction "PGC/EMUC/AN6/OCFA/RB6_21") (pintype "bidirectional"))
    )
    (net (code "148") (name "unconnected-(U2-PGD{slash}EMUD{slash}AN7{slash}RB7-Pad22)") (class "Default")
      (node (ref "U2") (pin "22") (pinfunction "PGD/EMUD/AN7/RB7_22") (pintype "bidirectional"))
    )
    (net (code "149") (name "unconnected-(U2-SCK2{slash}CN8{slash}RG6-Pad6)") (class "Default")
      (node (ref "U2") (pin "6") (pinfunction "SCK2/CN8/RG6_6") (pintype "bidirectional"))
    )
    (net (code "150") (name "unconnected-(U2-SCL{slash}RG2-Pad47)") (class "Default")
      (node (ref "U2") (pin "47") (pinfunction "SCL/RG2_47") (pintype "bidirectional"))
    )
    (net (code "151") (name "unconnected-(U2-SDI2{slash}CN9{slash}RG7-Pad7)") (class "Default")
      (node (ref "U2") (pin "7") (pinfunction "SDI2/CN9/RG7_7") (pintype "bidirectional"))
    )
    (net (code "152") (name "unconnected-(U2-SDO2{slash}CN10{slash}RG8-Pad8)") (class "Default")
      (node (ref "U2") (pin "8") (pinfunction "SDO2/CN10/RG8_8") (pintype "bidirectional"))
    )
    (net (code "153") (name "unconnected-(U2-T2CK{slash}RC1-Pad2)") (class "Default")
      (node (ref "U2") (pin "2") (pinfunction "T2CK/RC1_2") (pintype "bidirectional"))
    )
    (net (code "154") (name "unconnected-(U2-T3CK{slash}RC2-Pad3)") (class "Default")
      (node (ref "U2") (pin "3") (pinfunction "T3CK/RC2_3") (pintype "bidirectional"))
    )
    (net (code "155") (name "unconnected-(U2-U1RX{slash}RF2-Pad42)") (class "Default")
      (node (ref "U2") (pin "42") (pinfunction "U1RX/RF2_42") (pintype "bidirectional"))
    )
    (net (code "156") (name "unconnected-(U2-U1TX{slash}RF3-Pad41)") (class "Default")
      (node (ref "U2") (pin "41") (pinfunction "U1TX/RF3_41") (pintype "bidirectional"))
    )
    (net (code "157") (name "unconnected-(U2-~{SS2}{slash}CN11{slash}RG9-Pad10)") (class "Default")
      (node (ref "U2") (pin "10") (pinfunction "~{SS2}/CN11/RG9_10") (pintype "bidirectional"))
    )
    (net (code "158") (name "unconnected-(U3-VREF-Pad5)") (class "Default")
      (node (ref "U3") (pin "5") (pinfunction "VREF_5") (pintype "passive"))
    )
    (net (code "159") (name "unconnected-(U5-AOUTL-Pad7)") (class "Default")
      (node (ref "U5") (pin "7") (pinfunction "AOUTL_7") (pintype "passive"))
    )
    (net (code "160") (name "unconnected-(U6-NC-Pad5)") (class "Default")
      (node (ref "U6") (pin "5") (pinfunction "NC_5") (pintype "passive"))
    )
    (net (code "161") (name "unconnected-(U11-NC-Pad5)") (class "Default")
      (node (ref "U11") (pin "5") (pinfunction "NC_5") (pintype "passive"))
    )
    (net (code "162") (name "unconnected-(U12-Pad5)") (class "Default")
      (node (ref "U12") (pin "5") (pinfunction "5_5") (pintype "passive"))
    )
    (net (code "163") (name "unconnected-(U12-Pad6)") (class "Default")
      (node (ref "U12") (pin "6") (pinfunction "6_6") (pintype "passive"))
    )
    (net (code "164") (name "unconnected-(U14-CTS-Pad23)") (class "Default")
      (node (ref "U14") (pin "23") (pinfunction "CTS_23") (pintype "input"))
    )
    (net (code "165") (name "unconnected-(U14-DCD-Pad1)") (class "Default")
      (node (ref "U14") (pin "1") (pinfunction "DCD_1") (pintype "input"))
    )
    (net (code "166") (name "unconnected-(U14-DSR-Pad27)") (class "Default")
      (node (ref "U14") (pin "27") (pinfunction "DSR_27") (pintype "input"))
    )
    (net (code "167") (name "unconnected-(U14-DTR-Pad28)") (class "Default")
      (node (ref "U14") (pin "28") (pinfunction "DTR_28") (pintype "output"))
    )
    (net (code "168") (name "unconnected-(U14-RI-Pad2)") (class "Default")
      (node (ref "U14") (pin "2") (pinfunction "RI_2") (pintype "input"))
    )
    (net (code "169") (name "unconnected-(U14-RTS-Pad24)") (class "Default")
      (node (ref "U14") (pin "24") (pinfunction "RTS_24") (pintype "output"))
    )
    (net (code "170") (name "unconnected-(U14-SUSPEND-Pad12)") (class "Default")
      (node (ref "U14") (pin "12") (pinfunction "SUSPEND_12") (pintype "output"))
    )
    (net (code "171") (name "unconnected-(U14-~{SUSPEND}-Pad11)") (class "Default")
      (node (ref "U14") (pin "11") (pinfunction "~{SUSPEND}_11") (pintype "output"))
    )
  )
)
